# aqc-rev4.net
KiCad netlist of a schematic drawn in EAGLE
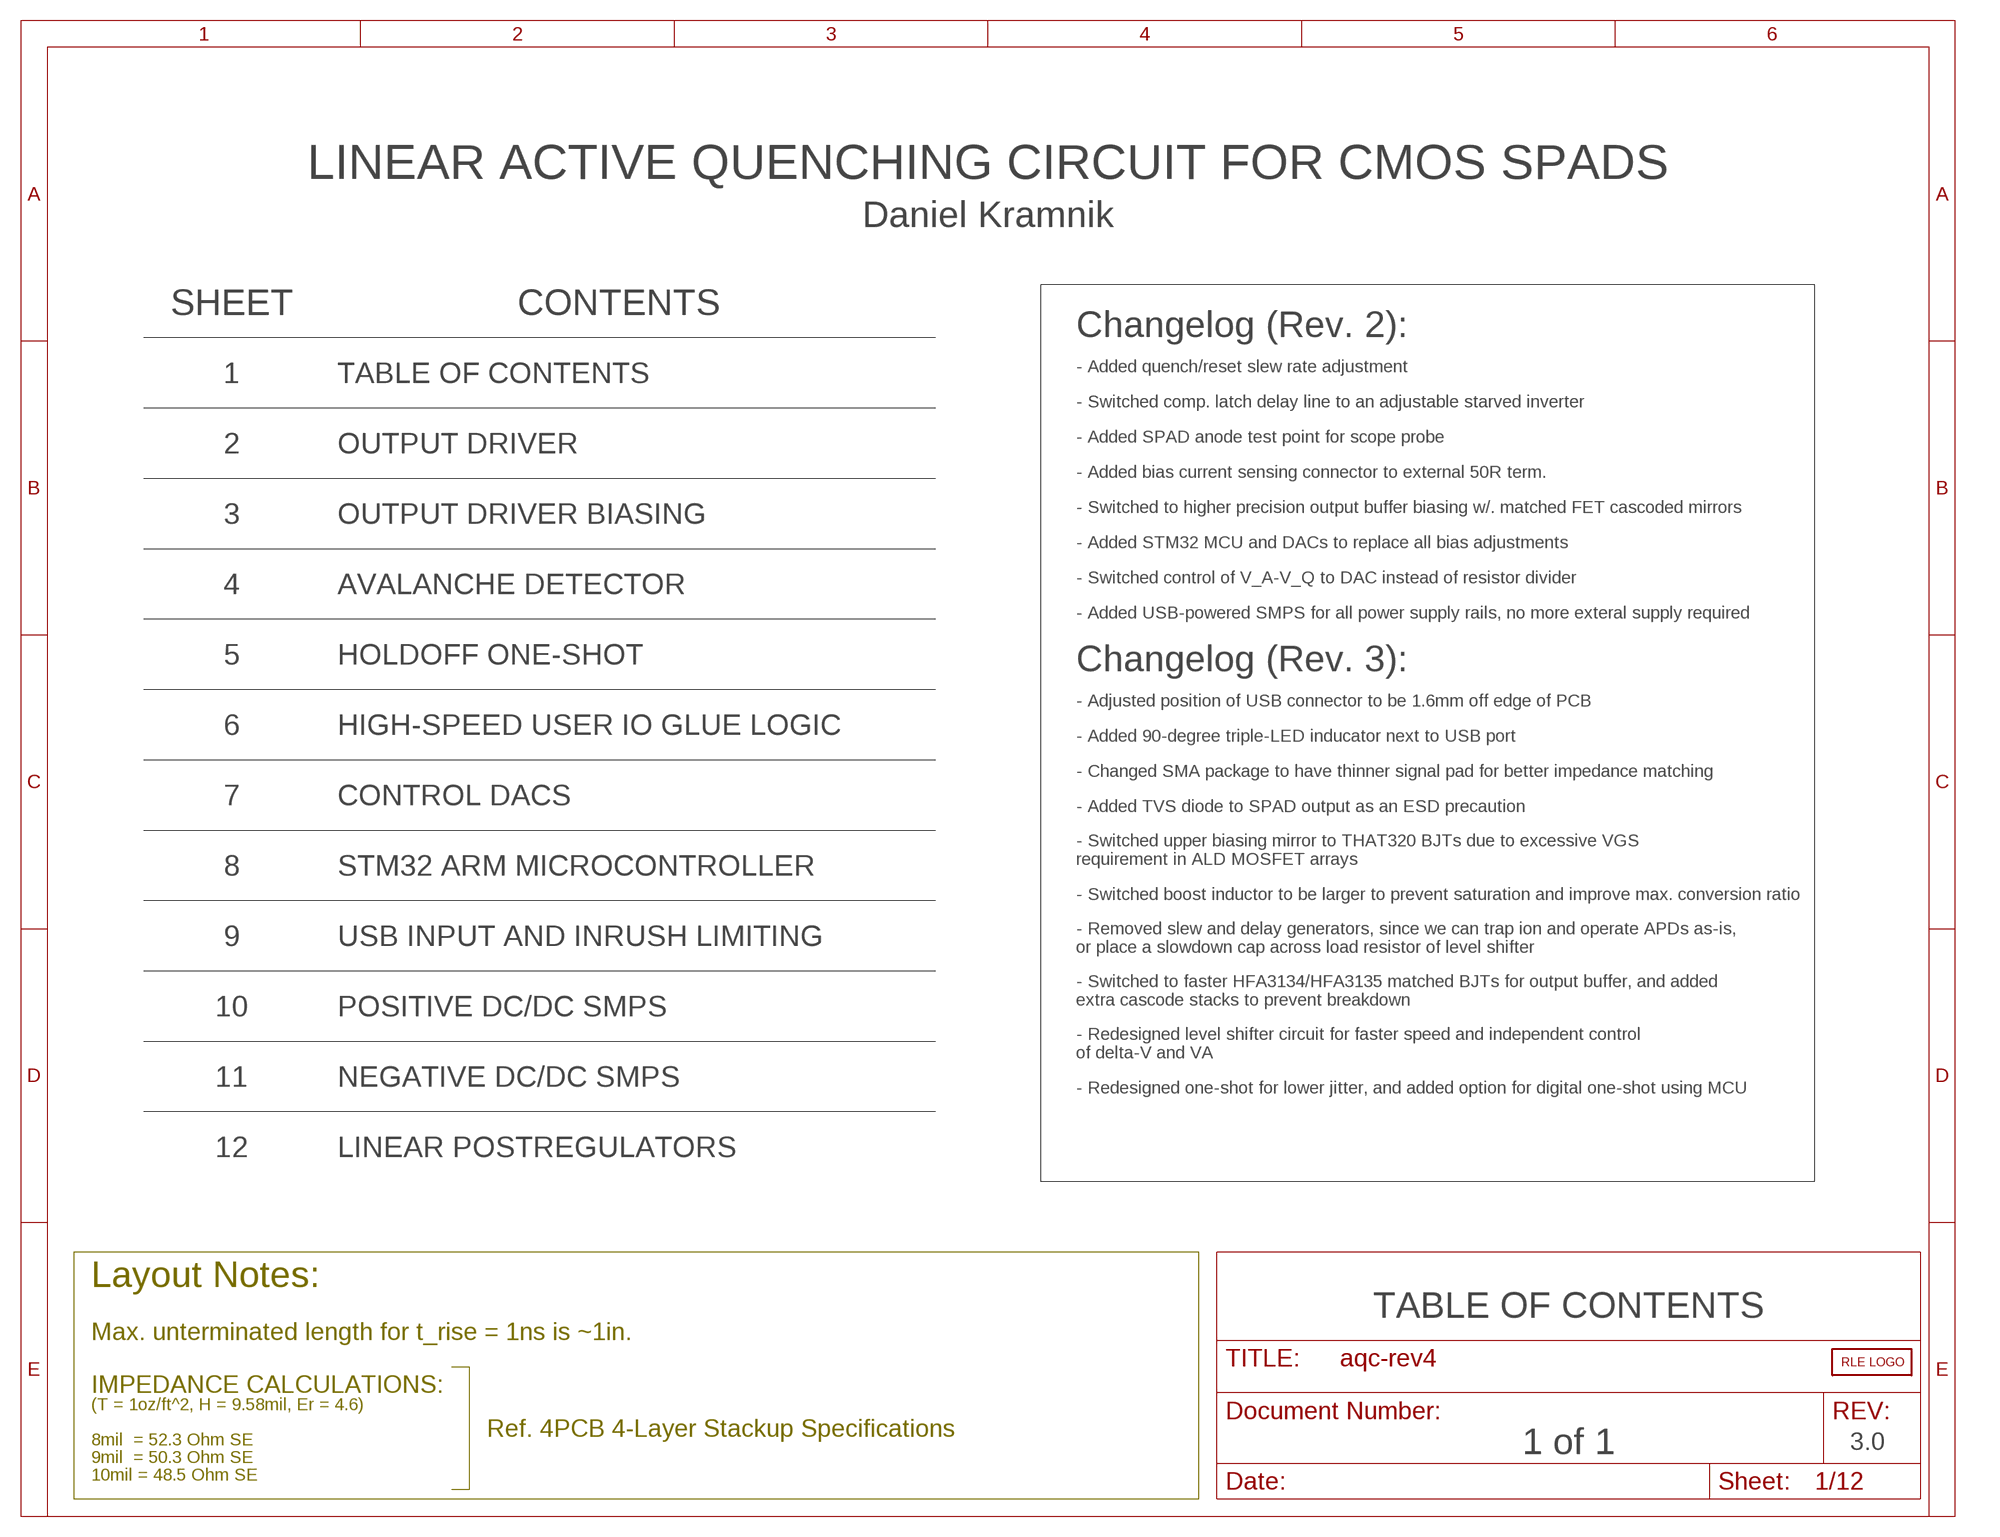
[diagram p0: schematic, sheet 1]
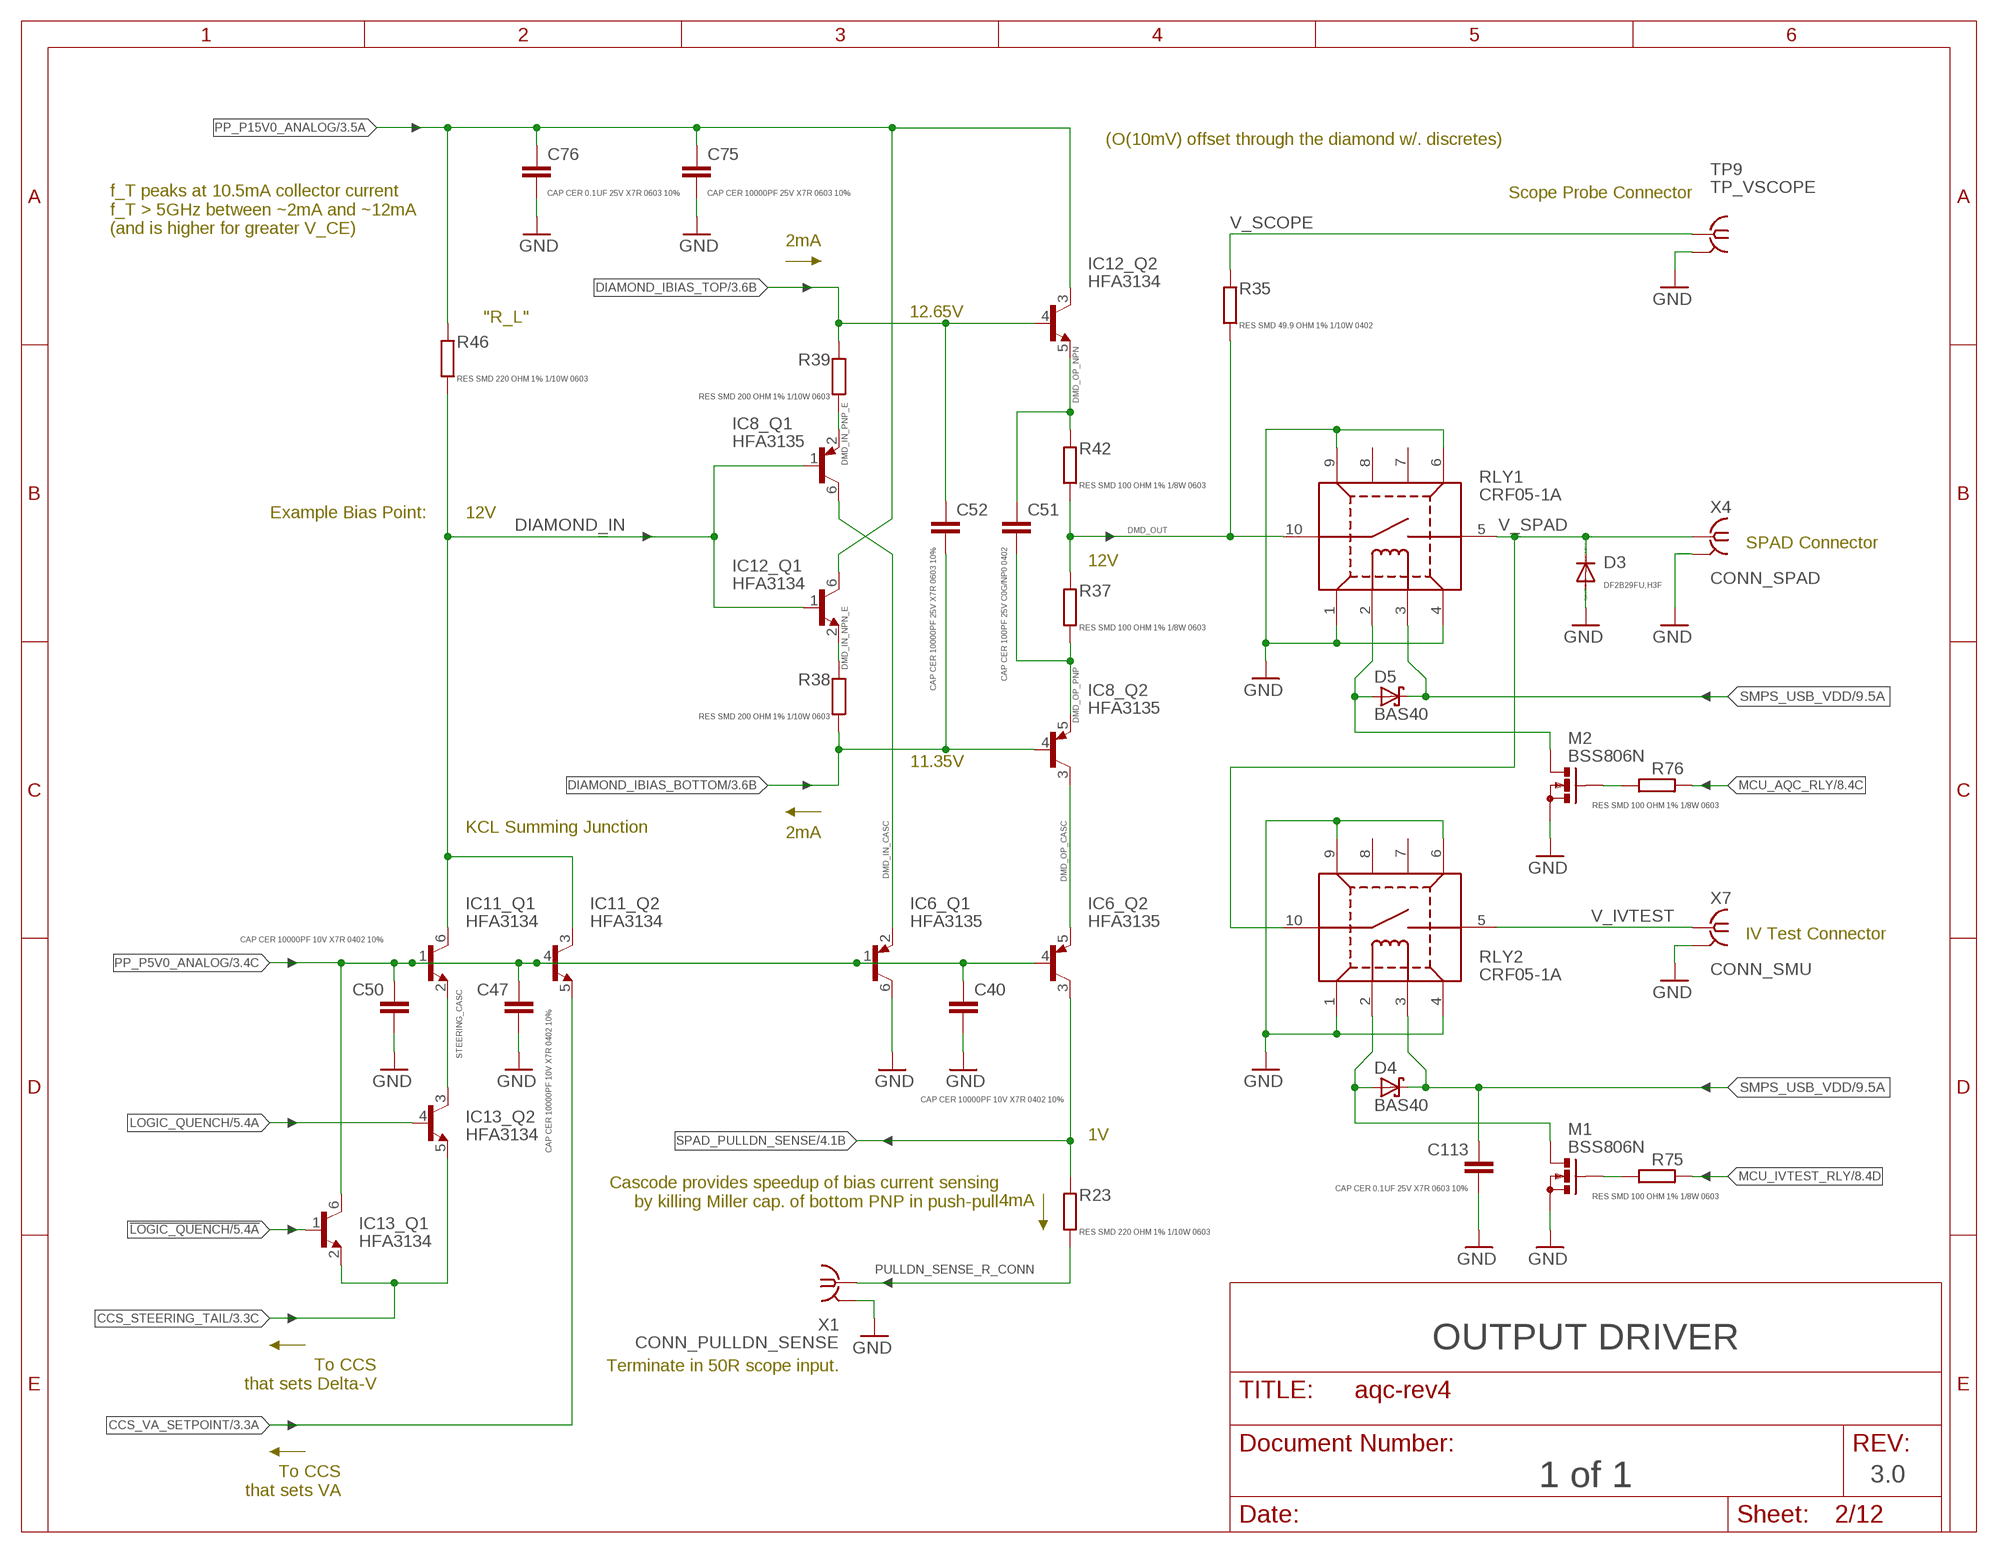
[diagram p1: schematic, sheet 2]
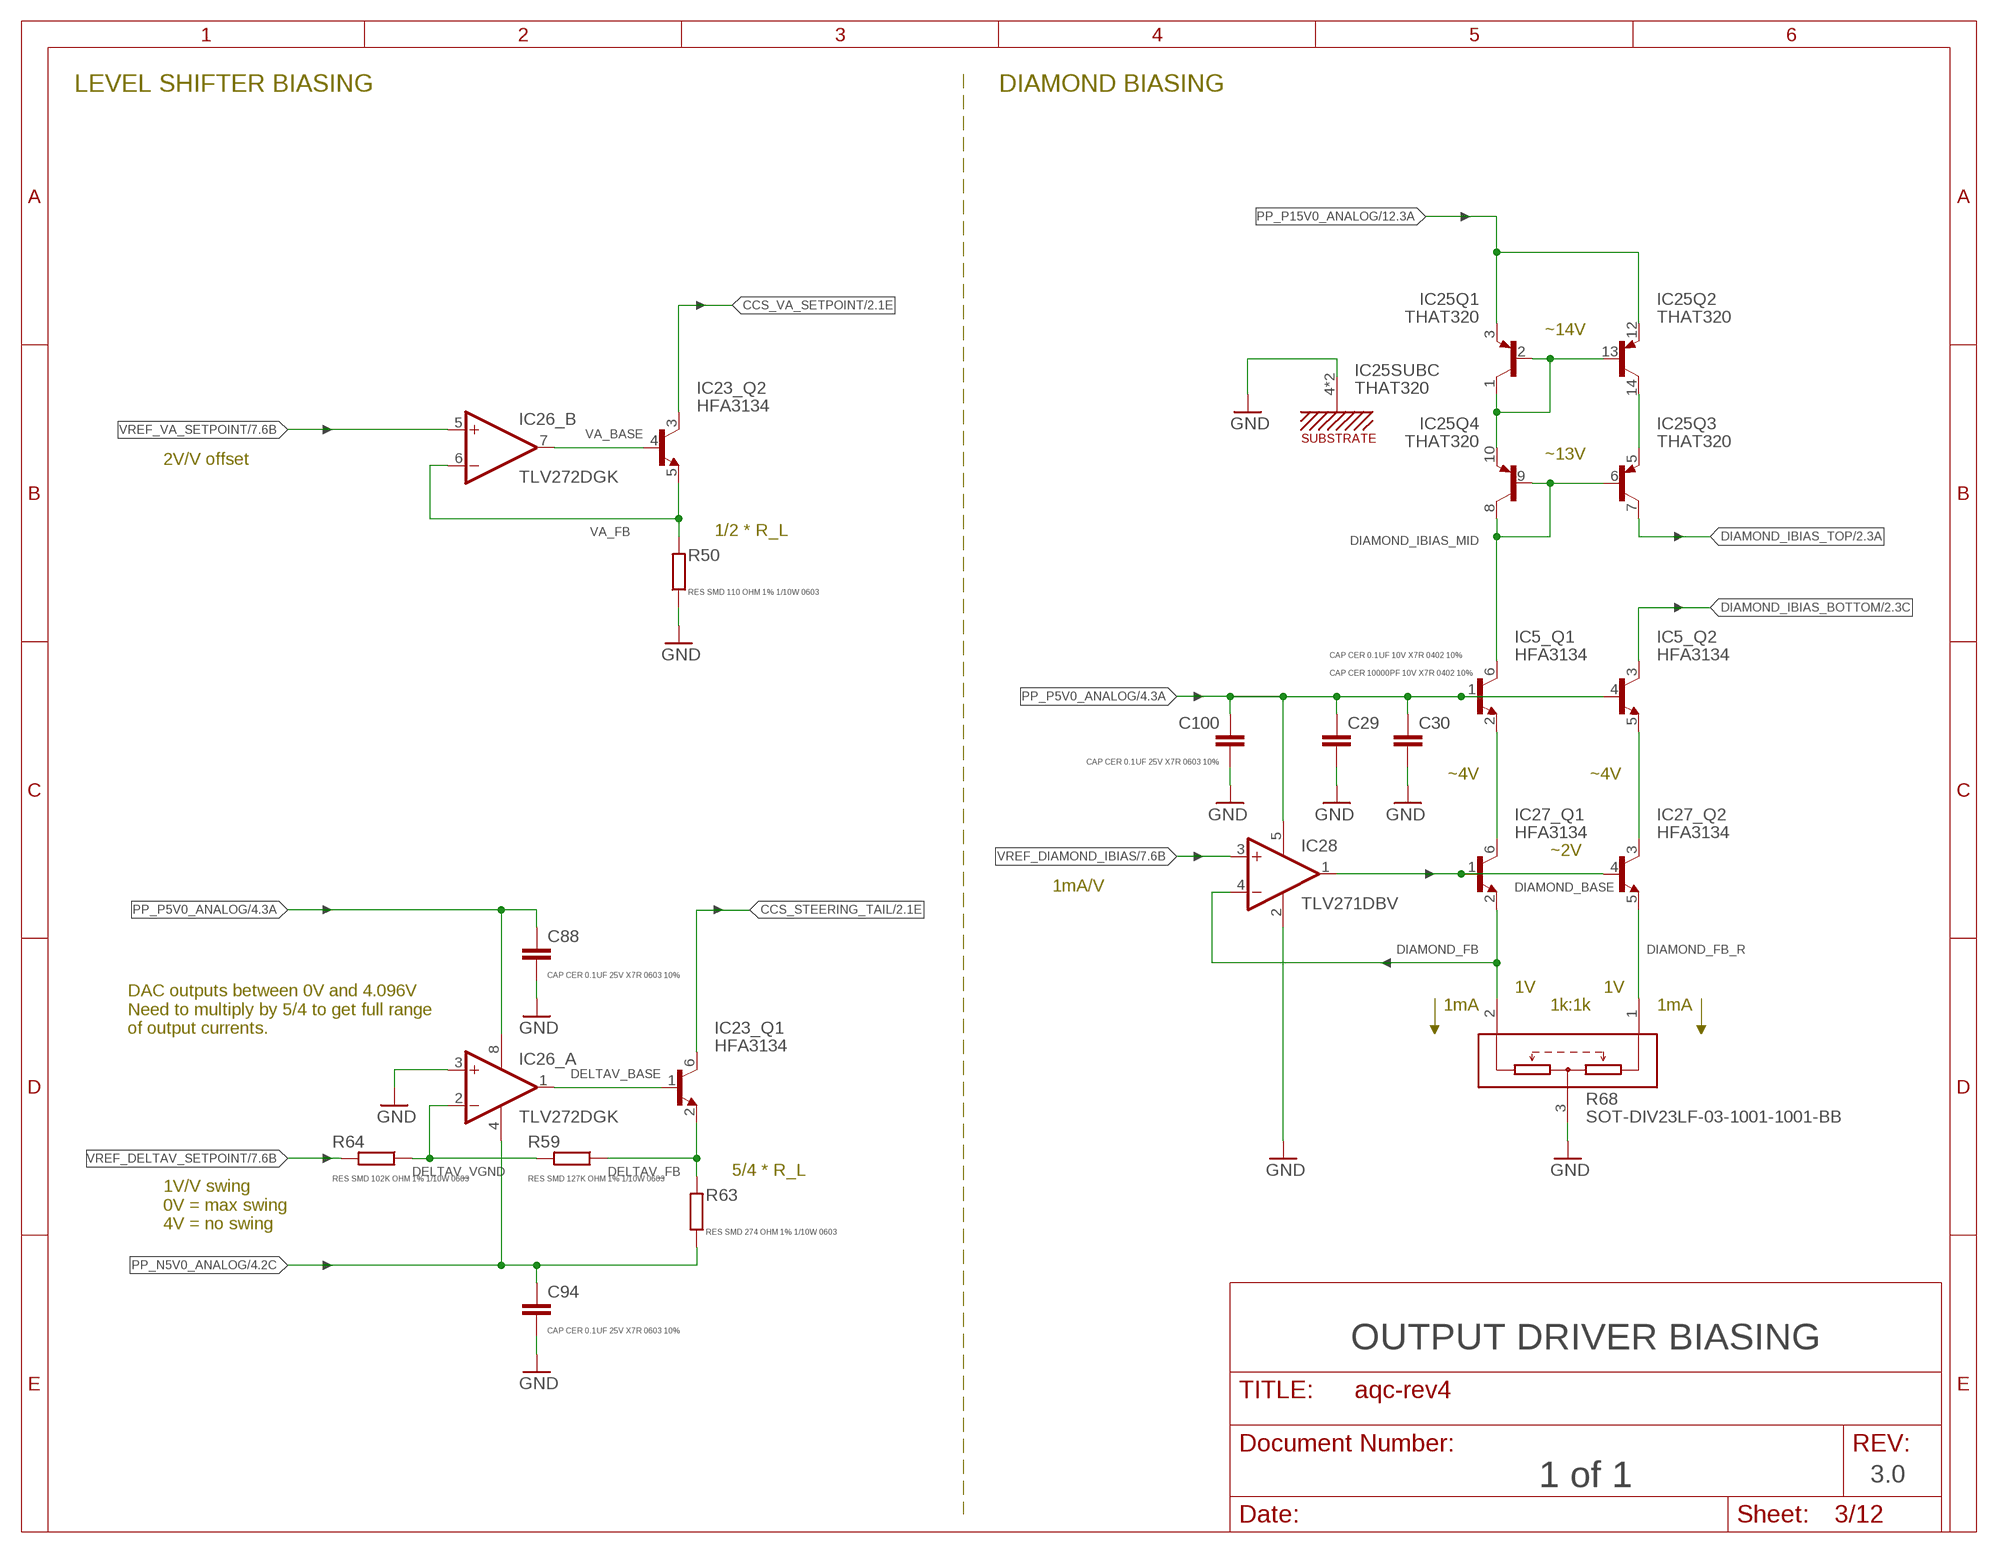
[diagram p2: schematic, sheet 3]
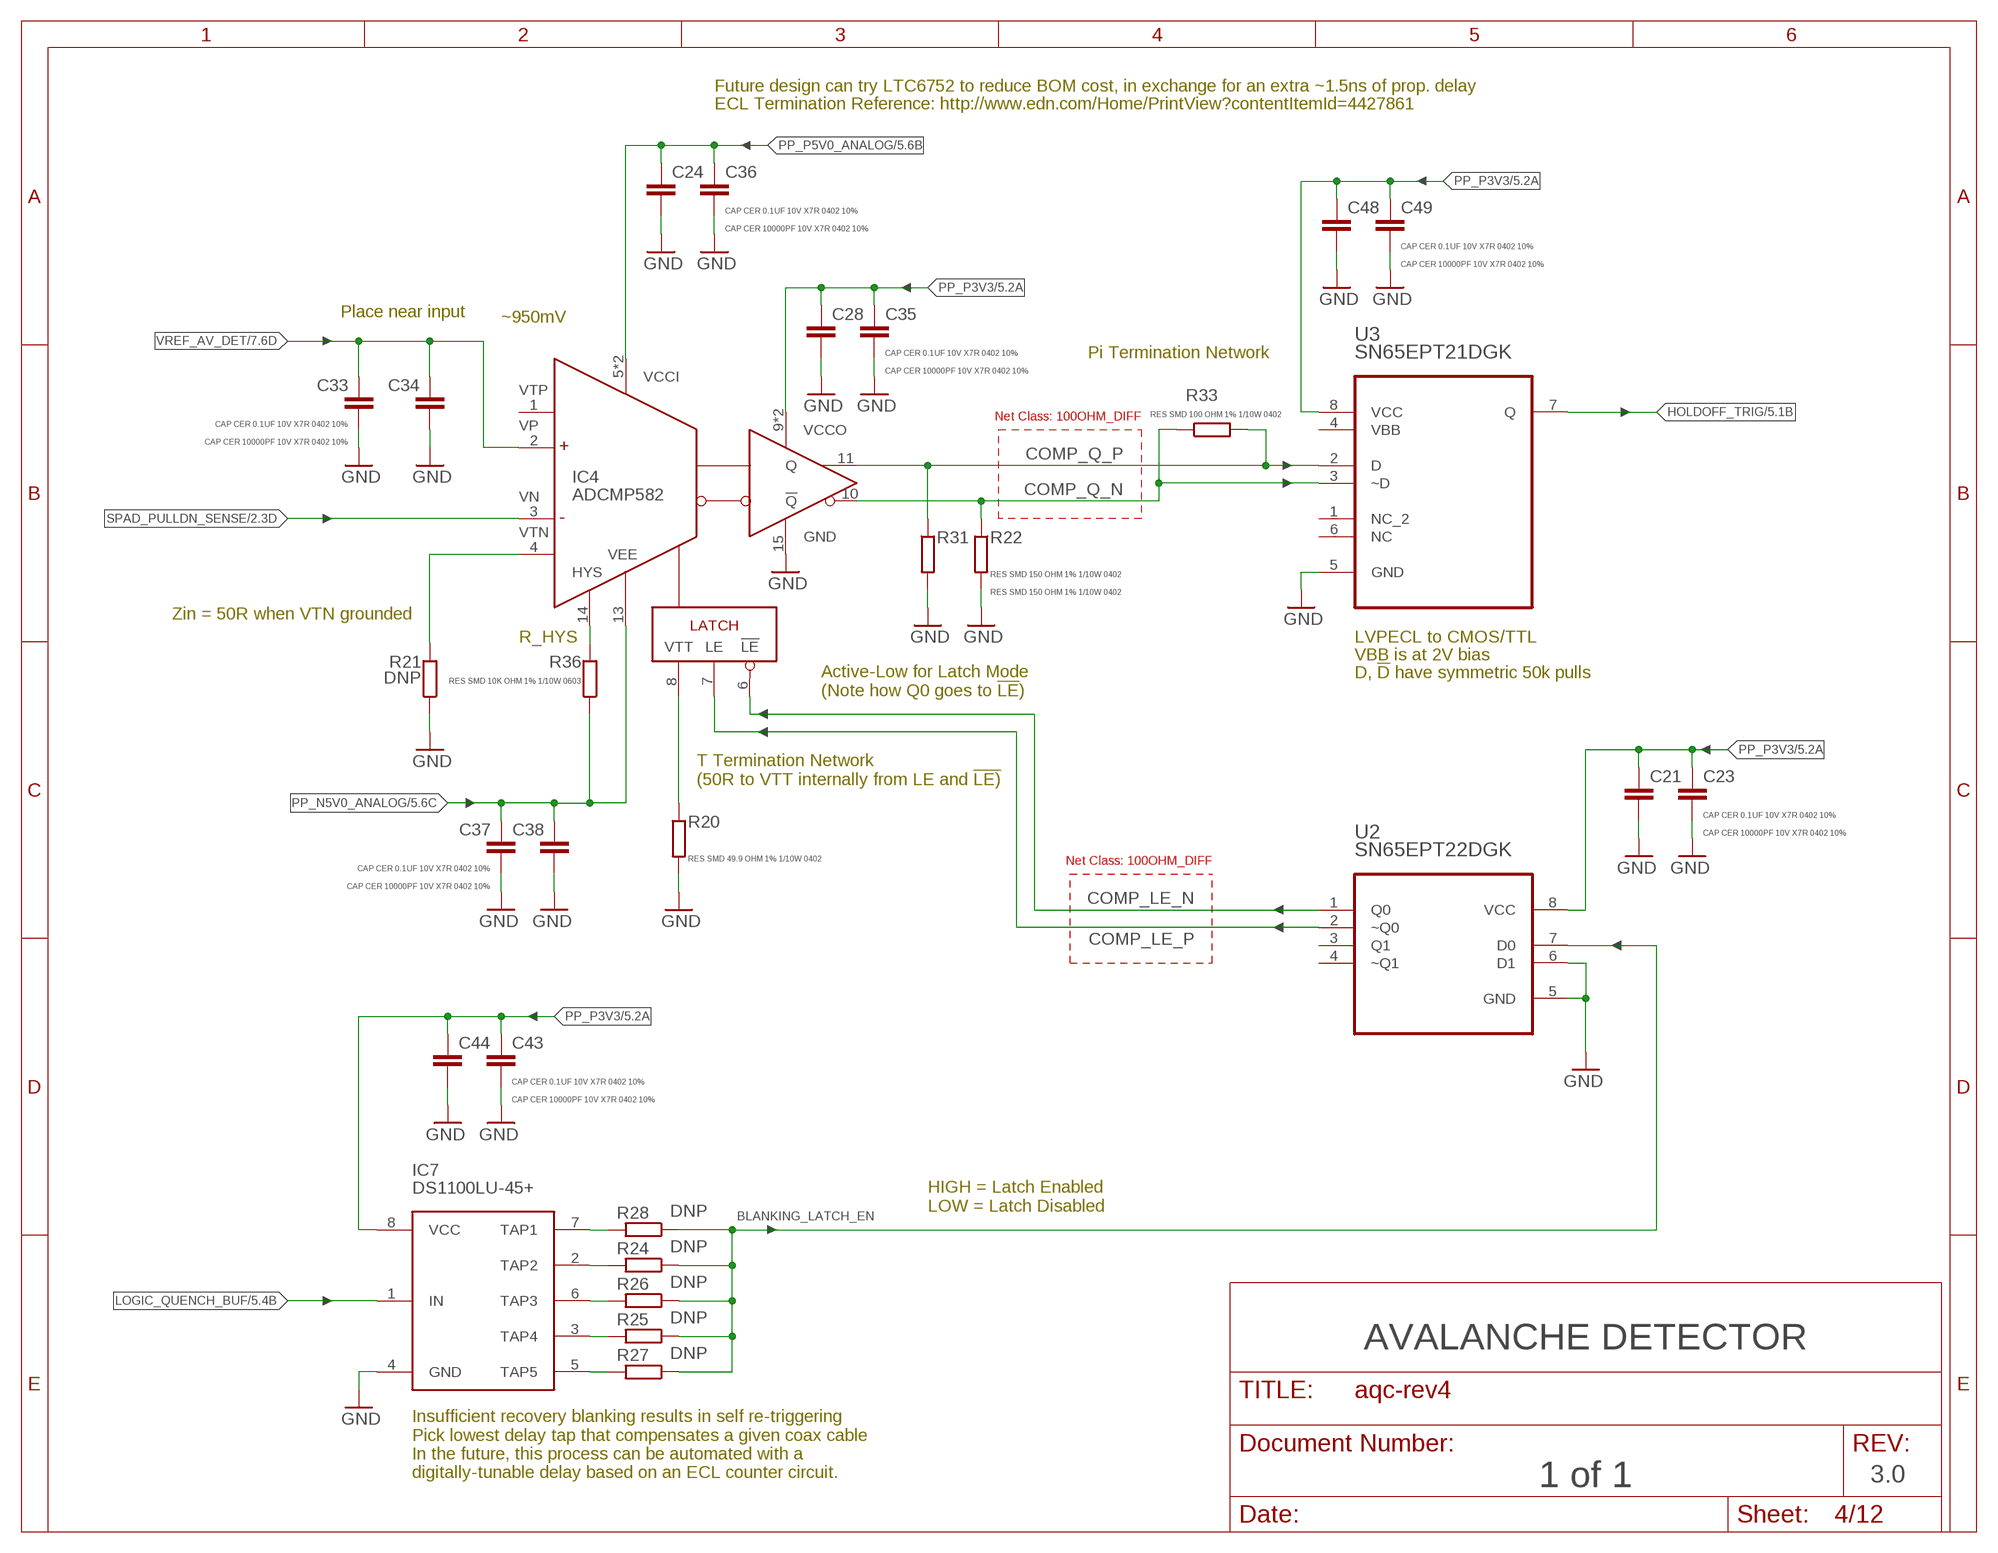
[diagram p3: schematic, sheet 4]
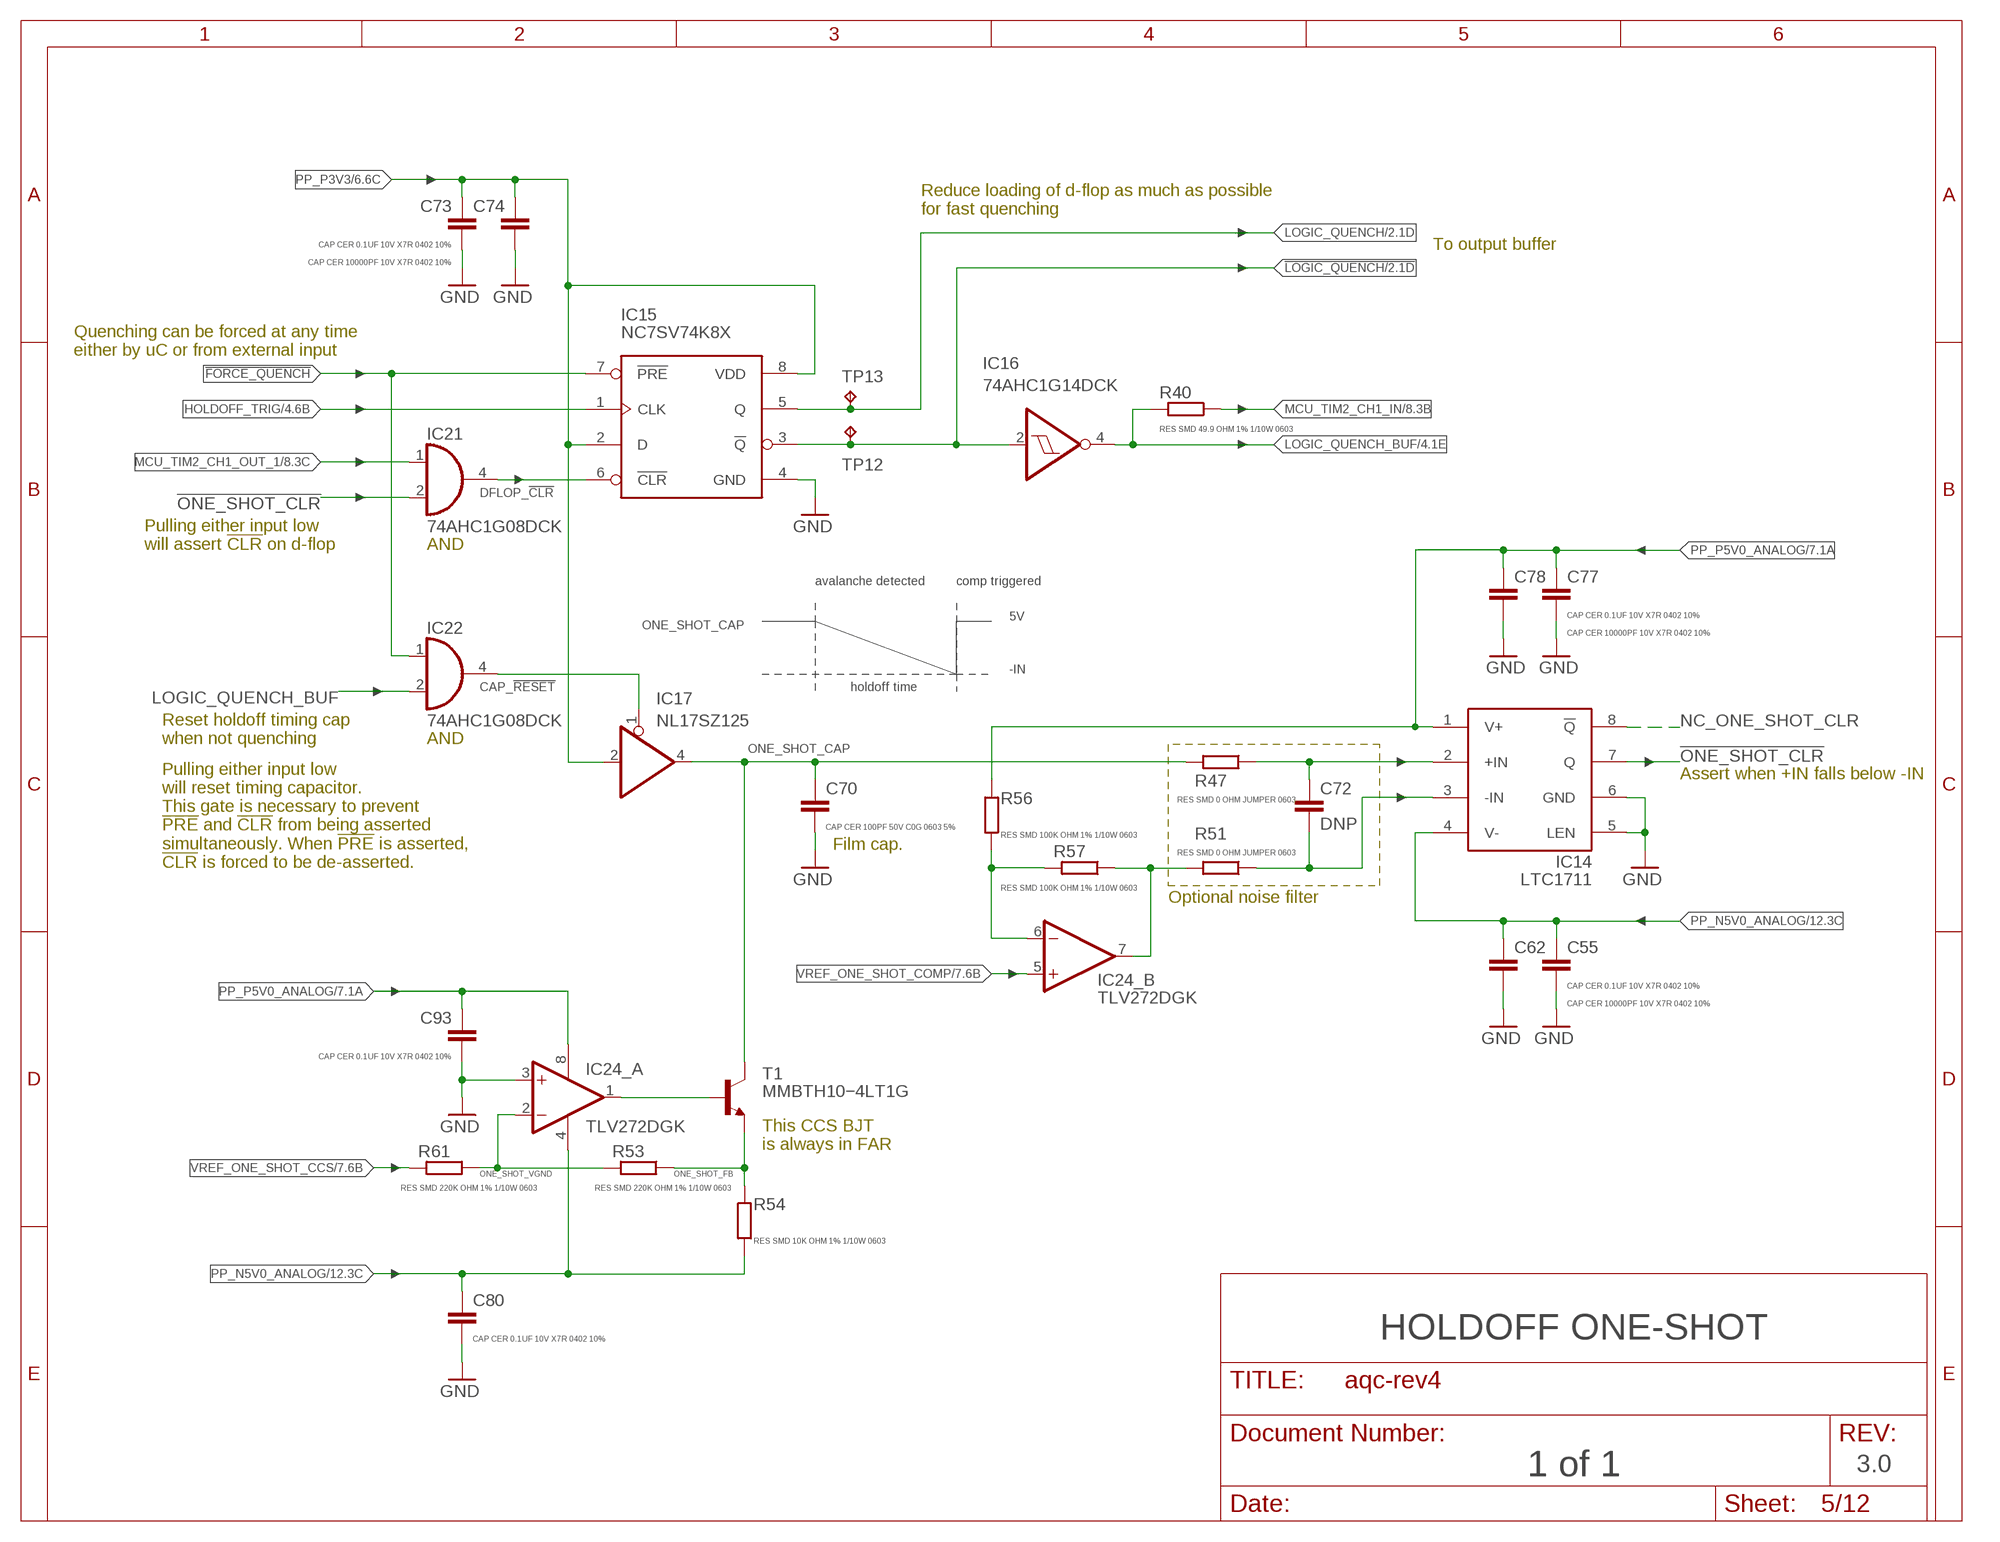
[diagram p4: schematic, sheet 5]
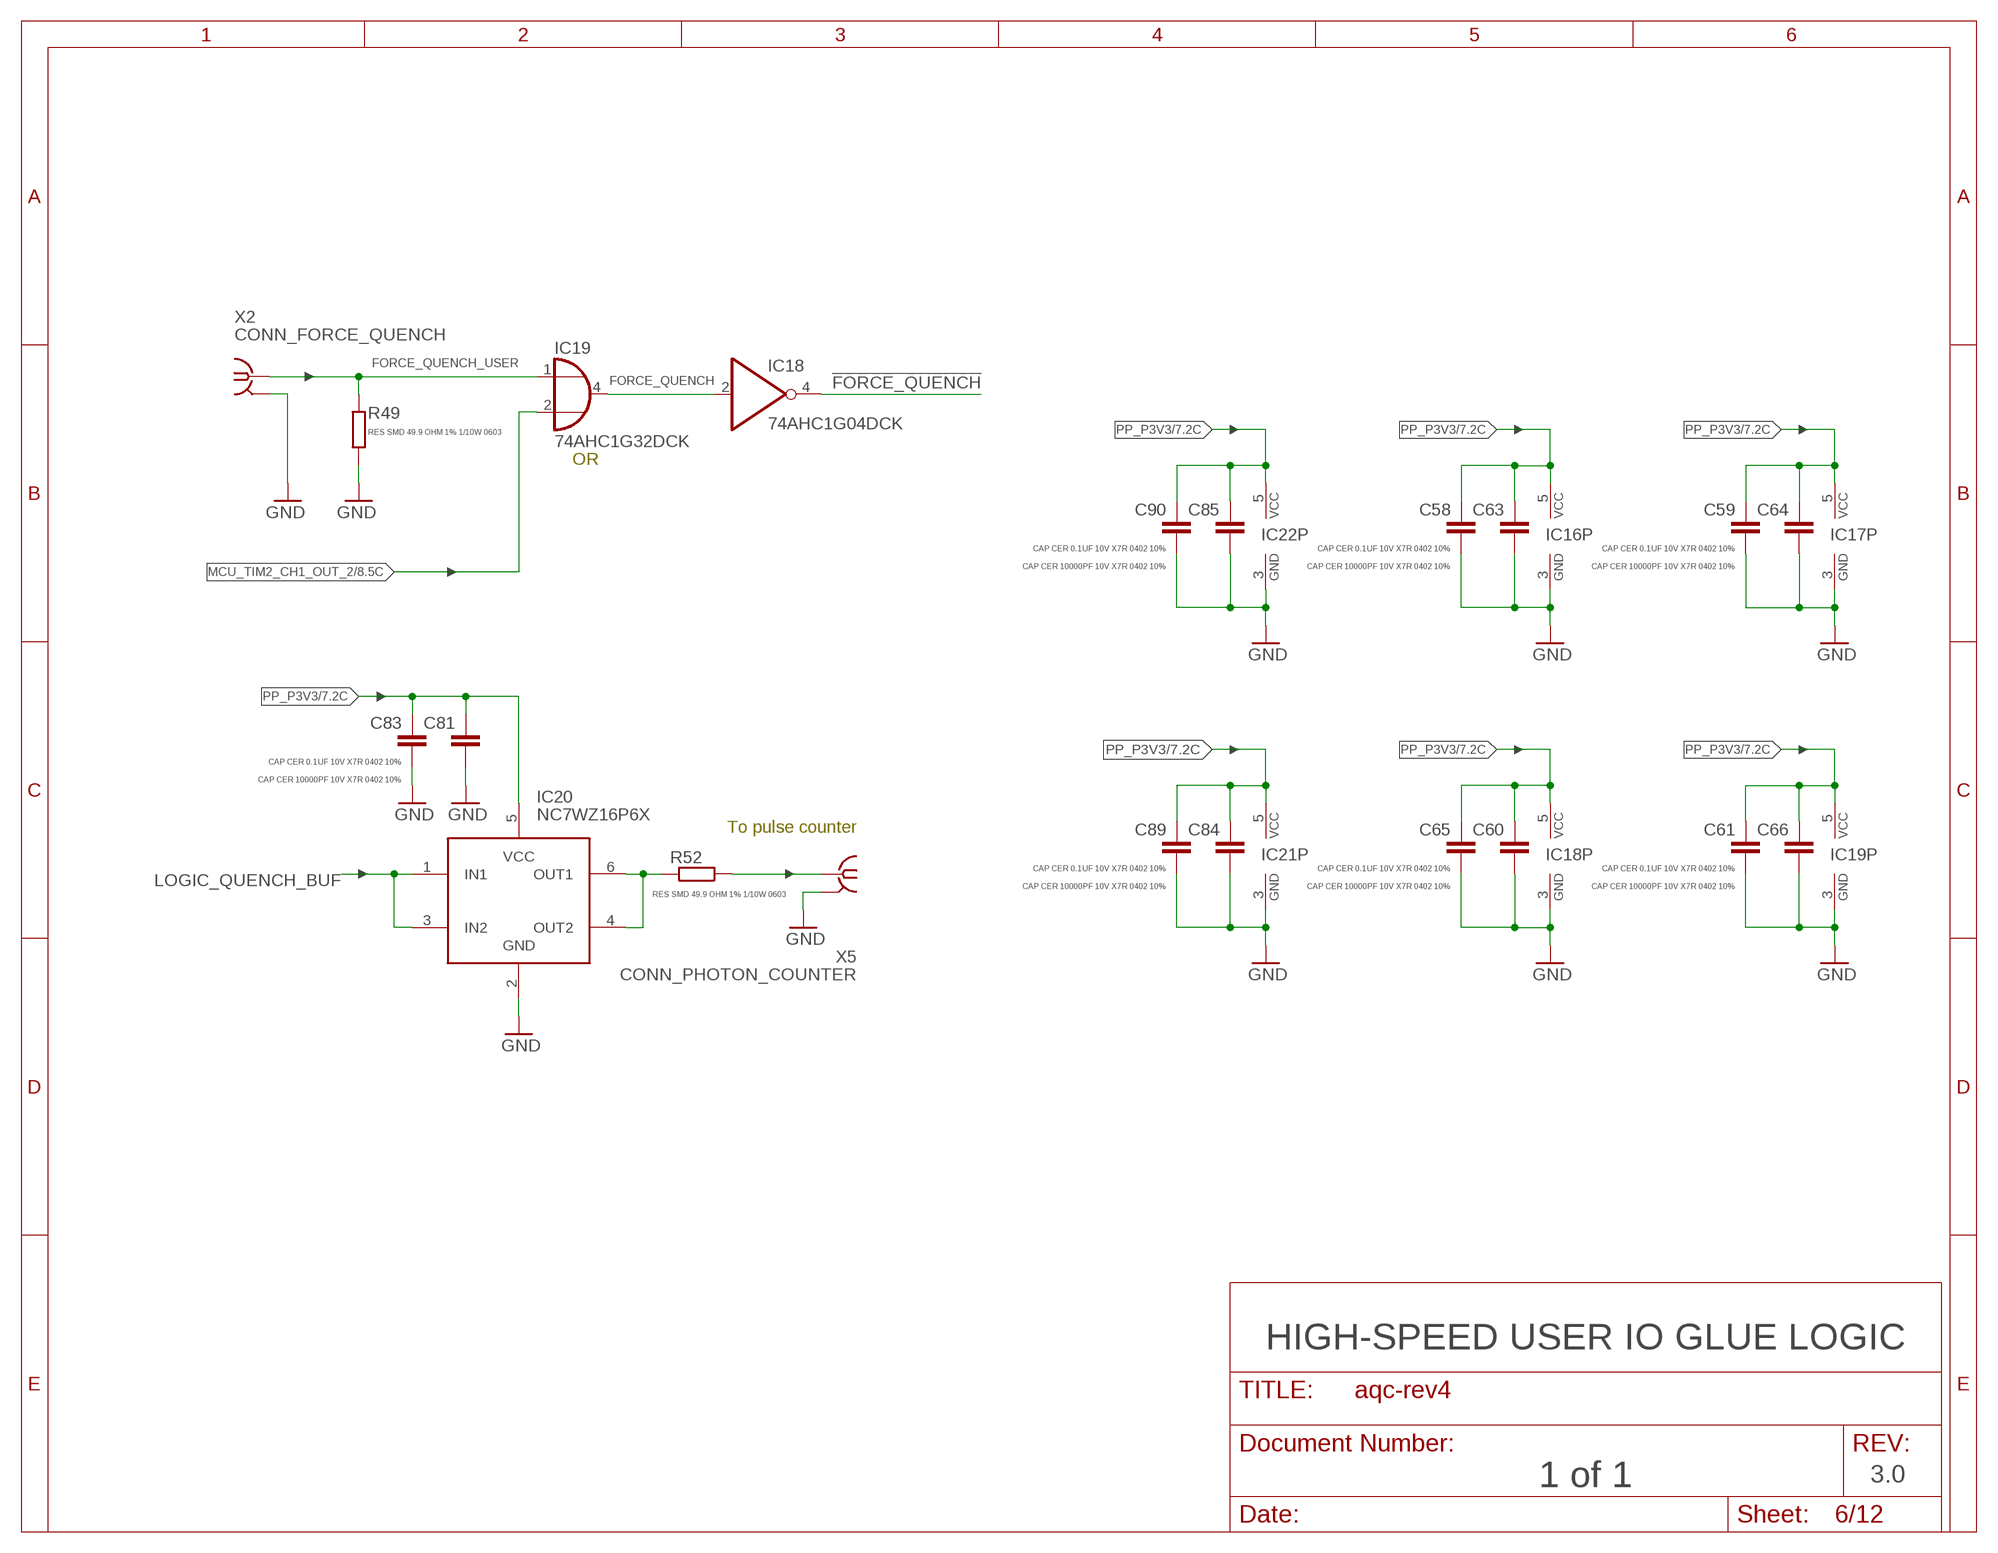
[diagram p5: schematic, sheet 6]
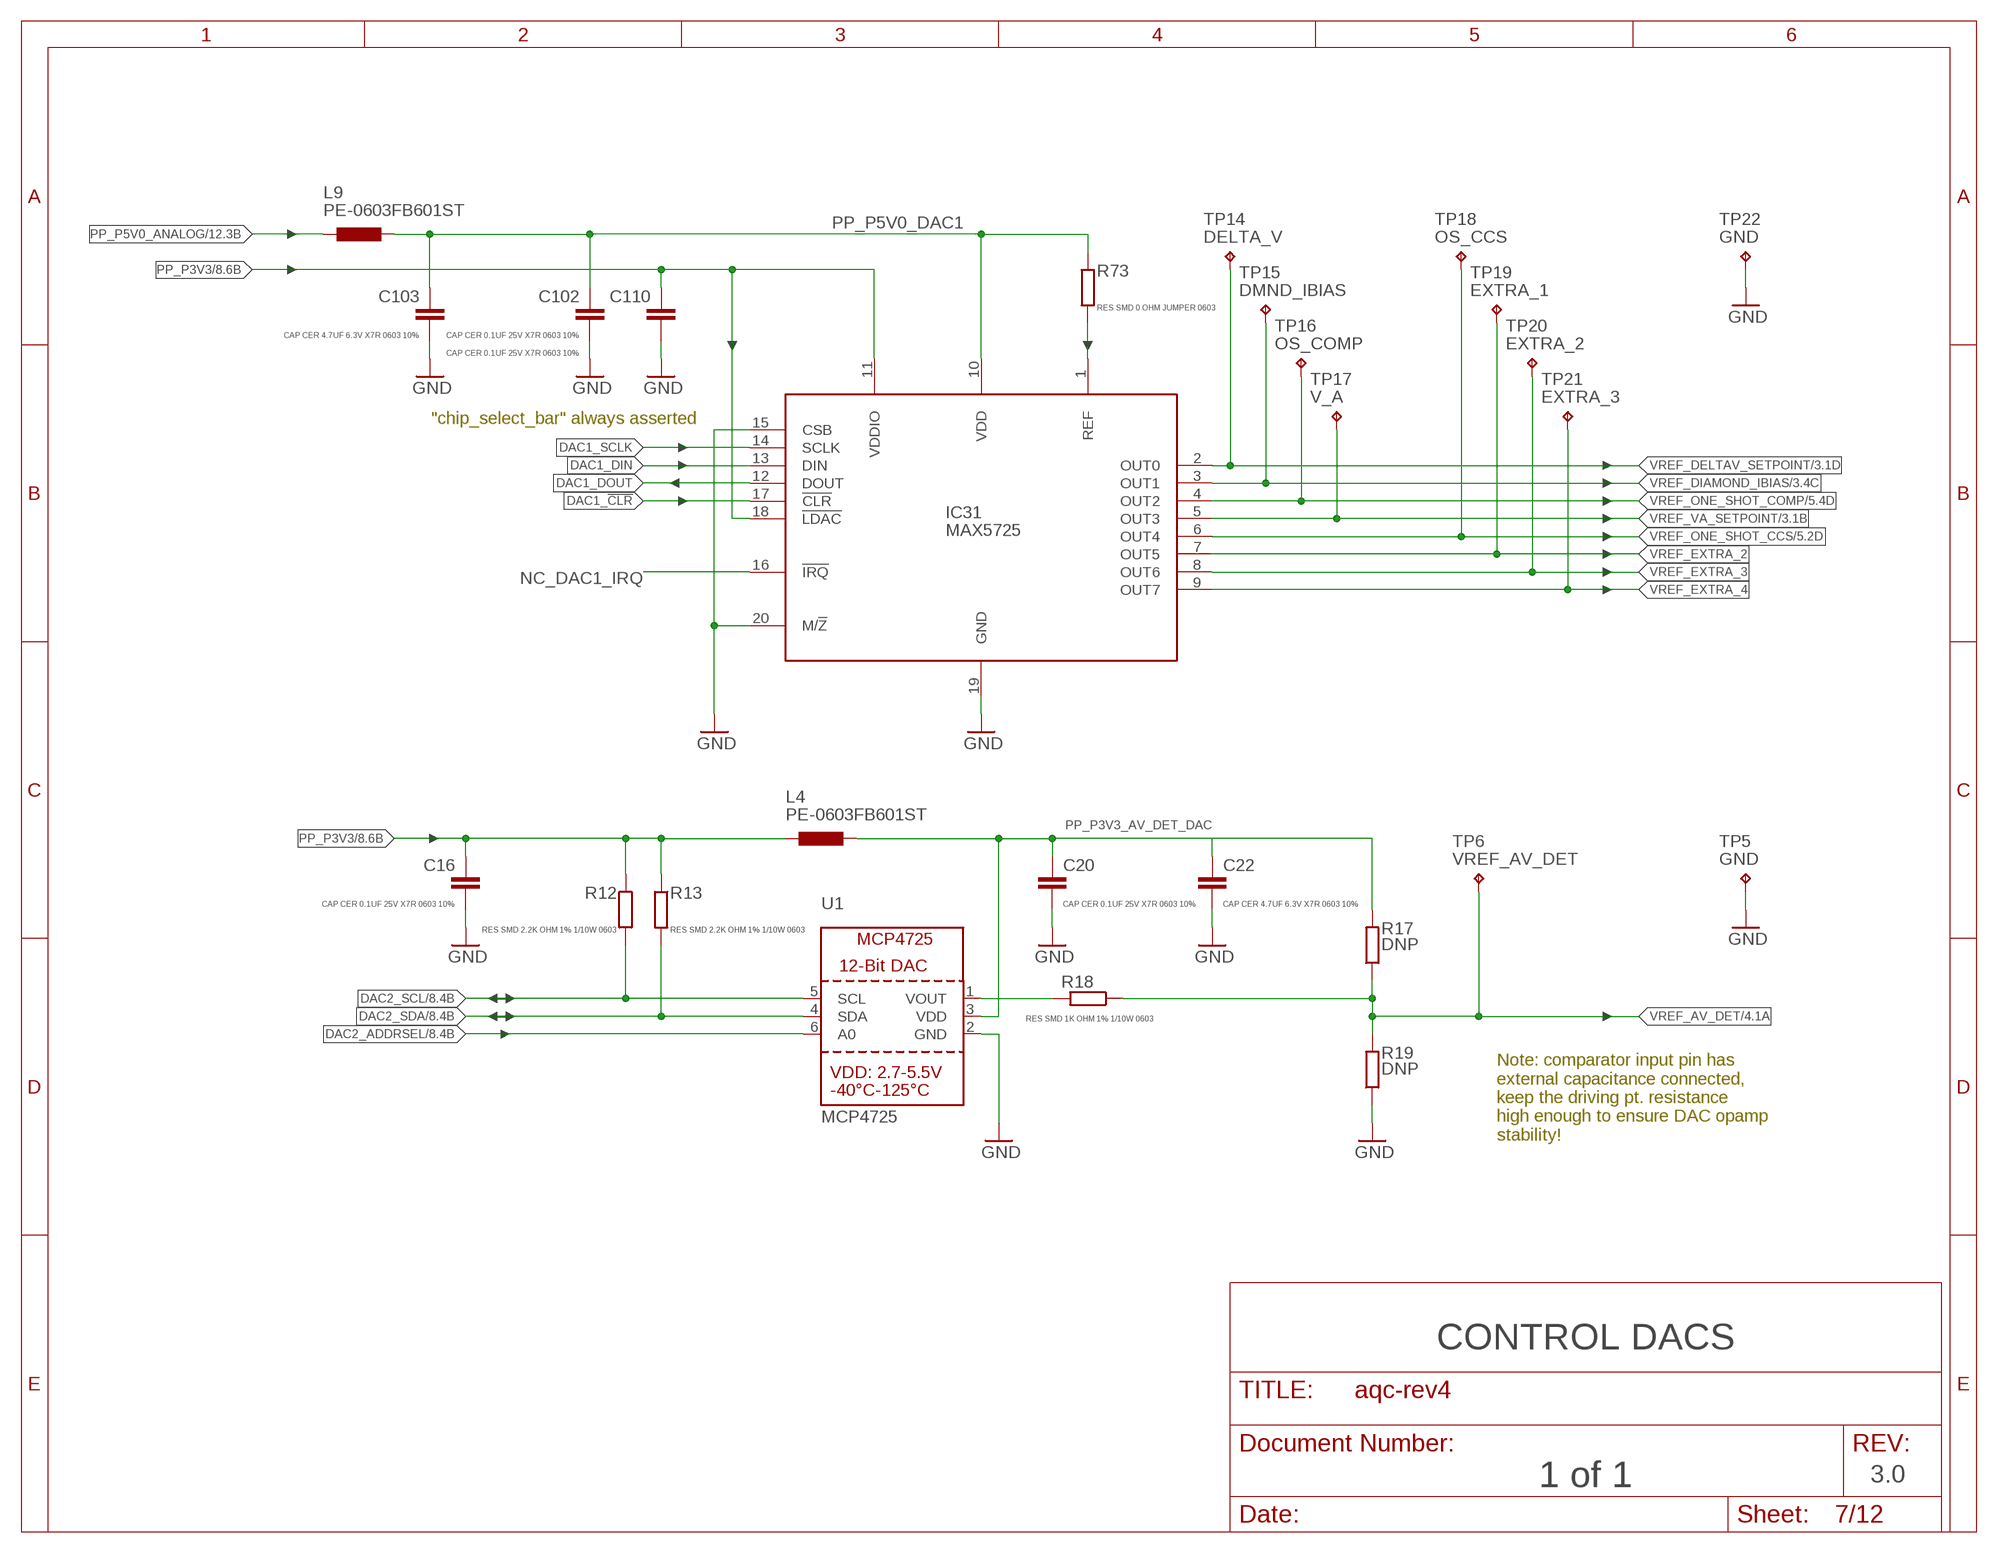
[diagram p6: schematic, sheet 7]
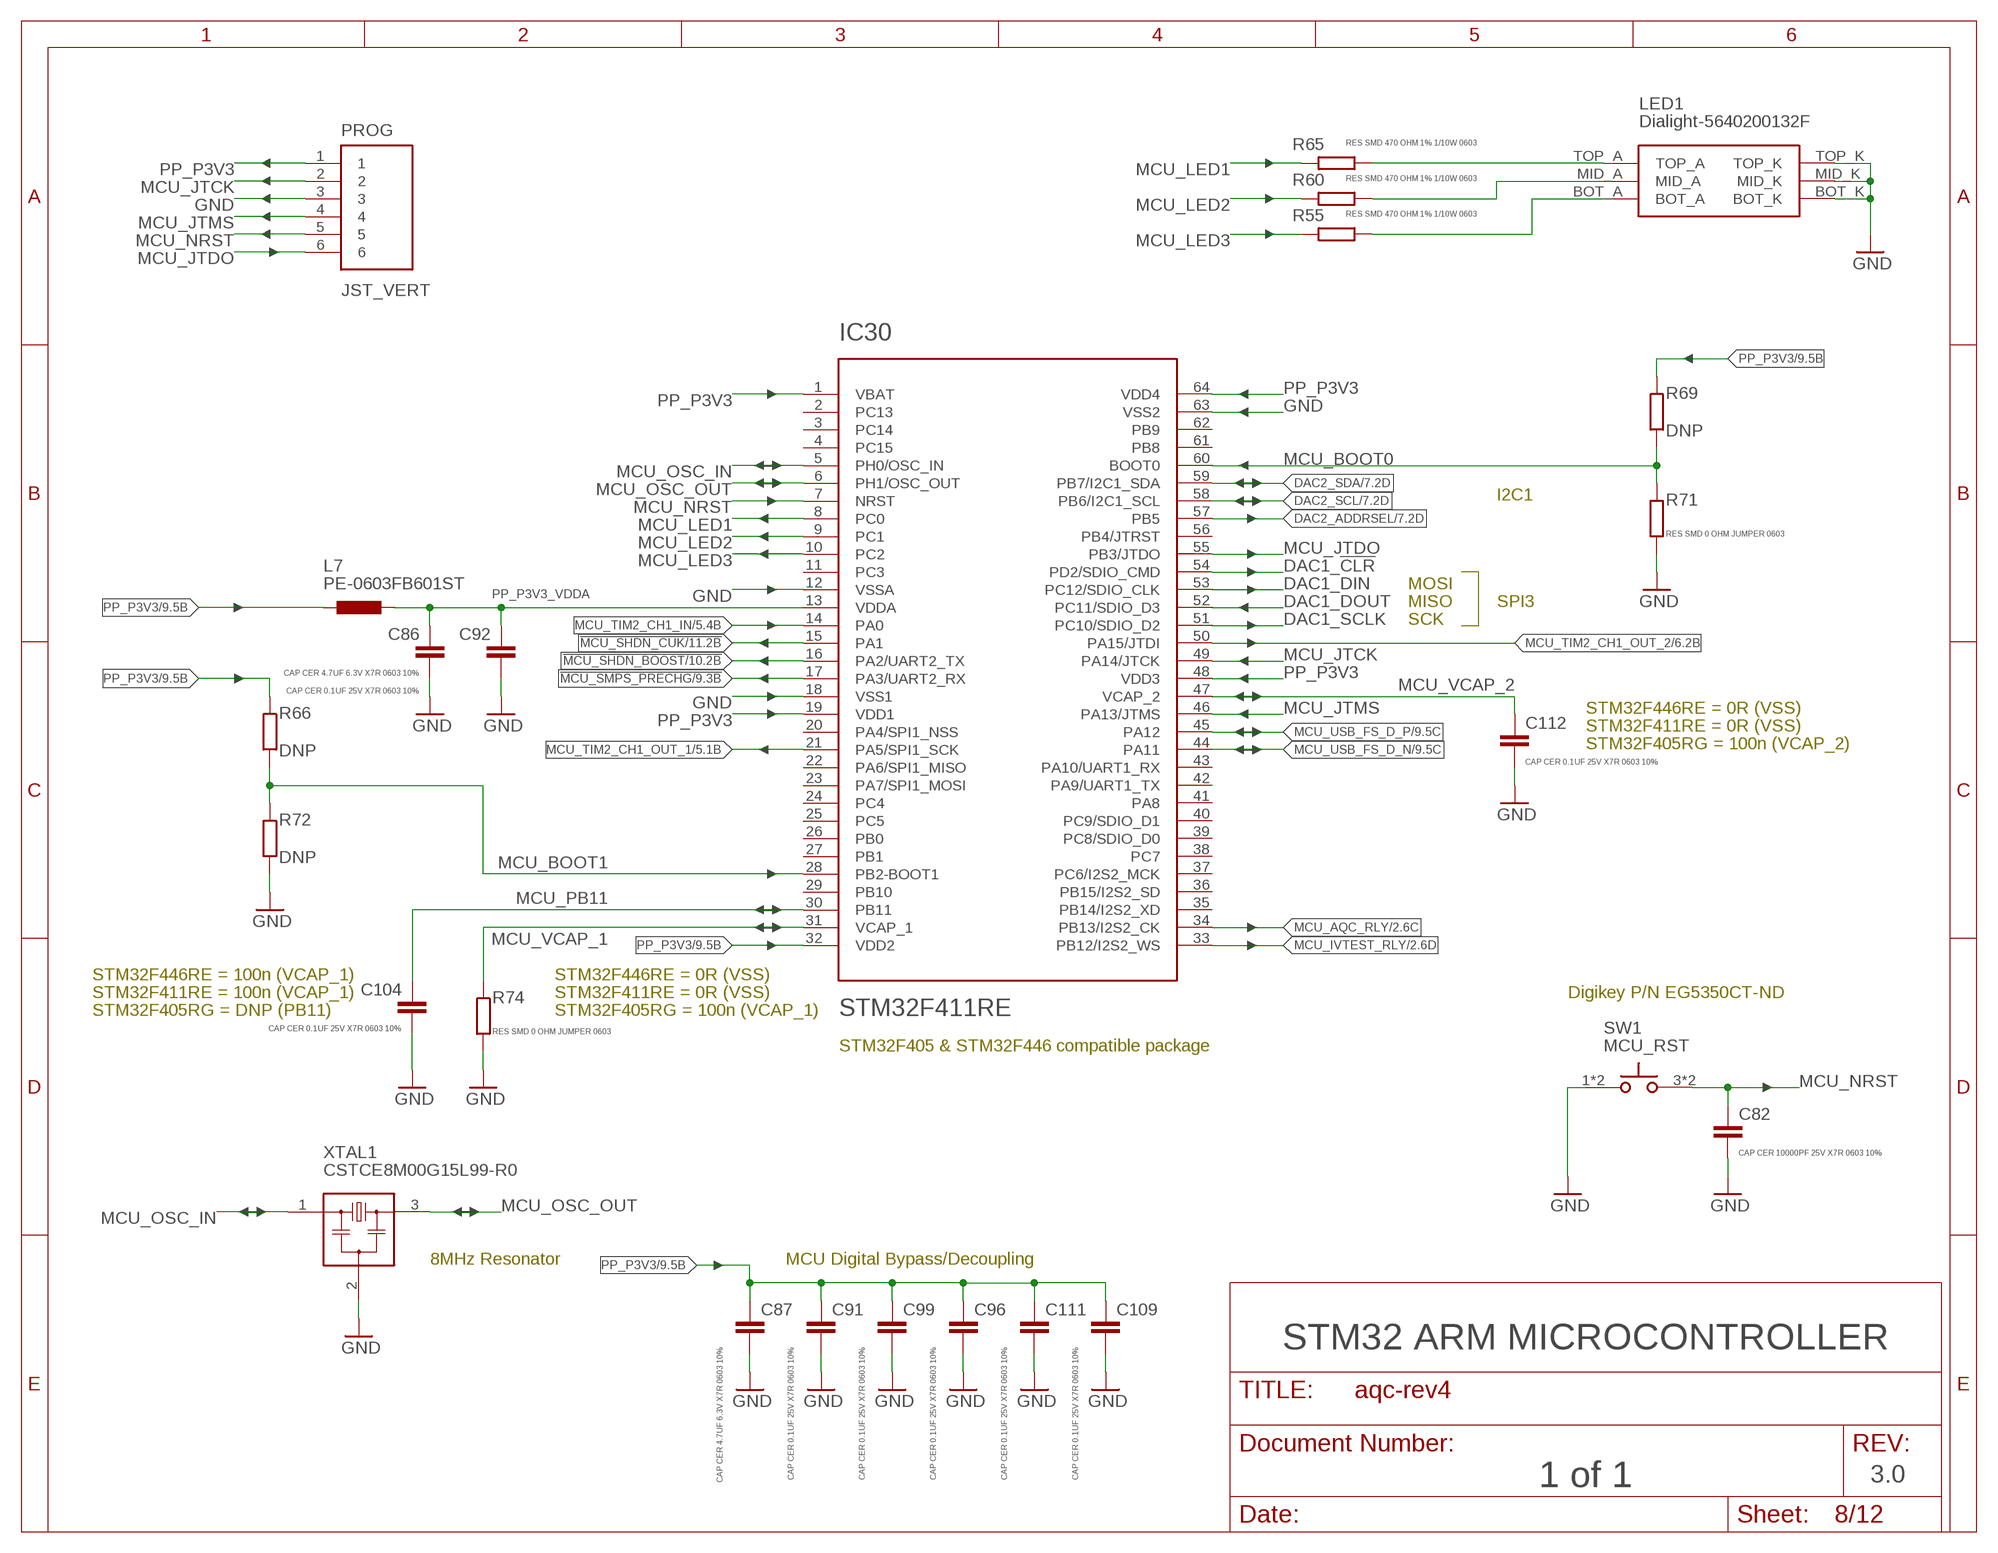
[diagram p7: schematic, sheet 8]
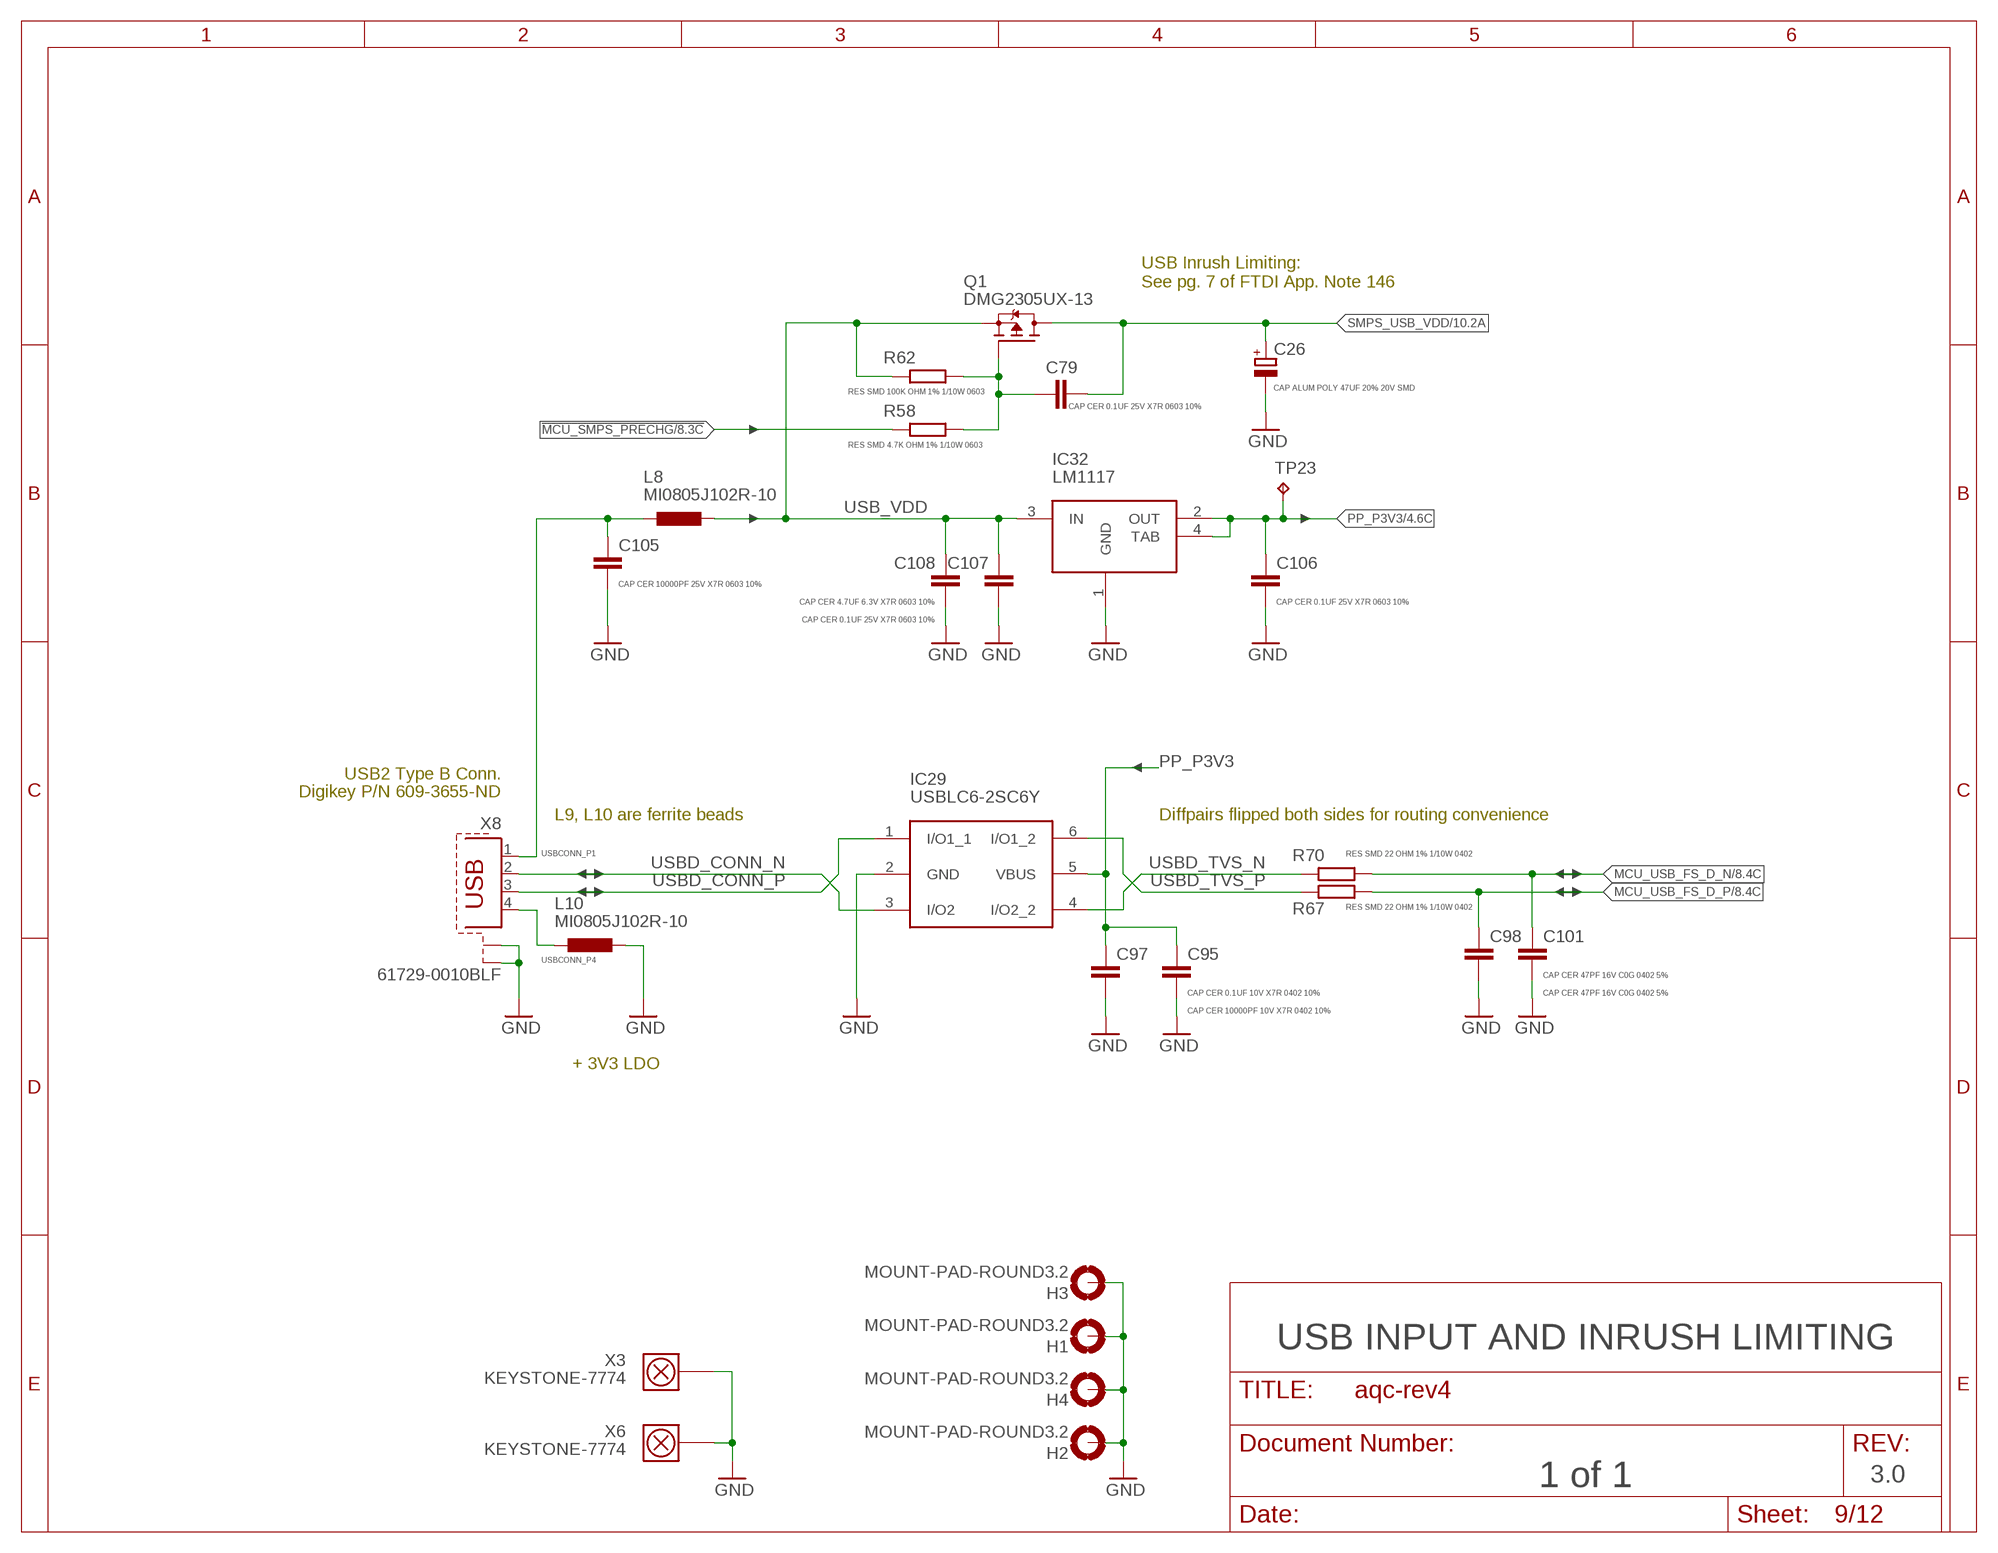
[diagram p8: schematic, sheet 9]
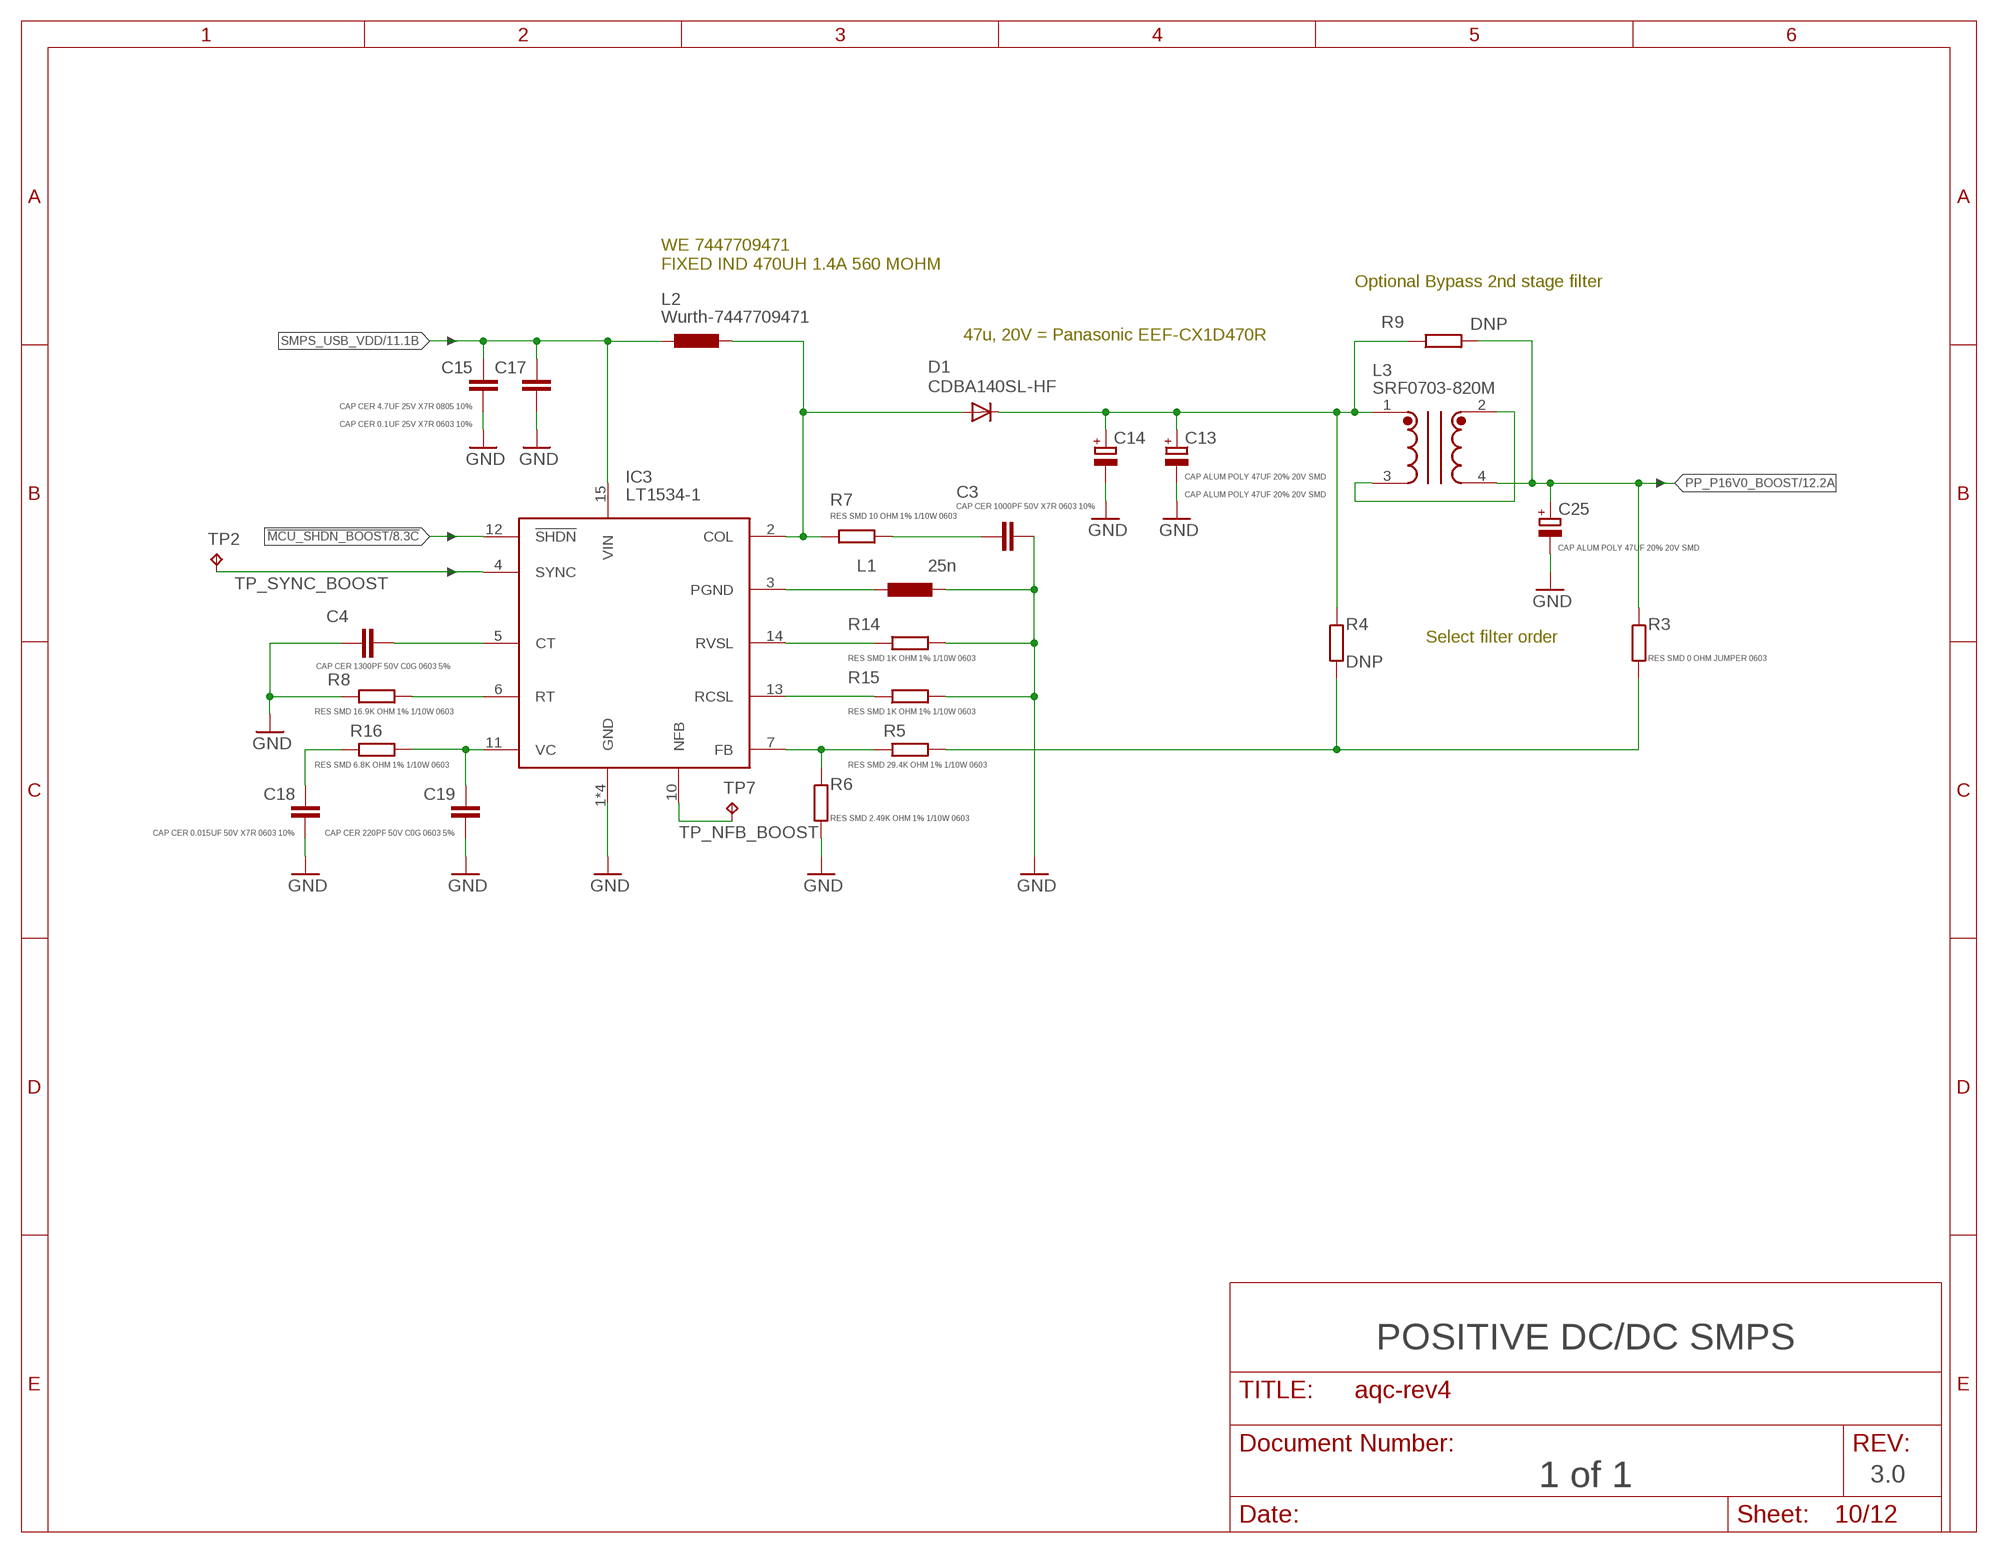
[diagram p9: schematic, sheet 10]
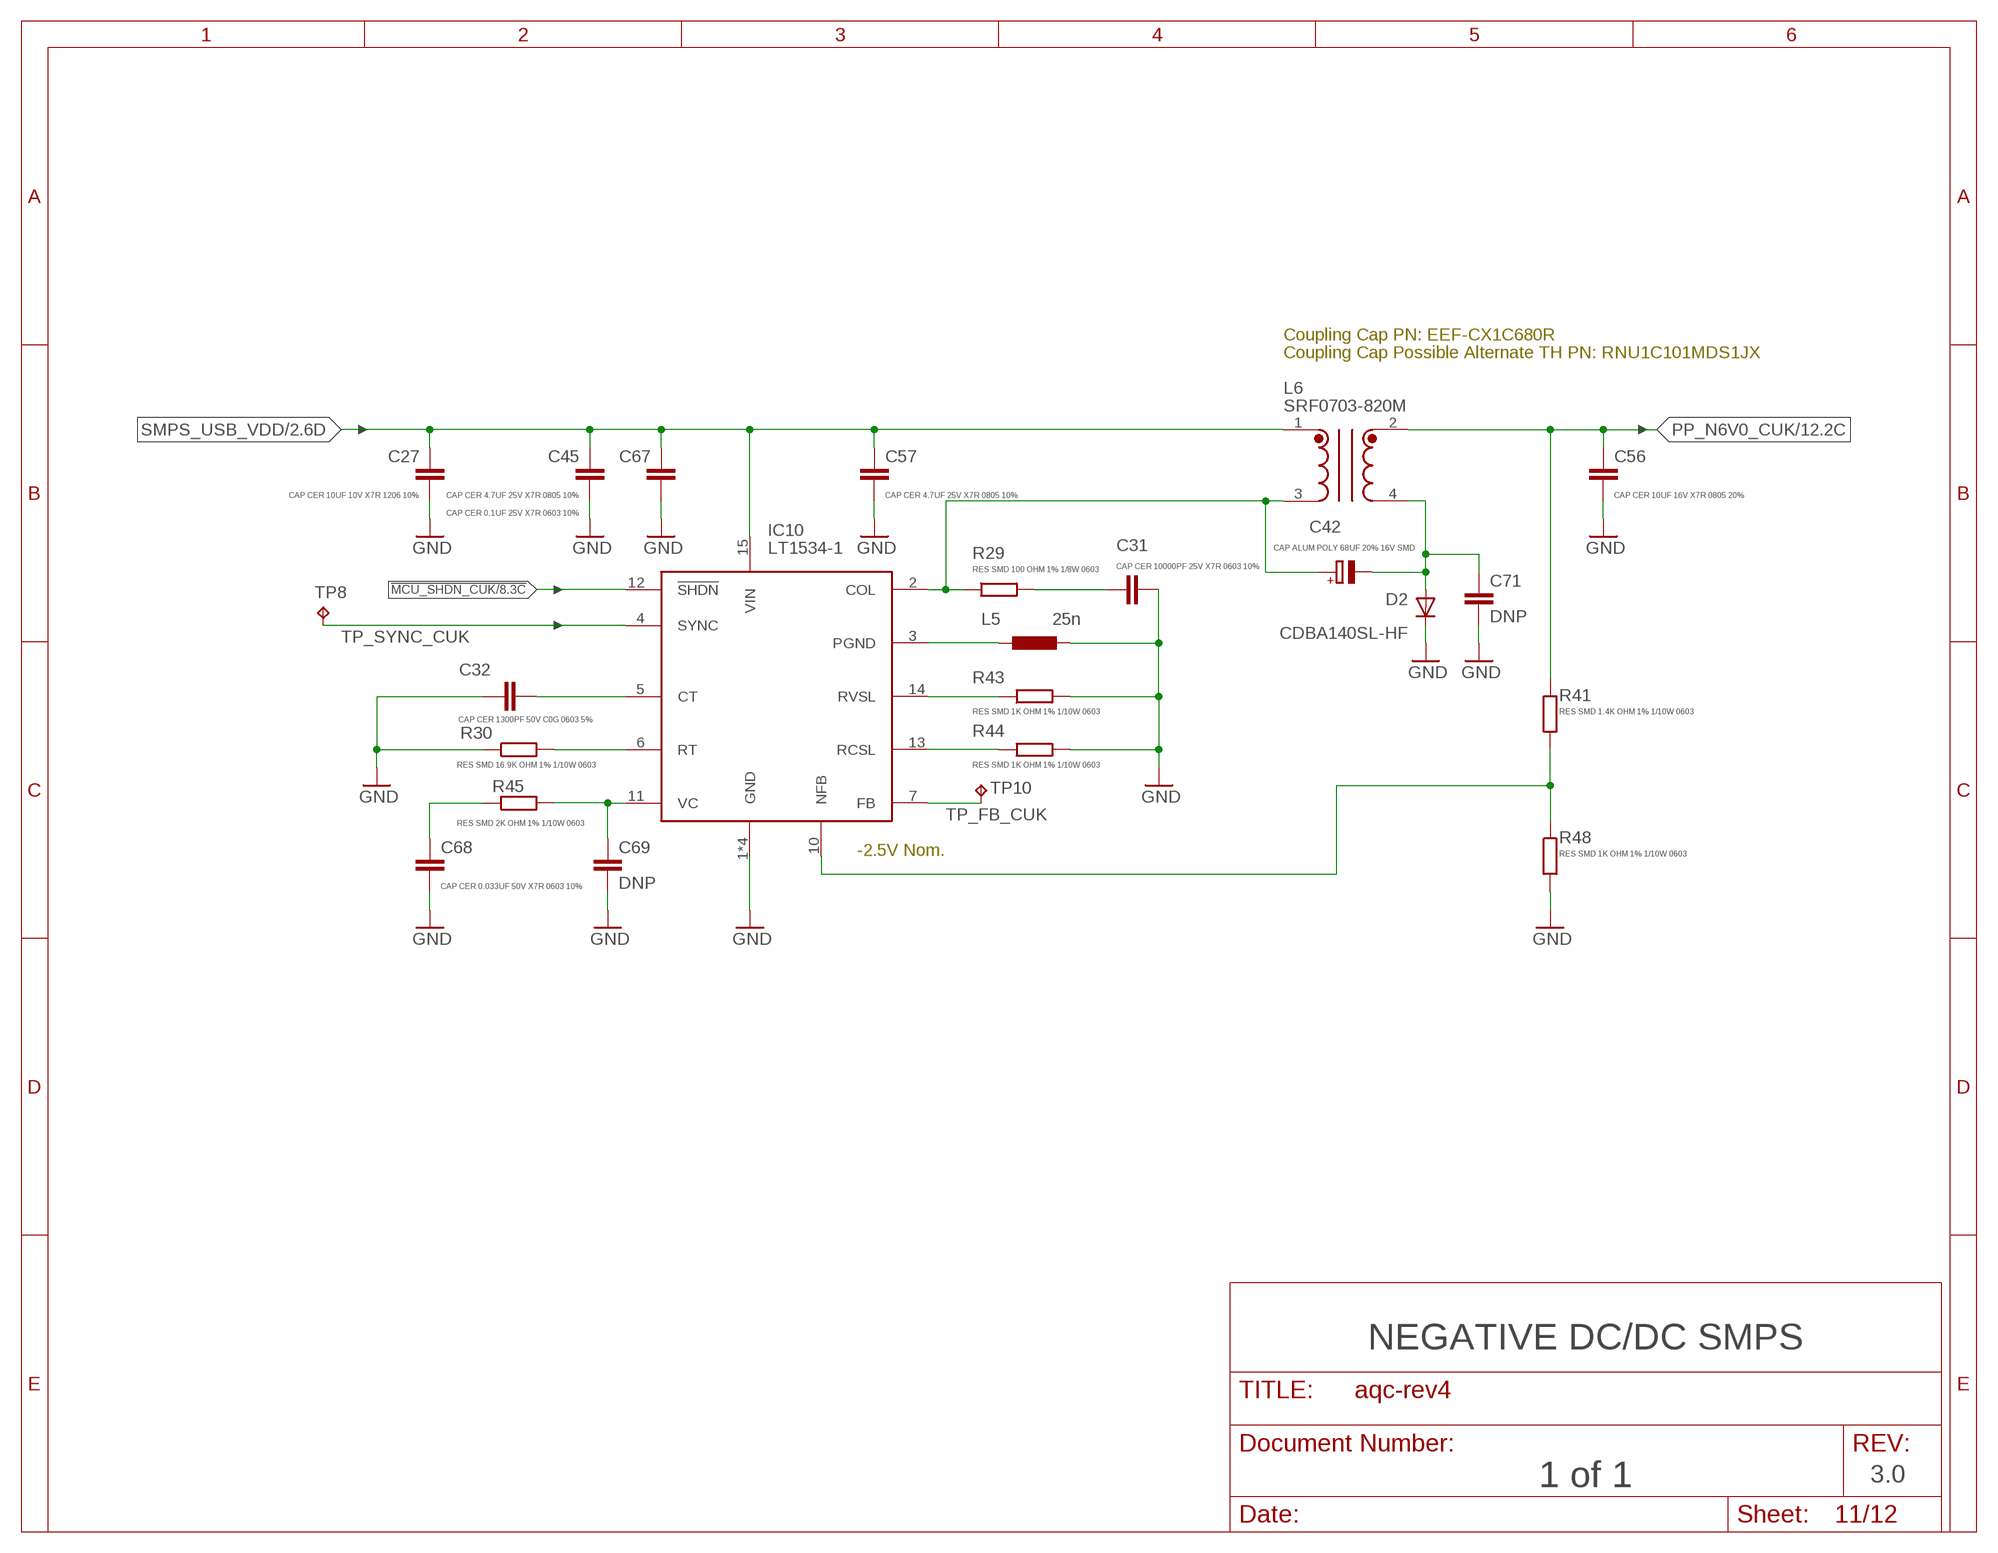
[diagram p10: schematic, sheet 11]
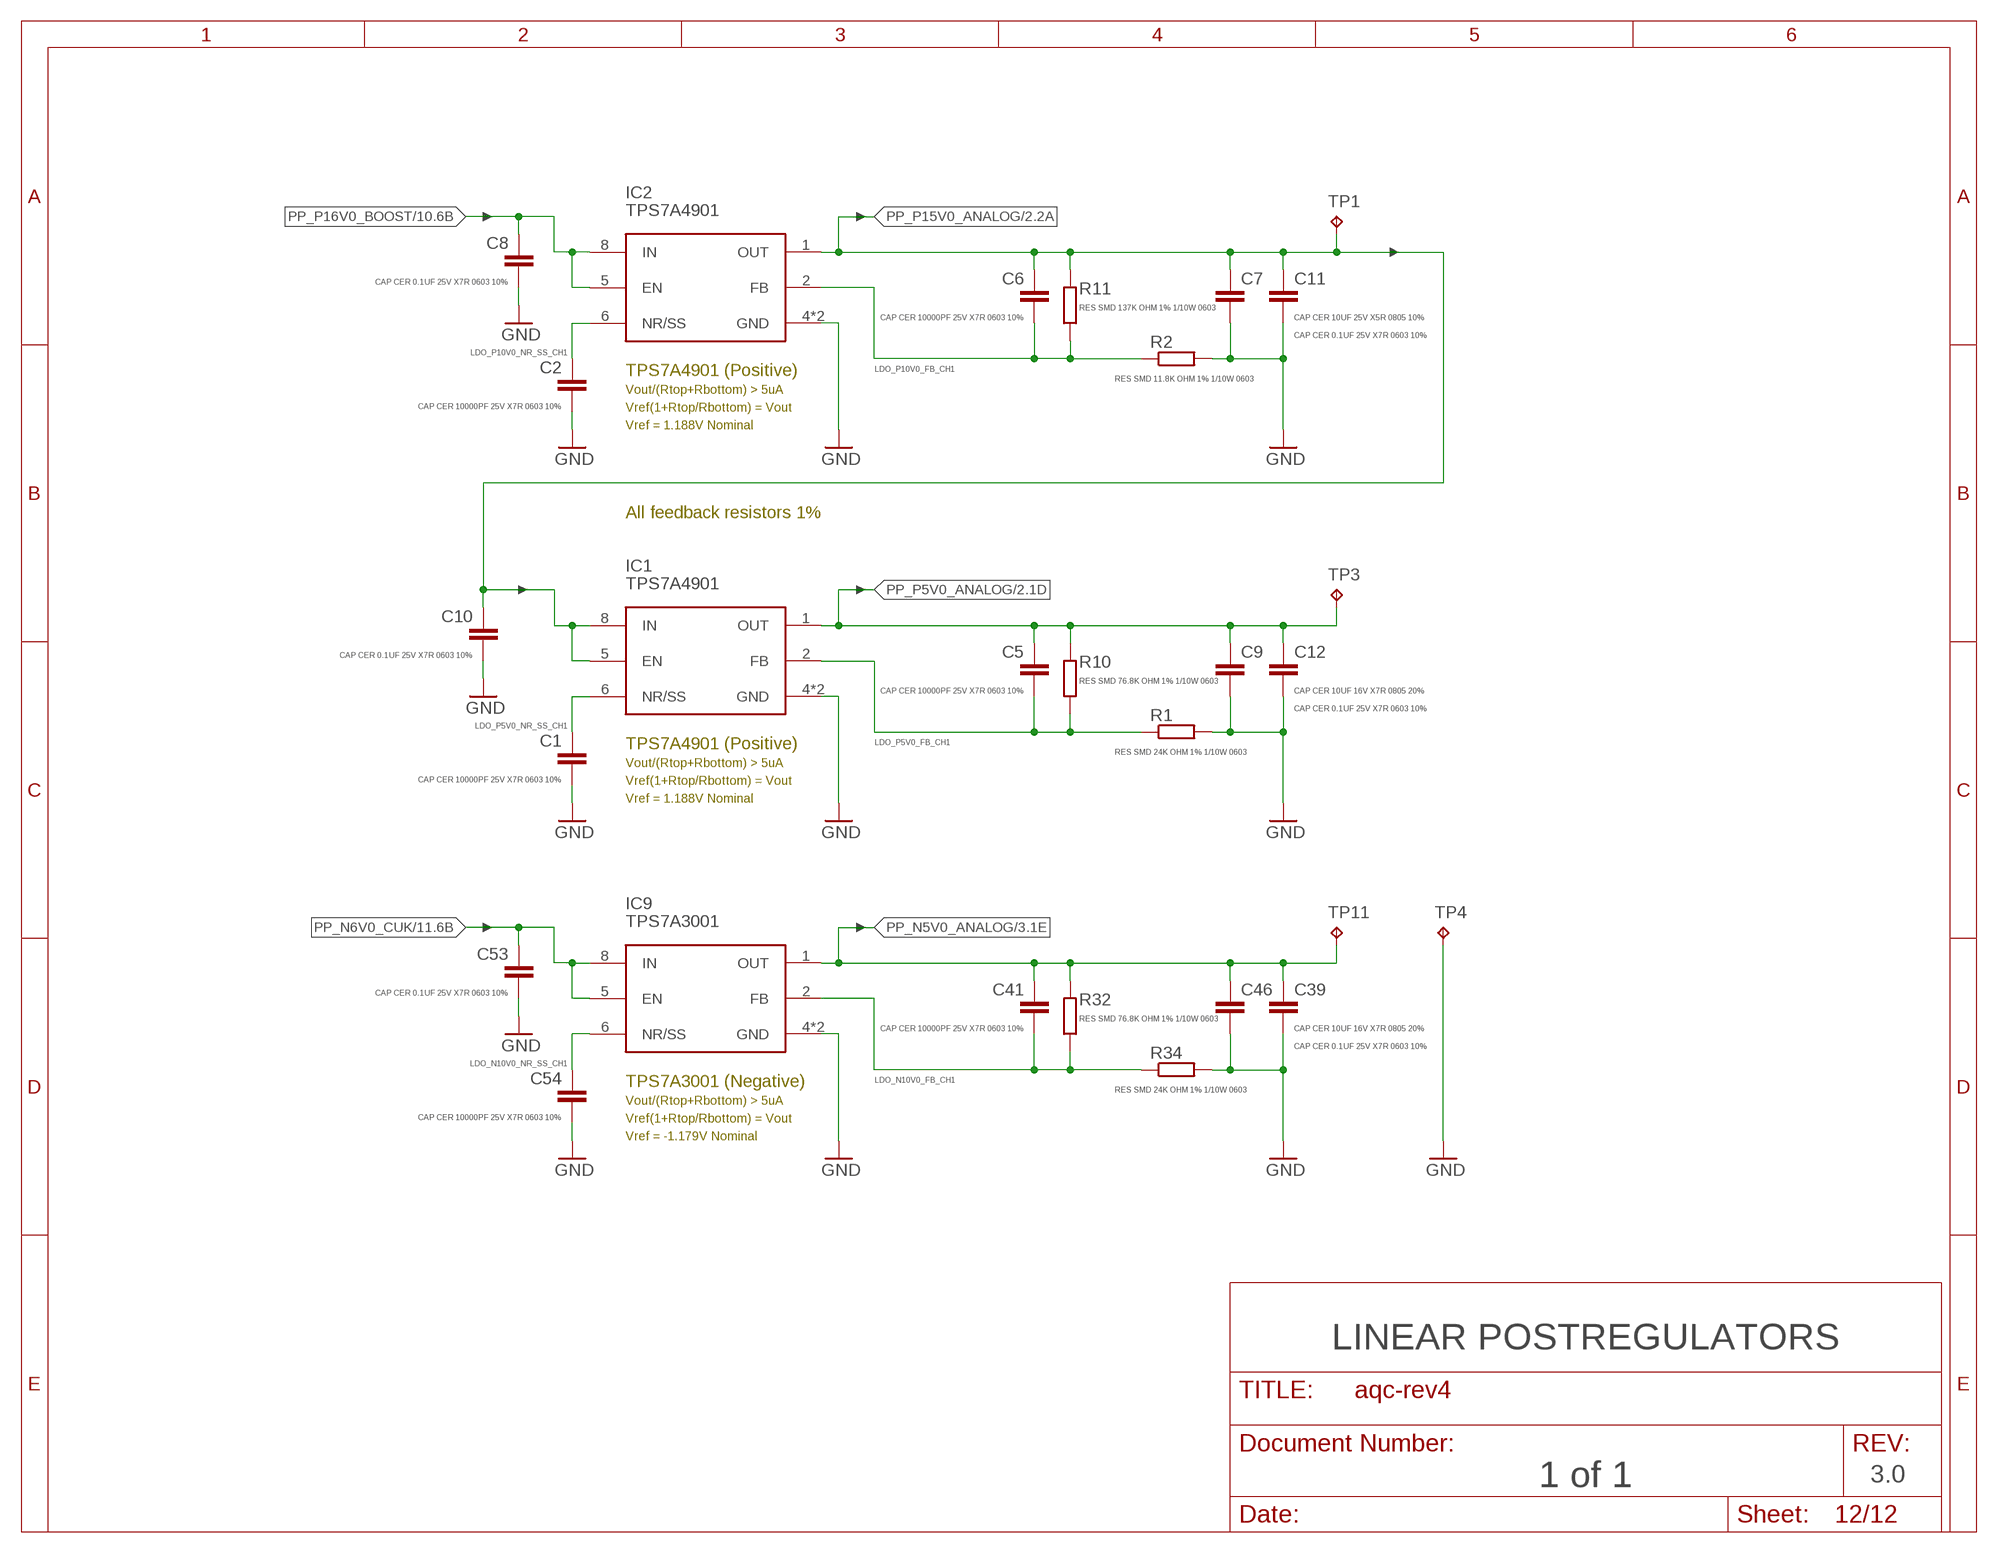
[diagram p11: schematic, sheet 12]

(export (version "E")
  (design (tool "Eeschema 10.0.6"))
  (components
    (comp (ref "C26")
      (value "CAP ALUM POLY 47UF 20% 20V SMD")
      (footprint "eagle-import:CT7343")
      (libsource (lib "eagle-import") (part "CPOL-EUCT7343"))
    )
    (comp (ref "C79")
      (value "CAP CER 0.1UF 25V X7R 0603 10%")
      (footprint "eagle-import:C0603")
      (libsource (lib "eagle-import") (part "C-EUC0603"))
    )
    (comp (ref "C95")
      (value "CAP CER 0.1UF 10V X7R 0402 10%")
      (footprint "eagle-import:C0402")
      (libsource (lib "eagle-import") (part "C-EUC0402"))
    )
    (comp (ref "C97")
      (value "CAP CER 10000PF 10V X7R 0402 10%")
      (footprint "eagle-import:C0402")
      (libsource (lib "eagle-import") (part "C-EUC0402"))
    )
    (comp (ref "C98")
      (value "CAP CER 47PF 16V C0G 0402 5%")
      (footprint "eagle-import:C0402")
      (libsource (lib "eagle-import") (part "C-EUC0402"))
    )
    (comp (ref "C101")
      (value "CAP CER 47PF 16V C0G 0402 5%")
      (footprint "eagle-import:C0402")
      (libsource (lib "eagle-import") (part "C-EUC0402"))
    )
    (comp (ref "C105")
      (value "CAP CER 10000PF 25V X7R 0603 10%")
      (footprint "eagle-import:C0603")
      (libsource (lib "eagle-import") (part "C-EUC0603"))
    )
    (comp (ref "C106")
      (value "CAP CER 0.1UF 25V X7R 0603 10%")
      (footprint "eagle-import:C0603")
      (libsource (lib "eagle-import") (part "C-EUC0603"))
    )
    (comp (ref "C107")
      (value "CAP CER 0.1UF 25V X7R 0603 10%")
      (footprint "eagle-import:C0603")
      (libsource (lib "eagle-import") (part "C-EUC0603"))
    )
    (comp (ref "C108")
      (value "CAP CER 4.7UF 6.3V X7R 0603 10%")
      (footprint "eagle-import:C0603")
      (libsource (lib "eagle-import") (part "C-EUC0603"))
    )
    (comp (ref "H1")
      (value "MOUNT-PAD-ROUND3.2")
      (footprint "eagle-import:3,2-PAD")
      (libsource (lib "eagle-import") (part "MOUNT-PAD-ROUND3.2"))
    )
    (comp (ref "H2")
      (value "MOUNT-PAD-ROUND3.2")
      (footprint "eagle-import:3,2-PAD")
      (libsource (lib "eagle-import") (part "MOUNT-PAD-ROUND3.2"))
    )
    (comp (ref "H3")
      (value "MOUNT-PAD-ROUND3.2")
      (footprint "eagle-import:3,2-PAD")
      (libsource (lib "eagle-import") (part "MOUNT-PAD-ROUND3.2"))
    )
    (comp (ref "H4")
      (value "MOUNT-PAD-ROUND3.2")
      (footprint "eagle-import:3,2-PAD")
      (libsource (lib "eagle-import") (part "MOUNT-PAD-ROUND3.2"))
    )
    (comp (ref "IC29")
      (value "USBLC6-2SC6Y")
      (footprint "eagle-import:SOT23-6L")
      (libsource (lib "eagle-import") (part "USBLC6"))
    )
    (comp (ref "IC32")
      (value "LM1117")
      (footprint "eagle-import:SOT-223")
      (libsource (lib "eagle-import") (part "LM1117"))
    )
    (comp (ref "L8")
      (value "MI0805J102R-10")
      (footprint "eagle-import:R0805")
      (libsource (lib "eagle-import") (part "INDUCTOR0805"))
    )
    (comp (ref "L10")
      (value "MI0805J102R-10")
      (footprint "eagle-import:R0805")
      (libsource (lib "eagle-import") (part "INDUCTOR0805"))
    )
    (comp (ref "Q1")
      (value "DMG2305UX-13")
      (footprint "eagle-import:SOT23-WIDE")
      (libsource (lib "eagle-import") (part "MOSFET-PWIDE"))
    )
    (comp (ref "R58")
      (value "RES SMD 4.7K OHM 1% 1/10W 0603")
      (footprint "eagle-import:R0603")
      (libsource (lib "eagle-import") (part "resistor_R-EU_R0603"))
    )
    (comp (ref "R62")
      (value "RES SMD 100K OHM 1% 1/10W 0603")
      (footprint "eagle-import:R0603")
      (libsource (lib "eagle-import") (part "resistor_R-EU_R0603"))
    )
    (comp (ref "R67")
      (value "RES SMD 22 OHM 1% 1/10W 0402")
      (footprint "eagle-import:R0402")
      (libsource (lib "eagle-import") (part "resistor_R-EU_R0402"))
    )
    (comp (ref "R70")
      (value "RES SMD 22 OHM 1% 1/10W 0402")
      (footprint "eagle-import:R0402")
      (libsource (lib "eagle-import") (part "resistor_R-EU_R0402"))
    )
    (comp (ref "TP23")
      (value "TPTP15R")
      (footprint "eagle-import:TP15R")
      (libsource (lib "eagle-import") (part "TPTP15R"))
    )
    (comp (ref "X3")
      (value "KEYSTONE-7774")
      (footprint "eagle-import:KEYSTONE-7774")
      (libsource (lib "eagle-import") (part "KEYSTONE-7774"))
    )
    (comp (ref "X6")
      (value "KEYSTONE-7774")
      (footprint "eagle-import:KEYSTONE-7774")
      (libsource (lib "eagle-import") (part "KEYSTONE-7774"))
    )
    (comp (ref "X8")
      (value "61729-0010BLF")
      (footprint "eagle-import:PN61729-S")
      (libsource (lib "eagle-import") (part "PN61729-S"))
    )
    (comp (ref "DNP1000")
      (value "RLE_LOGO")
      (footprint "eagle-import:RLE_LOGO")
      (libsource (lib "eagle-import") (part "RLE_LOGO"))
    )
    (comp (ref "C27")
      (value "CAP CER 10UF 10V X7R 1206 10%")
      (footprint "eagle-import:C1206")
      (libsource (lib "eagle-import") (part "C-EUC1206"))
    )
    (comp (ref "C31")
      (value "CAP CER 10000PF 25V X7R 0603 10%")
      (footprint "eagle-import:C0603")
      (libsource (lib "eagle-import") (part "C-EUC0603"))
    )
    (comp (ref "C32")
      (value "CAP CER 1300PF 50V C0G 0603 5%")
      (footprint "eagle-import:C0603")
      (libsource (lib "eagle-import") (part "C-EUC0603"))
    )
    (comp (ref "C42")
      (value "CAP ALUM POLY 68UF 20% 16V SMD")
      (footprint "eagle-import:CT7343")
      (libsource (lib "eagle-import") (part "CPOL-EUCT7343"))
    )
    (comp (ref "C45")
      (value "CAP CER 4.7UF 25V X7R 0805 10%")
      (footprint "eagle-import:C0805")
      (libsource (lib "eagle-import") (part "C-EUC0805"))
    )
    (comp (ref "C56")
      (value "CAP CER 10UF 16V X7R 0805 20%")
      (footprint "eagle-import:C0805")
      (libsource (lib "eagle-import") (part "C-EUC0805"))
    )
    (comp (ref "C57")
      (value "CAP CER 4.7UF 25V X7R 0805 10%")
      (footprint "eagle-import:C0805")
      (libsource (lib "eagle-import") (part "C-EUC0805"))
    )
    (comp (ref "C67")
      (value "CAP CER 0.1UF 25V X7R 0603 10%")
      (footprint "eagle-import:C0603")
      (libsource (lib "eagle-import") (part "C-EUC0603"))
    )
    (comp (ref "C68")
      (value "CAP CER 0.033UF 50V X7R 0603 10%")
      (footprint "eagle-import:C0603")
      (libsource (lib "eagle-import") (part "C-EUC0603"))
    )
    (comp (ref "C69")
      (value "DNP")
      (footprint "eagle-import:C0603")
      (libsource (lib "eagle-import") (part "C-EUC0603"))
    )
    (comp (ref "C71")
      (value "DNP")
      (footprint "eagle-import:C0603")
      (libsource (lib "eagle-import") (part "C-EUC0603"))
    )
    (comp (ref "D2")
      (value "CDBA140SL-HF")
      (footprint "eagle-import:DO214AC")
      (libsource (lib "eagle-import") (part "DIODE-DO214AC"))
    )
    (comp (ref "IC10")
      (value "LT1534-1")
      (footprint "eagle-import:SO16")
      (libsource (lib "eagle-import") (part "LT1534"))
    )
    (comp (ref "L5")
      (value "25n")
      (footprint "eagle-import:R0603")
      (libsource (lib "eagle-import") (part "INDUCTOR0603"))
    )
    (comp (ref "L6")
      (value "SRF0703-820M")
      (footprint "eagle-import:SRF0703")
      (libsource (lib "eagle-import") (part "SRF0703"))
    )
    (comp (ref "R29")
      (value "RES SMD 100 OHM 1% 1/8W 0603")
      (footprint "eagle-import:R0603")
      (libsource (lib "eagle-import") (part "resistor_R-EU_R0603"))
    )
    (comp (ref "R30")
      (value "RES SMD 16.9K OHM 1% 1/10W 0603")
      (footprint "eagle-import:R0603")
      (libsource (lib "eagle-import") (part "R-EU_R0603"))
    )
    (comp (ref "R41")
      (value "RES SMD 1.4K OHM 1% 1/10W 0603")
      (footprint "eagle-import:R0603")
      (libsource (lib "eagle-import") (part "resistor_R-EU_R0603"))
    )
    (comp (ref "R43")
      (value "RES SMD 1K OHM 1% 1/10W 0603")
      (footprint "eagle-import:R0603")
      (libsource (lib "eagle-import") (part "resistor_R-EU_R0603"))
    )
    (comp (ref "R44")
      (value "RES SMD 1K OHM 1% 1/10W 0603")
      (footprint "eagle-import:R0603")
      (libsource (lib "eagle-import") (part "resistor_R-EU_R0603"))
    )
    (comp (ref "R45")
      (value "RES SMD 2K OHM 1% 1/10W 0603")
      (footprint "eagle-import:R0603")
      (libsource (lib "eagle-import") (part "R-EU_R0603"))
    )
    (comp (ref "R48")
      (value "RES SMD 1K OHM 1% 1/10W 0603")
      (footprint "eagle-import:R0603")
      (libsource (lib "eagle-import") (part "resistor_R-EU_R0603"))
    )
    (comp (ref "TP8")
      (value "TPB1,27")
      (footprint "eagle-import:B1,27")
      (libsource (lib "eagle-import") (part "TPB1,27"))
    )
    (comp (ref "TP10")
      (value "TPB1,27")
      (footprint "eagle-import:B1,27")
      (libsource (lib "eagle-import") (part "TPB1,27"))
    )
    (comp (ref "C16")
      (value "CAP CER 0.1UF 25V X7R 0603 10%")
      (footprint "eagle-import:C0603")
      (libsource (lib "eagle-import") (part "rcl-modified-footprints_C-EUC0603"))
    )
    (comp (ref "C20")
      (value "CAP CER 0.1UF 25V X7R 0603 10%")
      (footprint "eagle-import:C0603")
      (libsource (lib "eagle-import") (part "rcl-modified-footprints_C-EUC0603"))
    )
    (comp (ref "C22")
      (value "CAP CER 4.7UF 6.3V X7R 0603 10%")
      (footprint "eagle-import:C0603")
      (libsource (lib "eagle-import") (part "rcl-modified-footprints_C-EUC0603"))
    )
    (comp (ref "C102")
      (value "CAP CER 0.1UF 25V X7R 0603 10%")
      (footprint "eagle-import:C0603")
      (libsource (lib "eagle-import") (part "C-EUC0603"))
    )
    (comp (ref "C103")
      (value "CAP CER 4.7UF 6.3V X7R 0603 10%")
      (footprint "eagle-import:C0603")
      (libsource (lib "eagle-import") (part "C-EUC0603"))
    )
    (comp (ref "C110")
      (value "CAP CER 0.1UF 25V X7R 0603 10%")
      (footprint "eagle-import:C0603")
      (libsource (lib "eagle-import") (part "C-EUC0603"))
    )
    (comp (ref "IC31")
      (value "MAX5725")
      (footprint "eagle-import:TSSOP20")
      (libsource (lib "eagle-import") (part "MAX572X"))
    )
    (comp (ref "L4")
      (value "PE-0603FB601ST")
      (footprint "eagle-import:R0603")
      (libsource (lib "eagle-import") (part "INDUCTOR0603"))
    )
    (comp (ref "L9")
      (value "PE-0603FB601ST")
      (footprint "eagle-import:R0603")
      (libsource (lib "eagle-import") (part "INDUCTOR0603"))
    )
    (comp (ref "R12")
      (value "RES SMD 2.2K OHM 1% 1/10W 0603")
      (footprint "eagle-import:R0603")
      (libsource (lib "eagle-import") (part "rcl-modified-footprints_R-EU_R0603"))
    )
    (comp (ref "R13")
      (value "RES SMD 2.2K OHM 1% 1/10W 0603")
      (footprint "eagle-import:R0603")
      (libsource (lib "eagle-import") (part "rcl-modified-footprints_R-EU_R0603"))
    )
    (comp (ref "R17")
      (value "DNP")
      (footprint "eagle-import:R0603")
      (libsource (lib "eagle-import") (part "rcl-modified-footprints_R-EU_R0603"))
    )
    (comp (ref "R18")
      (value "RES SMD 1K OHM 1% 1/10W 0603")
      (footprint "eagle-import:R0603")
      (libsource (lib "eagle-import") (part "rcl-modified-footprints_R-EU_R0603"))
    )
    (comp (ref "R19")
      (value "DNP")
      (footprint "eagle-import:R0603")
      (libsource (lib "eagle-import") (part "rcl-modified-footprints_R-EU_R0603"))
    )
    (comp (ref "R73")
      (value "RES SMD 0 OHM JUMPER 0603")
      (footprint "eagle-import:R0603")
      (libsource (lib "eagle-import") (part "R-EU_R0603"))
    )
    (comp (ref "TP5")
      (value "GND")
      (footprint "eagle-import:KEYSTONE_5000_MINIATURE")
      (libsource (lib "eagle-import") (part "KEYSTONE_5000"))
    )
    (comp (ref "TP6")
      (value "VREF_AV_DET")
      (footprint "eagle-import:KEYSTONE_5000_MINIATURE")
      (libsource (lib "eagle-import") (part "KEYSTONE_5000"))
    )
    (comp (ref "TP14")
      (value "DELTA_V")
      (footprint "eagle-import:KEYSTONE_5000_MINIATURE")
      (libsource (lib "eagle-import") (part "KEYSTONE_5000"))
    )
    (comp (ref "TP15")
      (value "DMND_IBIAS")
      (footprint "eagle-import:KEYSTONE_5000_MINIATURE")
      (libsource (lib "eagle-import") (part "KEYSTONE_5000"))
    )
    (comp (ref "TP16")
      (value "OS_COMP")
      (footprint "eagle-import:KEYSTONE_5000_MINIATURE")
      (libsource (lib "eagle-import") (part "KEYSTONE_5000"))
    )
    (comp (ref "TP17")
      (value "V_A")
      (footprint "eagle-import:KEYSTONE_5000_MINIATURE")
      (libsource (lib "eagle-import") (part "KEYSTONE_5000"))
    )
    (comp (ref "TP18")
      (value "OS_CCS")
      (footprint "eagle-import:KEYSTONE_5000_MINIATURE")
      (libsource (lib "eagle-import") (part "KEYSTONE_5000"))
    )
    (comp (ref "TP19")
      (value "EXTRA_1")
      (footprint "eagle-import:KEYSTONE_5000_MINIATURE")
      (libsource (lib "eagle-import") (part "KEYSTONE_5000"))
    )
    (comp (ref "TP20")
      (value "EXTRA_2")
      (footprint "eagle-import:KEYSTONE_5000_MINIATURE")
      (libsource (lib "eagle-import") (part "KEYSTONE_5000"))
    )
    (comp (ref "TP21")
      (value "EXTRA_3")
      (footprint "eagle-import:KEYSTONE_5000_MINIATURE")
      (libsource (lib "eagle-import") (part "KEYSTONE_5000"))
    )
    (comp (ref "TP22")
      (value "GND")
      (footprint "eagle-import:KEYSTONE_5000_MINIATURE")
      (libsource (lib "eagle-import") (part "KEYSTONE_5000"))
    )
    (comp (ref "U1")
      (value "MCP4725")
      (footprint "eagle-import:SOT23-6")
      (libsource (lib "eagle-import") (part "DAC_MCP4725"))
    )
    (comp (ref "C1")
      (value "CAP CER 10000PF 25V X7R 0603 10%")
      (footprint "eagle-import:C0603")
      (libsource (lib "eagle-import") (part "rcl-modified-footprints_C-EUC0603"))
    )
    (comp (ref "C2")
      (value "CAP CER 10000PF 25V X7R 0603 10%")
      (footprint "eagle-import:C0603")
      (libsource (lib "eagle-import") (part "rcl-modified-footprints_C-EUC0603"))
    )
    (comp (ref "C5")
      (value "CAP CER 10000PF 25V X7R 0603 10%")
      (footprint "eagle-import:C0603")
      (libsource (lib "eagle-import") (part "rcl-modified-footprints_C-EUC0603"))
    )
    (comp (ref "C6")
      (value "CAP CER 10000PF 25V X7R 0603 10%")
      (footprint "eagle-import:C0603")
      (libsource (lib "eagle-import") (part "rcl-modified-footprints_C-EUC0603"))
    )
    (comp (ref "C7")
      (value "CAP CER 0.1UF 25V X7R 0603 10%")
      (footprint "eagle-import:C0603")
      (libsource (lib "eagle-import") (part "rcl-modified-footprints_C-EUC0603"))
    )
    (comp (ref "C8")
      (value "CAP CER 0.1UF 25V X7R 0603 10%")
      (footprint "eagle-import:C0603")
      (libsource (lib "eagle-import") (part "rcl-modified-footprints_C-EUC0603"))
    )
    (comp (ref "C9")
      (value "CAP CER 0.1UF 25V X7R 0603 10%")
      (footprint "eagle-import:C0603")
      (libsource (lib "eagle-import") (part "rcl-modified-footprints_C-EUC0603"))
    )
    (comp (ref "C10")
      (value "CAP CER 0.1UF 25V X7R 0603 10%")
      (footprint "eagle-import:C0603")
      (libsource (lib "eagle-import") (part "rcl-modified-footprints_C-EUC0603"))
    )
    (comp (ref "C11")
      (value "CAP CER 10UF 25V X5R 0805 10%")
      (footprint "eagle-import:C0805")
      (libsource (lib "eagle-import") (part "C-EUC0805"))
    )
    (comp (ref "C12")
      (value "CAP CER 10UF 16V X7R 0805 20%")
      (footprint "eagle-import:C0805")
      (libsource (lib "eagle-import") (part "C-EUC0805"))
    )
    (comp (ref "C39")
      (value "CAP CER 10UF 16V X7R 0805 20%")
      (footprint "eagle-import:C0805")
      (libsource (lib "eagle-import") (part "C-EUC0805"))
    )
    (comp (ref "C41")
      (value "CAP CER 10000PF 25V X7R 0603 10%")
      (footprint "eagle-import:C0603")
      (libsource (lib "eagle-import") (part "rcl-modified-footprints_C-EUC0603"))
    )
    (comp (ref "C46")
      (value "CAP CER 0.1UF 25V X7R 0603 10%")
      (footprint "eagle-import:C0603")
      (libsource (lib "eagle-import") (part "rcl-modified-footprints_C-EUC0603"))
    )
    (comp (ref "C53")
      (value "CAP CER 0.1UF 25V X7R 0603 10%")
      (footprint "eagle-import:C0603")
      (libsource (lib "eagle-import") (part "rcl-modified-footprints_C-EUC0603"))
    )
    (comp (ref "C54")
      (value "CAP CER 10000PF 25V X7R 0603 10%")
      (footprint "eagle-import:C0603")
      (libsource (lib "eagle-import") (part "rcl-modified-footprints_C-EUC0603"))
    )
    (comp (ref "IC1")
      (value "TPS7A4901")
      (footprint "eagle-import:MSOP-8_POWER_PAD")
      (libsource (lib "eagle-import") (part "TPS7A"))
    )
    (comp (ref "IC2")
      (value "TPS7A4901")
      (footprint "eagle-import:MSOP-8_POWER_PAD")
      (libsource (lib "eagle-import") (part "TPS7A"))
    )
    (comp (ref "IC9")
      (value "TPS7A3001")
      (footprint "eagle-import:MSOP-8_POWER_PAD")
      (libsource (lib "eagle-import") (part "TPS7A"))
    )
    (comp (ref "R1")
      (value "RES SMD 24K OHM 1% 1/10W 0603")
      (footprint "eagle-import:R0603")
      (libsource (lib "eagle-import") (part "rcl-modified-footprints_R-EU_R0603"))
    )
    (comp (ref "R2")
      (value "RES SMD 11.8K OHM 1% 1/10W 0603")
      (footprint "eagle-import:R0603")
      (libsource (lib "eagle-import") (part "rcl-modified-footprints_R-EU_R0603"))
    )
    (comp (ref "R10")
      (value "RES SMD 76.8K OHM 1% 1/10W 0603")
      (footprint "eagle-import:R0603")
      (libsource (lib "eagle-import") (part "rcl-modified-footprints_R-EU_R0603"))
    )
    (comp (ref "R11")
      (value "RES SMD 137K OHM 1% 1/10W 0603")
      (footprint "eagle-import:R0603")
      (libsource (lib "eagle-import") (part "rcl-modified-footprints_R-EU_R0603"))
    )
    (comp (ref "R32")
      (value "RES SMD 76.8K OHM 1% 1/10W 0603")
      (footprint "eagle-import:R0603")
      (libsource (lib "eagle-import") (part "rcl-modified-footprints_R-EU_R0603"))
    )
    (comp (ref "R34")
      (value "RES SMD 24K OHM 1% 1/10W 0603")
      (footprint "eagle-import:R0603")
      (libsource (lib "eagle-import") (part "rcl-modified-footprints_R-EU_R0603"))
    )
    (comp (ref "TP1")
      (value "TPTP15R")
      (footprint "eagle-import:TP15R")
      (libsource (lib "eagle-import") (part "TPTP15R"))
    )
    (comp (ref "TP3")
      (value "TPTP15R")
      (footprint "eagle-import:TP15R")
      (libsource (lib "eagle-import") (part "TPTP15R"))
    )
    (comp (ref "TP4")
      (value "TPTP15R")
      (footprint "eagle-import:TP15R")
      (libsource (lib "eagle-import") (part "TPTP15R"))
    )
    (comp (ref "TP11")
      (value "TPTP15R")
      (footprint "eagle-import:TP15R")
      (libsource (lib "eagle-import") (part "TPTP15R"))
    )
    (comp (ref "C3")
      (value "CAP CER 1000PF 50V X7R 0603 10%")
      (footprint "eagle-import:C0603")
      (libsource (lib "eagle-import") (part "C-EUC0603"))
    )
    (comp (ref "C4")
      (value "CAP CER 1300PF 50V C0G 0603 5%")
      (footprint "eagle-import:C0603")
      (libsource (lib "eagle-import") (part "C-EUC0603"))
    )
    (comp (ref "C13")
      (value "CAP ALUM POLY 47UF 20% 20V SMD")
      (footprint "eagle-import:CT7343")
      (libsource (lib "eagle-import") (part "CPOL-EUCT7343"))
    )
    (comp (ref "C14")
      (value "CAP ALUM POLY 47UF 20% 20V SMD")
      (footprint "eagle-import:CT7343")
      (libsource (lib "eagle-import") (part "CPOL-EUCT7343"))
    )
    (comp (ref "C15")
      (value "CAP CER 4.7UF 25V X7R 0805 10%")
      (footprint "eagle-import:C0805")
      (libsource (lib "eagle-import") (part "C-EUC0805"))
    )
    (comp (ref "C17")
      (value "CAP CER 0.1UF 25V X7R 0603 10%")
      (footprint "eagle-import:C0603")
      (libsource (lib "eagle-import") (part "C-EUC0603"))
    )
    (comp (ref "C18")
      (value "CAP CER 0.015UF 50V X7R 0603 10%")
      (footprint "eagle-import:C0603")
      (libsource (lib "eagle-import") (part "C-EUC0603"))
    )
    (comp (ref "C19")
      (value "CAP CER 220PF 50V C0G 0603 5%")
      (footprint "eagle-import:C0603")
      (libsource (lib "eagle-import") (part "C-EUC0603"))
    )
    (comp (ref "C25")
      (value "CAP ALUM POLY 47UF 20% 20V SMD")
      (footprint "eagle-import:CT7343")
      (libsource (lib "eagle-import") (part "CPOL-EUCT7343"))
    )
    (comp (ref "D1")
      (value "CDBA140SL-HF")
      (footprint "eagle-import:DO214AC")
      (libsource (lib "eagle-import") (part "DIODE-DO214AC"))
    )
    (comp (ref "IC3")
      (value "LT1534-1")
      (footprint "eagle-import:SO16")
      (libsource (lib "eagle-import") (part "LT1534"))
    )
    (comp (ref "L1")
      (value "25n")
      (footprint "eagle-import:R0603")
      (libsource (lib "eagle-import") (part "INDUCTOR0603"))
    )
    (comp (ref "L2")
      (value "Wurth-7447709471")
      (footprint "eagle-import:WE_INDUCTOR_SIZE_CODE_1210")
      (libsource (lib "eagle-import") (part "WE_INDUCTOR"))
    )
    (comp (ref "L3")
      (value "SRF0703-820M")
      (footprint "eagle-import:SRF0703")
      (libsource (lib "eagle-import") (part "SRF0703"))
    )
    (comp (ref "R3")
      (value "RES SMD 0 OHM JUMPER 0603")
      (footprint "eagle-import:R0603")
      (libsource (lib "eagle-import") (part "rcl-modified-footprints_R-EU_R0603"))
    )
    (comp (ref "R4")
      (value "DNP")
      (footprint "eagle-import:R0603")
      (libsource (lib "eagle-import") (part "rcl-modified-footprints_R-EU_R0603"))
    )
    (comp (ref "R5")
      (value "RES SMD 29.4K OHM 1% 1/10W 0603")
      (footprint "eagle-import:R0603")
      (libsource (lib "eagle-import") (part "rcl-modified-footprints_R-EU_R0603"))
    )
    (comp (ref "R6")
      (value "RES SMD 2.49K OHM 1% 1/10W 0603")
      (footprint "eagle-import:R0603")
      (libsource (lib "eagle-import") (part "rcl-modified-footprints_R-EU_R0603"))
    )
    (comp (ref "R7")
      (value "RES SMD 10 OHM 1% 1/10W 0603")
      (footprint "eagle-import:R0603")
      (libsource (lib "eagle-import") (part "resistor_R-EU_R0603"))
    )
    (comp (ref "R8")
      (value "RES SMD 16.9K OHM 1% 1/10W 0603")
      (footprint "eagle-import:R0603")
      (libsource (lib "eagle-import") (part "resistor_R-EU_R0603"))
    )
    (comp (ref "R9")
      (value "DNP")
      (footprint "eagle-import:R0603")
      (libsource (lib "eagle-import") (part "rcl-modified-footprints_R-EU_R0603"))
    )
    (comp (ref "R14")
      (value "RES SMD 1K OHM 1% 1/10W 0603")
      (footprint "eagle-import:R0603")
      (libsource (lib "eagle-import") (part "resistor_R-EU_R0603"))
    )
    (comp (ref "R15")
      (value "RES SMD 1K OHM 1% 1/10W 0603")
      (footprint "eagle-import:R0603")
      (libsource (lib "eagle-import") (part "resistor_R-EU_R0603"))
    )
    (comp (ref "R16")
      (value "RES SMD 6.8K OHM 1% 1/10W 0603")
      (footprint "eagle-import:R0603")
      (libsource (lib "eagle-import") (part "resistor_R-EU_R0603"))
    )
    (comp (ref "TP2")
      (value "TPB1,27")
      (footprint "eagle-import:B1,27")
      (libsource (lib "eagle-import") (part "TPB1,27"))
    )
    (comp (ref "TP7")
      (value "TPB1,27")
      (footprint "eagle-import:B1,27")
      (libsource (lib "eagle-import") (part "TPB1,27"))
    )
    (comp (ref "C58")
      (value "CAP CER 0.1UF 10V X7R 0402 10%")
      (footprint "eagle-import:C0402")
      (libsource (lib "eagle-import") (part "rcl-modified-footprints_C-EUC0402"))
    )
    (comp (ref "C59")
      (value "CAP CER 0.1UF 10V X7R 0402 10%")
      (footprint "eagle-import:C0402")
      (libsource (lib "eagle-import") (part "rcl-modified-footprints_C-EUC0402"))
    )
    (comp (ref "C60")
      (value "CAP CER 10000PF 10V X7R 0402 10%")
      (footprint "eagle-import:C0402")
      (libsource (lib "eagle-import") (part "C-EUC0402"))
    )
    (comp (ref "C61")
      (value "CAP CER 0.1UF 10V X7R 0402 10%")
      (footprint "eagle-import:C0402")
      (libsource (lib "eagle-import") (part "C-EUC0402"))
    )
    (comp (ref "C63")
      (value "CAP CER 10000PF 10V X7R 0402 10%")
      (footprint "eagle-import:C0402")
      (libsource (lib "eagle-import") (part "rcl-modified-footprints_C-EUC0402"))
    )
    (comp (ref "C64")
      (value "CAP CER 10000PF 10V X7R 0402 10%")
      (footprint "eagle-import:C0402")
      (libsource (lib "eagle-import") (part "rcl-modified-footprints_C-EUC0402"))
    )
    (comp (ref "C65")
      (value "CAP CER 0.1UF 10V X7R 0402 10%")
      (footprint "eagle-import:C0402")
      (libsource (lib "eagle-import") (part "C-EUC0402"))
    )
    (comp (ref "C66")
      (value "CAP CER 10000PF 10V X7R 0402 10%")
      (footprint "eagle-import:C0402")
      (libsource (lib "eagle-import") (part "C-EUC0402"))
    )
    (comp (ref "C81")
      (value "CAP CER 10000PF 10V X7R 0402 10%")
      (footprint "eagle-import:C0402")
      (libsource (lib "eagle-import") (part "C-EUC0402"))
    )
    (comp (ref "C83")
      (value "CAP CER 0.1UF 10V X7R 0402 10%")
      (footprint "eagle-import:C0402")
      (libsource (lib "eagle-import") (part "C-EUC0402"))
    )
    (comp (ref "C84")
      (value "CAP CER 10000PF 10V X7R 0402 10%")
      (footprint "eagle-import:C0402")
      (libsource (lib "eagle-import") (part "rcl-modified-footprints_C-EUC0402"))
    )
    (comp (ref "C85")
      (value "CAP CER 10000PF 10V X7R 0402 10%")
      (footprint "eagle-import:C0402")
      (libsource (lib "eagle-import") (part "rcl-modified-footprints_C-EUC0402"))
    )
    (comp (ref "C89")
      (value "CAP CER 0.1UF 10V X7R 0402 10%")
      (footprint "eagle-import:C0402")
      (libsource (lib "eagle-import") (part "rcl-modified-footprints_C-EUC0402"))
    )
    (comp (ref "C90")
      (value "CAP CER 0.1UF 10V X7R 0402 10%")
      (footprint "eagle-import:C0402")
      (libsource (lib "eagle-import") (part "rcl-modified-footprints_C-EUC0402"))
    )
    (comp (ref "IC16")
      (value "74AHC1G14DCK")
      (footprint "eagle-import:SC70-5")
      (libsource (lib "eagle-import") (part "741G14DCKAHC"))
    )
    (comp (ref "IC17")
      (value "NL17SZ125")
      (footprint "eagle-import:SC70-5")
      (libsource (lib "eagle-import") (part "741G125DCKAHC"))
    )
    (comp (ref "IC18")
      (value "74AHC1G04DCK")
      (footprint "eagle-import:SC70-5")
      (libsource (lib "eagle-import") (part "741G04DCKAHC"))
    )
    (comp (ref "IC19")
      (value "74AHC1G32DCK")
      (footprint "eagle-import:SC70-5")
      (libsource (lib "eagle-import") (part "741G32DCKAHC"))
    )
    (comp (ref "IC20")
      (value "NC7WZ16P6X")
      (footprint "eagle-import:SC70-6L")
      (libsource (lib "eagle-import") (part "NC7WZ16P6X"))
    )
    (comp (ref "IC21")
      (value "74AHC1G08DCK")
      (footprint "eagle-import:SC70-5")
      (libsource (lib "eagle-import") (part "741G08DCKAHC"))
    )
    (comp (ref "IC22")
      (value "74AHC1G08DCK")
      (footprint "eagle-import:SC70-5")
      (libsource (lib "eagle-import") (part "741G08DCKAHC"))
    )
    (comp (ref "R49")
      (value "RES SMD 49.9 OHM 1% 1/10W 0603")
      (footprint "eagle-import:R0603")
      (libsource (lib "eagle-import") (part "R-EU_R0603"))
    )
    (comp (ref "R52")
      (value "RES SMD 49.9 OHM 1% 1/10W 0603")
      (footprint "eagle-import:R0603")
      (libsource (lib "eagle-import") (part "R-EU_R0603"))
    )
    (comp (ref "X2")
      (value "CONN_FORCE_QUENCH")
      (footprint "eagle-import:J502-ND-142-0701-881_886")
      (fields
        (field (name "MF") "JOHNSON COMPONENTS")
        (field (name "MPN") "142-0701-881")
        (field (name "MF_1") "JOHNSON COMPONENTS")
        (field (name "MPN_1") "142-0711-871")
        (field (name "OC_FARNELL") "unknown")
        (field (name "OC_NEWARK") "01C1639")
      )
      (libsource (lib "eagle-import") (part "SMA-142-0701-881/886"))
    )
    (comp (ref "X5")
      (value "CONN_PHOTON_COUNTER")
      (footprint "eagle-import:J502-ND-142-0701-881_886")
      (fields (field (name "MF") "JOHNSON COMPONENTS") (field (name "MPN") "142-0701-881"))
      (libsource (lib "eagle-import") (part "SMA-142-0701-881/886"))
    )
    (comp (ref "C82")
      (value "CAP CER 10000PF 25V X7R 0603 10%")
      (footprint "eagle-import:C0603")
      (libsource (lib "eagle-import") (part "C-EUC0603"))
    )
    (comp (ref "C86")
      (value "CAP CER 4.7UF 6.3V X7R 0603 10%")
      (footprint "eagle-import:C0603")
      (libsource (lib "eagle-import") (part "C-EUC0603"))
    )
    (comp (ref "C87")
      (value "CAP CER 4.7UF 6.3V X7R 0603 10%")
      (footprint "eagle-import:C0603")
      (libsource (lib "eagle-import") (part "C-EUC0603"))
    )
    (comp (ref "C91")
      (value "CAP CER 0.1UF 25V X7R 0603 10%")
      (footprint "eagle-import:C0603")
      (libsource (lib "eagle-import") (part "C-EUC0603"))
    )
    (comp (ref "C92")
      (value "CAP CER 0.1UF 25V X7R 0603 10%")
      (footprint "eagle-import:C0603")
      (libsource (lib "eagle-import") (part "C-EUC0603"))
    )
    (comp (ref "C96")
      (value "CAP CER 0.1UF 25V X7R 0603 10%")
      (footprint "eagle-import:C0603")
      (libsource (lib "eagle-import") (part "rcl-modified-footprints_C-EUC0603"))
    )
    (comp (ref "C99")
      (value "CAP CER 0.1UF 25V X7R 0603 10%")
      (footprint "eagle-import:C0603")
      (libsource (lib "eagle-import") (part "rcl-modified-footprints_C-EUC0603"))
    )
    (comp (ref "C104")
      (value "CAP CER 0.1UF 25V X7R 0603 10%")
      (footprint "eagle-import:C0603")
      (libsource (lib "eagle-import") (part "rcl-modified-footprints_C-EUC0603"))
    )
    (comp (ref "C109")
      (value "CAP CER 0.1UF 25V X7R 0603 10%")
      (footprint "eagle-import:C0603")
      (libsource (lib "eagle-import") (part "rcl-modified-footprints_C-EUC0603"))
    )
    (comp (ref "C111")
      (value "CAP CER 0.1UF 25V X7R 0603 10%")
      (footprint "eagle-import:C0603")
      (libsource (lib "eagle-import") (part "C-EUC0603"))
    )
    (comp (ref "C112")
      (value "CAP CER 0.1UF 25V X7R 0603 10%")
      (footprint "eagle-import:C0603")
      (libsource (lib "eagle-import") (part "C-EUC0603"))
    )
    (comp (ref "IC30")
      (value "STM32F411RE")
      (footprint "eagle-import:TQFP64_STM32")
      (libsource (lib "eagle-import") (part "STM32F405RG"))
    )
    (comp (ref "L7")
      (value "PE-0603FB601ST")
      (footprint "eagle-import:R0603")
      (libsource (lib "eagle-import") (part "INDUCTOR0603"))
    )
    (comp (ref "LED1")
      (value "Dialight-5640200132F")
      (footprint "eagle-import:CBI-564-0X00-XXX")
      (libsource (lib "eagle-import") (part "CBI-564-0X00-XXX-3LED"))
    )
    (comp (ref "PROG")
      (value "JST_VERT")
      (footprint "eagle-import:JST-6-SMD-VERT-1.0MM")
      (libsource (lib "eagle-import") (part "JST_VERTICAL"))
    )
    (comp (ref "R55")
      (value "RES SMD 470 OHM 1% 1/10W 0603")
      (footprint "eagle-import:R0603")
      (libsource (lib "eagle-import") (part "resistor_R-EU_R0603"))
    )
    (comp (ref "R60")
      (value "RES SMD 470 OHM 1% 1/10W 0603")
      (footprint "eagle-import:R0603")
      (libsource (lib "eagle-import") (part "resistor_R-EU_R0603"))
    )
    (comp (ref "R65")
      (value "RES SMD 470 OHM 1% 1/10W 0603")
      (footprint "eagle-import:R0603")
      (libsource (lib "eagle-import") (part "resistor_R-EU_R0603"))
    )
    (comp (ref "R66")
      (value "DNP")
      (footprint "eagle-import:R0603")
      (libsource (lib "eagle-import") (part "rcl-modified-footprints_R-EU_R0603"))
    )
    (comp (ref "R69")
      (value "DNP")
      (footprint "eagle-import:R0603")
      (libsource (lib "eagle-import") (part "rcl-modified-footprints_R-EU_R0603"))
    )
    (comp (ref "R71")
      (value "RES SMD 0 OHM JUMPER 0603")
      (footprint "eagle-import:R0603")
      (libsource (lib "eagle-import") (part "rcl-modified-footprints_R-EU_R0603"))
    )
    (comp (ref "R72")
      (value "DNP")
      (footprint "eagle-import:R0603")
      (libsource (lib "eagle-import") (part "rcl-modified-footprints_R-EU_R0603"))
    )
    (comp (ref "R74")
      (value "RES SMD 0 OHM JUMPER 0603")
      (footprint "eagle-import:R0603")
      (libsource (lib "eagle-import") (part "rcl-modified-footprints_R-EU_R0603"))
    )
    (comp (ref "SW1")
      (value "MCU_RST")
      (footprint "eagle-import:E-SWITCH-TL3305AF160QG")
      (libsource (lib "eagle-import") (part "E-SWITCH-TL3305AF160QG"))
    )
    (comp (ref "XTAL1")
      (value "CSTCE8M00G15L99-R0")
      (footprint "eagle-import:CSTCE_G15L_CSTCE_GH5L")
      (libsource (lib "eagle-import") (part "MURATA_CSTCE_G15L/CSTCE_GH5L"))
    )
    (comp (ref "C55")
      (value "CAP CER 0.1UF 10V X7R 0402 10%")
      (footprint "eagle-import:C0402")
      (libsource (lib "eagle-import") (part "rcl-modified-footprints_C-EUC0402"))
    )
    (comp (ref "C62")
      (value "CAP CER 10000PF 10V X7R 0402 10%")
      (footprint "eagle-import:C0402")
      (libsource (lib "eagle-import") (part "rcl-modified-footprints_C-EUC0402"))
    )
    (comp (ref "C70")
      (value "CAP CER 100PF 50V C0G 0603 5%")
      (footprint "eagle-import:C0603")
      (libsource (lib "eagle-import") (part "rcl-modified-footprints_C-EUC0603"))
    )
    (comp (ref "C72")
      (value "DNP")
      (footprint "eagle-import:C0402")
      (libsource (lib "eagle-import") (part "rcl-modified-footprints_C-EUC0402"))
    )
    (comp (ref "C73")
      (value "CAP CER 0.1UF 10V X7R 0402 10%")
      (footprint "eagle-import:C0402")
      (libsource (lib "eagle-import") (part "C-EUC0402"))
    )
    (comp (ref "C74")
      (value "CAP CER 10000PF 10V X7R 0402 10%")
      (footprint "eagle-import:C0402")
      (libsource (lib "eagle-import") (part "C-EUC0402"))
    )
    (comp (ref "C77")
      (value "CAP CER 0.1UF 10V X7R 0402 10%")
      (footprint "eagle-import:C0402")
      (libsource (lib "eagle-import") (part "rcl-modified-footprints_C-EUC0402"))
    )
    (comp (ref "C78")
      (value "CAP CER 10000PF 10V X7R 0402 10%")
      (footprint "eagle-import:C0402")
      (libsource (lib "eagle-import") (part "rcl-modified-footprints_C-EUC0402"))
    )
    (comp (ref "C80")
      (value "CAP CER 0.1UF 10V X7R 0402 10%")
      (footprint "eagle-import:C0402")
      (libsource (lib "eagle-import") (part "rcl-modified-footprints_C-EUC0402"))
    )
    (comp (ref "C93")
      (value "CAP CER 0.1UF 10V X7R 0402 10%")
      (footprint "eagle-import:C0402")
      (libsource (lib "eagle-import") (part "rcl-modified-footprints_C-EUC0402"))
    )
    (comp (ref "IC14")
      (value "LTC1711")
      (footprint "eagle-import:MSOP8")
      (libsource (lib "eagle-import") (part "LTC1711"))
    )
    (comp (ref "IC15")
      (value "NC7SV74K8X")
      (footprint "eagle-import:US8_3.1MM_JDEC_MO-187")
      (libsource (lib "eagle-import") (part "NC7SV74K8X"))
    )
    (comp (ref "IC24")
      (value "TLV272DGK")
      (footprint "eagle-import:MSOP8")
      (libsource (lib "eagle-import") (part "TLV272DGK"))
    )
    (comp (ref "R40")
      (value "RES SMD 49.9 OHM 1% 1/10W 0603")
      (footprint "eagle-import:R0603")
      (libsource (lib "eagle-import") (part "rcl-modified-footprints_R-EU_R0603"))
    )
    (comp (ref "R47")
      (value "RES SMD 0 OHM JUMPER 0603")
      (footprint "eagle-import:R0603")
      (libsource (lib "eagle-import") (part "rcl-modified-footprints_R-EU_R0603"))
    )
    (comp (ref "R51")
      (value "RES SMD 0 OHM JUMPER 0603")
      (footprint "eagle-import:R0603")
      (libsource (lib "eagle-import") (part "rcl-modified-footprints_R-EU_R0603"))
    )
    (comp (ref "R53")
      (value "RES SMD 220K OHM 1% 1/10W 0603")
      (footprint "eagle-import:R0603")
      (libsource (lib "eagle-import") (part "rcl-modified-footprints_R-EU_R0603"))
    )
    (comp (ref "R54")
      (value "RES SMD 10K OHM 1% 1/10W 0603")
      (footprint "eagle-import:R0603")
      (libsource (lib "eagle-import") (part "rcl-modified-footprints_R-EU_R0603"))
    )
    (comp (ref "R56")
      (value "RES SMD 100K OHM 1% 1/10W 0603")
      (footprint "eagle-import:R0603")
      (libsource (lib "eagle-import") (part "rcl-modified-footprints_R-EU_R0603"))
    )
    (comp (ref "R57")
      (value "RES SMD 100K OHM 1% 1/10W 0603")
      (footprint "eagle-import:R0603")
      (libsource (lib "eagle-import") (part "rcl-modified-footprints_R-EU_R0603"))
    )
    (comp (ref "R61")
      (value "RES SMD 220K OHM 1% 1/10W 0603")
      (footprint "eagle-import:R0603")
      (libsource (lib "eagle-import") (part "rcl-modified-footprints_R-EU_R0603"))
    )
    (comp (ref "T1")
      (value "MMBTH10−4LT1G")
      (footprint "eagle-import:SOT23-BEC")
      (libsource (lib "eagle-import") (part "-NPN-SOT23-BECMMBTH10LT1"))
    )
    (comp (ref "TP12")
      (value "TPTP06R")
      (footprint "eagle-import:TP06R")
      (libsource (lib "eagle-import") (part "TPTP06R"))
    )
    (comp (ref "TP13")
      (value "TPTP06R")
      (footprint "eagle-import:TP06R")
      (libsource (lib "eagle-import") (part "TPTP06R"))
    )
    (comp (ref "C40")
      (value "CAP CER 10000PF 10V X7R 0402 10%")
      (footprint "eagle-import:C0402")
      (libsource (lib "eagle-import") (part "rcl-modified-footprints_C-EUC0402"))
    )
    (comp (ref "C47")
      (value "CAP CER 10000PF 10V X7R 0402 10%")
      (footprint "eagle-import:C0402")
      (libsource (lib "eagle-import") (part "rcl-modified-footprints_C-EUC0402"))
    )
    (comp (ref "C50")
      (value "CAP CER 10000PF 10V X7R 0402 10%")
      (footprint "eagle-import:C0402")
      (libsource (lib "eagle-import") (part "rcl-modified-footprints_C-EUC0402"))
    )
    (comp (ref "C51")
      (value "CAP CER 100PF 25V C0G/NP0 0402")
      (footprint "eagle-import:C0402")
      (libsource (lib "eagle-import") (part "rcl-modified-footprints_C-EUC0402"))
    )
    (comp (ref "C52")
      (value "CAP CER 10000PF 25V X7R 0603 10%")
      (footprint "eagle-import:C0603")
      (libsource (lib "eagle-import") (part "rcl-modified-footprints_C-EUC0603"))
    )
    (comp (ref "C75")
      (value "CAP CER 10000PF 25V X7R 0603 10%")
      (footprint "eagle-import:C0603")
      (libsource (lib "eagle-import") (part "rcl-modified-footprints_C-EUC0603"))
    )
    (comp (ref "C76")
      (value "CAP CER 0.1UF 25V X7R 0603 10%")
      (footprint "eagle-import:C0603")
      (libsource (lib "eagle-import") (part "rcl-modified-footprints_C-EUC0603"))
    )
    (comp (ref "C113")
      (value "CAP CER 0.1UF 25V X7R 0603 10%")
      (footprint "eagle-import:C0603")
      (libsource (lib "eagle-import") (part "C-EUC0603"))
    )
    (comp (ref "D3")
      (value "DF2B29FU,H3F")
      (footprint "eagle-import:SOD523")
      (libsource (lib "eagle-import") (part "diode_210_DIODE-SOD523"))
    )
    (comp (ref "D4")
      (value "BAS40")
      (footprint "eagle-import:SOT23")
      (libsource (lib "eagle-import") (part "BAS40"))
    )
    (comp (ref "D5")
      (value "BAS40")
      (footprint "eagle-import:SOT23")
      (libsource (lib "eagle-import") (part "BAS40"))
    )
    (comp (ref "IC6")
      (value "HFA3135")
      (footprint "eagle-import:SOT23-6L")
      (libsource (lib "eagle-import") (part "HFA3135"))
    )
    (comp (ref "IC8")
      (value "HFA3135")
      (footprint "eagle-import:SOT23-6L")
      (libsource (lib "eagle-import") (part "HFA3135"))
    )
    (comp (ref "IC11")
      (value "HFA3134")
      (footprint "eagle-import:SOT23-6L")
      (libsource (lib "eagle-import") (part "HFA3134"))
    )
    (comp (ref "IC12")
      (value "HFA3134")
      (footprint "eagle-import:SOT23-6L")
      (libsource (lib "eagle-import") (part "HFA3134"))
    )
    (comp (ref "IC13")
      (value "HFA3134")
      (footprint "eagle-import:SOT23-6L")
      (libsource (lib "eagle-import") (part "HFA3134"))
    )
    (comp (ref "M1")
      (value "BSS806N")
      (footprint "eagle-import:SOT23R_INFINEON")
      (libsource (lib "eagle-import") (part "BSS806N"))
    )
    (comp (ref "M2")
      (value "BSS806N")
      (footprint "eagle-import:SOT23R_INFINEON")
      (libsource (lib "eagle-import") (part "BSS806N"))
    )
    (comp (ref "R23")
      (value "RES SMD 220 OHM 1% 1/10W 0603")
      (footprint "eagle-import:R0603")
      (libsource (lib "eagle-import") (part "rcl-modified-footprints_R-EU_R0603"))
    )
    (comp (ref "R35")
      (value "RES SMD 49.9 OHM 1% 1/10W 0402")
      (footprint "eagle-import:R0402")
      (libsource (lib "eagle-import") (part "rcl-modified-footprints_R-EU_R0402"))
    )
    (comp (ref "R37")
      (value "RES SMD 100 OHM 1% 1/8W 0603")
      (footprint "eagle-import:R0603")
      (libsource (lib "eagle-import") (part "rcl-modified-footprints_R-EU_R0603"))
    )
    (comp (ref "R38")
      (value "RES SMD 200 OHM 1% 1/10W 0603")
      (footprint "eagle-import:R0603")
      (libsource (lib "eagle-import") (part "rcl-modified-footprints_R-EU_R0603"))
    )
    (comp (ref "R39")
      (value "RES SMD 200 OHM 1% 1/10W 0603")
      (footprint "eagle-import:R0603")
      (libsource (lib "eagle-import") (part "rcl-modified-footprints_R-EU_R0603"))
    )
    (comp (ref "R42")
      (value "RES SMD 100 OHM 1% 1/8W 0603")
      (footprint "eagle-import:R0603")
      (libsource (lib "eagle-import") (part "rcl-modified-footprints_R-EU_R0603"))
    )
    (comp (ref "R46")
      (value "RES SMD 220 OHM 1% 1/10W 0603")
      (footprint "eagle-import:R0603")
      (libsource (lib "eagle-import") (part "rcl-modified-footprints_R-EU_R0603"))
    )
    (comp (ref "R75")
      (value "RES SMD 100 OHM 1% 1/8W 0603")
      (footprint "eagle-import:R0603")
      (libsource (lib "eagle-import") (part "R-EU_R0603"))
    )
    (comp (ref "R76")
      (value "RES SMD 100 OHM 1% 1/8W 0603")
      (footprint "eagle-import:R0603")
      (libsource (lib "eagle-import") (part "R-EU_R0603"))
    )
    (comp (ref "RLY1")
      (value "CRF05-1A")
      (footprint "eagle-import:MEDER_RELAY_CRF")
      (libsource (lib "eagle-import") (part "MEDER_CRF05-1A"))
    )
    (comp (ref "RLY2")
      (value "CRF05-1A")
      (footprint "eagle-import:MEDER_RELAY_CRF")
      (libsource (lib "eagle-import") (part "MEDER_CRF05-1A"))
    )
    (comp (ref "TP9")
      (value "TP_VSCOPE")
      (footprint "eagle-import:JOHNSON-129-0701-30X")
      (libsource (lib "eagle-import") (part "TP-SCOPE_H"))
    )
    (comp (ref "X1")
      (value "CONN_PULLDN_SENSE")
      (footprint "eagle-import:J502-ND-142-0701-881_886")
      (fields
        (field (name "MF") "JOHNSON COMPONENTS")
        (field (name "MPN") "142-0701-881")
        (field (name "MF_1") "JOHNSON COMPONENTS")
        (field (name "MPN_1") "142-0711-871")
        (field (name "OC_FARNELL") "unknown")
        (field (name "OC_NEWARK") "01C1639")
      )
      (libsource (lib "eagle-import") (part "SMA-142-0701-881/886"))
    )
    (comp (ref "X4")
      (value "CONN_SPAD")
      (footprint "eagle-import:J502-ND-142-0701-881_886")
      (fields (field (name "MF") "JOHNSON COMPONENTS") (field (name "MPN") "142-0701-881"))
      (libsource (lib "eagle-import") (part "SMA-142-0701-881/886"))
    )
    (comp (ref "X7")
      (value "CONN_SMU")
      (footprint "eagle-import:J502-ND-142-0701-881_886")
      (fields (field (name "MF") "JOHNSON COMPONENTS") (field (name "MPN") "142-0701-881"))
      (libsource (lib "eagle-import") (part "SMA-142-0701-881/886"))
    )
    (comp (ref "C21")
      (value "CAP CER 10000PF 10V X7R 0402 10%")
      (footprint "eagle-import:C0402")
      (libsource (lib "eagle-import") (part "rcl-modified-footprints_C-EUC0402"))
    )
    (comp (ref "C23")
      (value "CAP CER 0.1UF 10V X7R 0402 10%")
      (footprint "eagle-import:C0402")
      (libsource (lib "eagle-import") (part "rcl-modified-footprints_C-EUC0402"))
    )
    (comp (ref "C24")
      (value "CAP CER 10000PF 10V X7R 0402 10%")
      (footprint "eagle-import:C0402")
      (libsource (lib "eagle-import") (part "rcl-modified-footprints_C-EUC0402"))
    )
    (comp (ref "C28")
      (value "CAP CER 10000PF 10V X7R 0402 10%")
      (footprint "eagle-import:C0402")
      (libsource (lib "eagle-import") (part "rcl-modified-footprints_C-EUC0402"))
    )
    (comp (ref "C33")
      (value "CAP CER 0.1UF 10V X7R 0402 10%")
      (footprint "eagle-import:C0402")
      (libsource (lib "eagle-import") (part "rcl-modified-footprints_C-EUC0402"))
    )
    (comp (ref "C34")
      (value "CAP CER 10000PF 10V X7R 0402 10%")
      (footprint "eagle-import:C0402")
      (libsource (lib "eagle-import") (part "rcl-modified-footprints_C-EUC0402"))
    )
    (comp (ref "C35")
      (value "CAP CER 0.1UF 10V X7R 0402 10%")
      (footprint "eagle-import:C0402")
      (libsource (lib "eagle-import") (part "rcl-modified-footprints_C-EUC0402"))
    )
    (comp (ref "C36")
      (value "CAP CER 0.1UF 10V X7R 0402 10%")
      (footprint "eagle-import:C0402")
      (libsource (lib "eagle-import") (part "rcl-modified-footprints_C-EUC0402"))
    )
    (comp (ref "C37")
      (value "CAP CER 0.1UF 10V X7R 0402 10%")
      (footprint "eagle-import:C0402")
      (libsource (lib "eagle-import") (part "rcl-modified-footprints_C-EUC0402"))
    )
    (comp (ref "C38")
      (value "CAP CER 10000PF 10V X7R 0402 10%")
      (footprint "eagle-import:C0402")
      (libsource (lib "eagle-import") (part "rcl-modified-footprints_C-EUC0402"))
    )
    (comp (ref "C43")
      (value "CAP CER 0.1UF 10V X7R 0402 10%")
      (footprint "eagle-import:C0402")
      (libsource (lib "eagle-import") (part "rcl-modified-footprints_C-EUC0402"))
    )
    (comp (ref "C44")
      (value "CAP CER 10000PF 10V X7R 0402 10%")
      (footprint "eagle-import:C0402")
      (libsource (lib "eagle-import") (part "rcl-modified-footprints_C-EUC0402"))
    )
    (comp (ref "C48")
      (value "CAP CER 10000PF 10V X7R 0402 10%")
      (footprint "eagle-import:C0402")
      (libsource (lib "eagle-import") (part "rcl-modified-footprints_C-EUC0402"))
    )
    (comp (ref "C49")
      (value "CAP CER 0.1UF 10V X7R 0402 10%")
      (footprint "eagle-import:C0402")
      (libsource (lib "eagle-import") (part "rcl-modified-footprints_C-EUC0402"))
    )
    (comp (ref "IC4")
      (value "ADCMP582")
      (footprint "eagle-import:QFN50P300X300X80-16N")
      (libsource (lib "eagle-import") (part "ADCMP582"))
    )
    (comp (ref "IC7")
      (value "DS1100LU-45+")
      (footprint "eagle-import:MSOP8")
      (libsource (lib "eagle-import") (part "DS1100L"))
    )
    (comp (ref "R20")
      (value "RES SMD 49.9 OHM 1% 1/10W 0402")
      (footprint "eagle-import:R0402")
      (libsource (lib "eagle-import") (part "rcl-modified-footprints_R-EU_R0402"))
    )
    (comp (ref "R21")
      (value "DNP")
      (footprint "eagle-import:R0603")
      (libsource (lib "eagle-import") (part "rcl-modified-footprints_R-EU_R0603"))
    )
    (comp (ref "R22")
      (value "RES SMD 150 OHM 1% 1/10W 0402")
      (footprint "eagle-import:R0402")
      (libsource (lib "eagle-import") (part "rcl-modified-footprints_R-EU_R0402"))
    )
    (comp (ref "R24")
      (value "DNP")
      (footprint "eagle-import:R0603")
      (libsource (lib "eagle-import") (part "rcl-modified-footprints_R-EU_R0603"))
    )
    (comp (ref "R25")
      (value "DNP")
      (footprint "eagle-import:R0603")
      (libsource (lib "eagle-import") (part "rcl-modified-footprints_R-EU_R0603"))
    )
    (comp (ref "R26")
      (value "DNP")
      (footprint "eagle-import:R0603")
      (libsource (lib "eagle-import") (part "rcl-modified-footprints_R-EU_R0603"))
    )
    (comp (ref "R27")
      (value "DNP")
      (footprint "eagle-import:R0603")
      (libsource (lib "eagle-import") (part "rcl-modified-footprints_R-EU_R0603"))
    )
    (comp (ref "R28")
      (value "DNP")
      (footprint "eagle-import:R0603")
      (libsource (lib "eagle-import") (part "rcl-modified-footprints_R-EU_R0603"))
    )
    (comp (ref "R31")
      (value "RES SMD 150 OHM 1% 1/10W 0402")
      (footprint "eagle-import:R0402")
      (libsource (lib "eagle-import") (part "rcl-modified-footprints_R-EU_R0402"))
    )
    (comp (ref "R33")
      (value "RES SMD 100 OHM 1% 1/10W 0402")
      (footprint "eagle-import:R0402")
      (libsource (lib "eagle-import") (part "rcl-modified-footprints_R-EU_R0402"))
    )
    (comp (ref "R36")
      (value "RES SMD 10K OHM 1% 1/10W 0603")
      (footprint "eagle-import:R0603")
      (libsource (lib "eagle-import") (part "rcl-modified-footprints_R-EU_R0603"))
    )
    (comp (ref "U2")
      (value "SN65EPT22DGK")
      (footprint "eagle-import:SOP65P490X110-8N")
      (libsource (lib "eagle-import") (part "SN65EPT22DGK"))
    )
    (comp (ref "U3")
      (value "SN65EPT21DGK")
      (footprint "eagle-import:SOP65P490X110-8N")
      (libsource (lib "eagle-import") (part "SN65EPT21DGK"))
    )
    (comp (ref "C29")
      (value "CAP CER 0.1UF 10V X7R 0402 10%")
      (footprint "eagle-import:C0402")
      (libsource (lib "eagle-import") (part "rcl-modified-footprints_C-EUC0402"))
    )
    (comp (ref "C30")
      (value "CAP CER 10000PF 10V X7R 0402 10%")
      (footprint "eagle-import:C0402")
      (libsource (lib "eagle-import") (part "rcl-modified-footprints_C-EUC0402"))
    )
    (comp (ref "C88")
      (value "CAP CER 0.1UF 25V X7R 0603 10%")
      (footprint "eagle-import:C0603")
      (libsource (lib "eagle-import") (part "rcl-modified-footprints_C-EUC0603"))
    )
    (comp (ref "C94")
      (value "CAP CER 0.1UF 25V X7R 0603 10%")
      (footprint "eagle-import:C0603")
      (libsource (lib "eagle-import") (part "rcl-modified-footprints_C-EUC0603"))
    )
    (comp (ref "C100")
      (value "CAP CER 0.1UF 25V X7R 0603 10%")
      (footprint "eagle-import:C0603")
      (libsource (lib "eagle-import") (part "C-EUC0603"))
    )
    (comp (ref "IC5")
      (value "HFA3134")
      (footprint "eagle-import:SOT23-6L")
      (libsource (lib "eagle-import") (part "HFA3134"))
    )
    (comp (ref "IC23")
      (value "HFA3134")
      (footprint "eagle-import:SOT23-6L")
      (libsource (lib "eagle-import") (part "HFA3134"))
    )
    (comp (ref "IC25")
      (value "THAT320")
      (footprint "eagle-import:SO14")
      (libsource (lib "eagle-import") (part "THAT320"))
    )
    (comp (ref "IC26")
      (value "TLV272DGK")
      (footprint "eagle-import:MSOP8")
      (libsource (lib "eagle-import") (part "TLV272DGK"))
    )
    (comp (ref "IC27")
      (value "HFA3134")
      (footprint "eagle-import:SOT23-6L")
      (libsource (lib "eagle-import") (part "HFA3134"))
    )
    (comp (ref "IC28")
      (value "TLV271DBV")
      (footprint "eagle-import:SOT23-5")
      (libsource (lib "eagle-import") (part "TLV271DBV"))
    )
    (comp (ref "R50")
      (value "RES SMD 110 OHM 1% 1/10W 0603")
      (footprint "eagle-import:R0603")
      (libsource (lib "eagle-import") (part "rcl-modified-footprints_R-EU_R0603"))
    )
    (comp (ref "R59")
      (value "RES SMD 127K OHM 1% 1/10W 0603")
      (footprint "eagle-import:R0603")
      (libsource (lib "eagle-import") (part "rcl-modified-footprints_R-EU_R0603"))
    )
    (comp (ref "R63")
      (value "RES SMD 274 OHM 1% 1/10W 0603")
      (footprint "eagle-import:R0603")
      (libsource (lib "eagle-import") (part "rcl-modified-footprints_R-EU_R0603"))
    )
    (comp (ref "R64")
      (value "RES SMD 102K OHM 1% 1/10W 0603")
      (footprint "eagle-import:R0603")
      (libsource (lib "eagle-import") (part "rcl-modified-footprints_R-EU_R0603"))
    )
    (comp (ref "R68")
      (value "SOT-DIV23LF-03-1001-1001-BB")
      (footprint "eagle-import:SOT23C")
      (libsource (lib "eagle-import") (part "DIVIDER_SOT23-5"))
    )
  )
  (nets
    (net (code "1") (name "BLANKING_LATCH_EN") (class "Default")
      (node (ref "R24") (pin "1") (pinfunction "1_1") (pintype "passive"))
      (node (ref "R25") (pin "1") (pinfunction "1_1") (pintype "passive"))
      (node (ref "R26") (pin "1") (pinfunction "1_1") (pintype "passive"))
      (node (ref "R27") (pin "1") (pinfunction "1_1") (pintype "passive"))
      (node (ref "R28") (pin "1") (pinfunction "1_1") (pintype "passive"))
      (node (ref "U2") (pin "7") (pinfunction "D0_7") (pintype "input"))
    )
    (net (code "2") (name "CAP_~{RESET}") (class "Default")
      (node (ref "IC17") (pin "1") (pinfunction "OE_1") (pintype "input"))
      (node (ref "IC22") (pin "4") (pinfunction "O_4") (pintype "output"))
    )
    (net (code "3") (name "CCS_STEERING_TAIL") (class "Default")
      (node (ref "IC13") (pin "2") (pinfunction "E_2") (pintype "passive"))
      (node (ref "IC13") (pin "5") (pinfunction "E_5") (pintype "passive"))
      (node (ref "IC23") (pin "6") (pinfunction "C_6") (pintype "passive"))
    )
    (net (code "4") (name "CCS_VA_SETPOINT") (class "Default")
      (node (ref "IC11") (pin "5") (pinfunction "E_5") (pintype "passive"))
      (node (ref "IC23") (pin "3") (pinfunction "C_3") (pintype "passive"))
    )
    (net (code "5") (name "COMP_LE_N") (class "Default")
      (node (ref "IC4") (pin "6") (pinfunction "~{LE}_6") (pintype "bidirectional"))
      (node (ref "U2") (pin "1") (pinfunction "Q0_1") (pintype "output"))
    )
    (net (code "6") (name "COMP_LE_P") (class "Default")
      (node (ref "IC4") (pin "7") (pinfunction "LE_7") (pintype "bidirectional"))
      (node (ref "U2") (pin "2") (pinfunction "~{Q0}_2") (pintype "output"))
    )
    (net (code "7") (name "COMP_Q_N") (class "Default")
      (node (ref "IC4") (pin "10") (pinfunction "~{Q}_10") (pintype "bidirectional"))
      (node (ref "R22") (pin "1") (pinfunction "1_1") (pintype "passive"))
      (node (ref "R33") (pin "1") (pinfunction "1_1") (pintype "passive"))
      (node (ref "U3") (pin "3") (pinfunction "~{D}_3") (pintype "input"))
    )
    (net (code "8") (name "COMP_Q_P") (class "Default")
      (node (ref "IC4") (pin "11") (pinfunction "Q_11") (pintype "bidirectional"))
      (node (ref "R31") (pin "1") (pinfunction "1_1") (pintype "passive"))
      (node (ref "R33") (pin "2") (pinfunction "2_2") (pintype "passive"))
      (node (ref "U3") (pin "2") (pinfunction "D_2") (pintype "input"))
    )
    (net (code "9") (name "DAC1_DIN") (class "Default")
      (node (ref "IC30") (pin "53") (pinfunction "PC12/SDIO_CLK_53") (pintype "bidirectional"))
      (node (ref "IC31") (pin "13") (pinfunction "DIN_13") (pintype "bidirectional"))
    )
    (net (code "10") (name "DAC1_DOUT") (class "Default")
      (node (ref "IC30") (pin "52") (pinfunction "PC11/SDIO_D3_52") (pintype "bidirectional"))
      (node (ref "IC31") (pin "12") (pinfunction "DOUT_12") (pintype "bidirectional"))
    )
    (net (code "11") (name "DAC1_SCLK") (class "Default")
      (node (ref "IC30") (pin "51") (pinfunction "PC10/SDIO_D2_51") (pintype "bidirectional"))
      (node (ref "IC31") (pin "14") (pinfunction "SCLK_14") (pintype "bidirectional"))
    )
    (net (code "12") (name "DAC1_~{CLR}") (class "Default")
      (node (ref "IC30") (pin "54") (pinfunction "PD2/SDIO_CMD_54") (pintype "bidirectional"))
      (node (ref "IC31") (pin "17") (pinfunction "~{CLR}_17") (pintype "bidirectional"))
    )
    (net (code "13") (name "DAC2_ADDRSEL") (class "Default")
      (node (ref "IC30") (pin "57") (pinfunction "PB5_57") (pintype "bidirectional"))
      (node (ref "U1") (pin "6") (pinfunction "A0_6") (pintype "input"))
    )
    (net (code "14") (name "DAC2_SCL") (class "Default")
      (node (ref "IC30") (pin "58") (pinfunction "PB6/I2C1_SCL_58") (pintype "bidirectional"))
      (node (ref "R12") (pin "2") (pinfunction "2_2") (pintype "passive"))
      (node (ref "U1") (pin "5") (pinfunction "SCL_5") (pintype "bidirectional"))
    )
    (net (code "15") (name "DAC2_SDA") (class "Default")
      (node (ref "IC30") (pin "59") (pinfunction "PB7/I2C1_SDA_59") (pintype "bidirectional"))
      (node (ref "R13") (pin "2") (pinfunction "2_2") (pintype "passive"))
      (node (ref "U1") (pin "4") (pinfunction "SDA_4") (pintype "bidirectional"))
    )
    (net (code "16") (name "DELTAV_BASE") (class "Default")
      (node (ref "IC23") (pin "1") (pinfunction "B_1") (pintype "passive"))
      (node (ref "IC26") (pin "1") (pinfunction "OUT_1") (pintype "output"))
    )
    (net (code "17") (name "DELTAV_FB") (class "Default")
      (node (ref "IC23") (pin "2") (pinfunction "E_2") (pintype "passive"))
      (node (ref "R59") (pin "1") (pinfunction "1_1") (pintype "passive"))
      (node (ref "R63") (pin "2") (pinfunction "2_2") (pintype "passive"))
    )
    (net (code "18") (name "DELTAV_VGND") (class "Default")
      (node (ref "IC26") (pin "2") (pinfunction "-IN_2") (pintype "input"))
      (node (ref "R59") (pin "2") (pinfunction "2_2") (pintype "passive"))
      (node (ref "R64") (pin "1") (pinfunction "1_1") (pintype "passive"))
    )
    (net (code "19") (name "DFLOP_~{CLR}") (class "Default")
      (node (ref "IC15") (pin "6") (pinfunction "~{CLR}_6") (pintype "bidirectional"))
      (node (ref "IC21") (pin "4") (pinfunction "O_4") (pintype "output"))
    )
    (net (code "20") (name "DIAMOND_BASE") (class "Default")
      (node (ref "IC27") (pin "1") (pinfunction "B_1") (pintype "passive"))
      (node (ref "IC27") (pin "4") (pinfunction "B_4") (pintype "passive"))
      (node (ref "IC28") (pin "1") (pinfunction "OUT_1") (pintype "output"))
    )
    (net (code "21") (name "DIAMOND_FB") (class "Default")
      (node (ref "IC27") (pin "2") (pinfunction "E_2") (pintype "passive"))
      (node (ref "IC28") (pin "4") (pinfunction "-IN_4") (pintype "input"))
      (node (ref "R68") (pin "2") (pinfunction "TOP_2") (pintype "bidirectional"))
    )
    (net (code "22") (name "DIAMOND_FB_R") (class "Default")
      (node (ref "IC27") (pin "5") (pinfunction "E_5") (pintype "passive"))
      (node (ref "R68") (pin "1") (pinfunction "BOTTOM_1") (pintype "bidirectional"))
    )
    (net (code "23") (name "DIAMOND_IBIAS_BOTTOM") (class "Default")
      (node (ref "C52") (pin "2") (pinfunction "2_2") (pintype "passive"))
      (node (ref "IC5") (pin "3") (pinfunction "C_3") (pintype "passive"))
      (node (ref "IC8") (pin "4") (pinfunction "B_4") (pintype "passive"))
      (node (ref "R38") (pin "1") (pinfunction "1_1") (pintype "passive"))
    )
    (net (code "24") (name "DIAMOND_IBIAS_MID") (class "Default")
      (node (ref "IC25") (pin "6") (pinfunction "B_6") (pintype "passive"))
      (node (ref "IC25") (pin "8") (pinfunction "C_8") (pintype "passive"))
      (node (ref "IC25") (pin "9") (pinfunction "B_9") (pintype "passive"))
      (node (ref "IC5") (pin "6") (pinfunction "C_6") (pintype "passive"))
    )
    (net (code "25") (name "DIAMOND_IBIAS_TOP") (class "Default")
      (node (ref "C52") (pin "1") (pinfunction "1_1") (pintype "passive"))
      (node (ref "IC12") (pin "4") (pinfunction "B_4") (pintype "passive"))
      (node (ref "IC25") (pin "7") (pinfunction "C_7") (pintype "passive"))
      (node (ref "R39") (pin "2") (pinfunction "2_2") (pintype "passive"))
    )
    (net (code "26") (name "DIAMOND_IN") (class "Default")
      (node (ref "IC11") (pin "3") (pinfunction "C_3") (pintype "passive"))
      (node (ref "IC11") (pin "6") (pinfunction "C_6") (pintype "passive"))
      (node (ref "IC12") (pin "1") (pinfunction "B_1") (pintype "passive"))
      (node (ref "IC8") (pin "1") (pinfunction "B_1") (pintype "passive"))
      (node (ref "R46") (pin "1") (pinfunction "1_1") (pintype "passive"))
    )
    (net (code "27") (name "DMD_IN_CASC") (class "Default")
      (node (ref "IC6") (pin "2") (pinfunction "E_2") (pintype "passive"))
      (node (ref "IC8") (pin "6") (pinfunction "C_6") (pintype "passive"))
    )
    (net (code "28") (name "DMD_IN_NPN_E") (class "Default")
      (node (ref "IC12") (pin "2") (pinfunction "E_2") (pintype "passive"))
      (node (ref "R38") (pin "2") (pinfunction "2_2") (pintype "passive"))
    )
    (net (code "29") (name "DMD_IN_PNP_E") (class "Default")
      (node (ref "IC8") (pin "2") (pinfunction "E_2") (pintype "passive"))
      (node (ref "R39") (pin "1") (pinfunction "1_1") (pintype "passive"))
    )
    (net (code "30") (name "DMD_OP_CASC") (class "Default")
      (node (ref "IC6") (pin "5") (pinfunction "E_5") (pintype "passive"))
      (node (ref "IC8") (pin "3") (pinfunction "C_3") (pintype "passive"))
    )
    (net (code "31") (name "DMD_OP_NPN") (class "Default")
      (node (ref "C51") (pin "1") (pinfunction "1_1") (pintype "passive"))
      (node (ref "IC12") (pin "5") (pinfunction "E_5") (pintype "passive"))
      (node (ref "R42") (pin "2") (pinfunction "2_2") (pintype "passive"))
    )
    (net (code "32") (name "DMD_OP_PNP") (class "Default")
      (node (ref "C51") (pin "2") (pinfunction "2_2") (pintype "passive"))
      (node (ref "IC8") (pin "5") (pinfunction "E_5") (pintype "passive"))
      (node (ref "R37") (pin "1") (pinfunction "1_1") (pintype "passive"))
    )
    (net (code "33") (name "DMD_OUT") (class "Default")
      (node (ref "R35") (pin "1") (pinfunction "1_1") (pintype "passive"))
      (node (ref "R37") (pin "2") (pinfunction "2_2") (pintype "passive"))
      (node (ref "R42") (pin "1") (pinfunction "1_1") (pintype "passive"))
      (node (ref "RLY1") (pin "10") (pinfunction "PIN10_10") (pintype "bidirectional"))
    )
    (net (code "34") (name "FORCE_QUENCH") (class "Default")
      (node (ref "IC18") (pin "2") (pinfunction "I_2") (pintype "input"))
      (node (ref "IC19") (pin "4") (pinfunction "O_4") (pintype "output"))
    )
    (net (code "35") (name "FORCE_QUENCH_USER") (class "Default")
      (node (ref "IC19") (pin "1") (pinfunction "I0_1") (pintype "input"))
      (node (ref "R49") (pin "2") (pinfunction "2_2") (pintype "passive"))
      (node (ref "X2") (pin "1") (pinfunction "1_1") (pintype "passive"))
    )
    (net (code "36") (name "GND") (class "Default")
      (node (ref "C1") (pin "2") (pinfunction "2_2") (pintype "passive"))
      (node (ref "C10") (pin "2") (pinfunction "2_2") (pintype "passive"))
      (node (ref "C100") (pin "2") (pinfunction "2_2") (pintype "passive"))
      (node (ref "C101") (pin "2") (pinfunction "2_2") (pintype "passive"))
      (node (ref "C102") (pin "2") (pinfunction "2_2") (pintype "passive"))
      (node (ref "C103") (pin "2") (pinfunction "2_2") (pintype "passive"))
      (node (ref "C104") (pin "2") (pinfunction "2_2") (pintype "passive"))
      (node (ref "C105") (pin "2") (pinfunction "2_2") (pintype "passive"))
      (node (ref "C106") (pin "2") (pinfunction "2_2") (pintype "passive"))
      (node (ref "C107") (pin "2") (pinfunction "2_2") (pintype "passive"))
      (node (ref "C108") (pin "2") (pinfunction "2_2") (pintype "passive"))
      (node (ref "C109") (pin "2") (pinfunction "2_2") (pintype "passive"))
      (node (ref "C11") (pin "2") (pinfunction "2_2") (pintype "passive"))
      (node (ref "C110") (pin "2") (pinfunction "2_2") (pintype "passive"))
      (node (ref "C111") (pin "2") (pinfunction "2_2") (pintype "passive"))
      (node (ref "C112") (pin "2") (pinfunction "2_2") (pintype "passive"))
      (node (ref "C113") (pin "2") (pinfunction "2_2") (pintype "passive"))
      (node (ref "C12") (pin "2") (pinfunction "2_2") (pintype "passive"))
      (node (ref "C13") (pin "-") (pinfunction "-_-") (pintype "passive"))
      (node (ref "C14") (pin "-") (pinfunction "-_-") (pintype "passive"))
      (node (ref "C15") (pin "2") (pinfunction "2_2") (pintype "passive"))
      (node (ref "C16") (pin "2") (pinfunction "2_2") (pintype "passive"))
      (node (ref "C17") (pin "2") (pinfunction "2_2") (pintype "passive"))
      (node (ref "C18") (pin "2") (pinfunction "2_2") (pintype "passive"))
      (node (ref "C19") (pin "2") (pinfunction "2_2") (pintype "passive"))
      (node (ref "C2") (pin "2") (pinfunction "2_2") (pintype "passive"))
      (node (ref "C20") (pin "2") (pinfunction "2_2") (pintype "passive"))
      (node (ref "C21") (pin "2") (pinfunction "2_2") (pintype "passive"))
      (node (ref "C22") (pin "2") (pinfunction "2_2") (pintype "passive"))
      (node (ref "C23") (pin "2") (pinfunction "2_2") (pintype "passive"))
      (node (ref "C24") (pin "2") (pinfunction "2_2") (pintype "passive"))
      (node (ref "C25") (pin "-") (pinfunction "-_-") (pintype "passive"))
      (node (ref "C26") (pin "-") (pinfunction "-_-") (pintype "passive"))
      (node (ref "C27") (pin "2") (pinfunction "2_2") (pintype "passive"))
      (node (ref "C28") (pin "2") (pinfunction "2_2") (pintype "passive"))
      (node (ref "C29") (pin "2") (pinfunction "2_2") (pintype "passive"))
      (node (ref "C3") (pin "1") (pinfunction "1_1") (pintype "passive"))
      (node (ref "C30") (pin "2") (pinfunction "2_2") (pintype "passive"))
      (node (ref "C31") (pin "2") (pinfunction "2_2") (pintype "passive"))
      (node (ref "C32") (pin "2") (pinfunction "2_2") (pintype "passive"))
      (node (ref "C33") (pin "2") (pinfunction "2_2") (pintype "passive"))
      (node (ref "C34") (pin "2") (pinfunction "2_2") (pintype "passive"))
      (node (ref "C35") (pin "2") (pinfunction "2_2") (pintype "passive"))
      (node (ref "C36") (pin "2") (pinfunction "2_2") (pintype "passive"))
      (node (ref "C37") (pin "2") (pinfunction "2_2") (pintype "passive"))
      (node (ref "C38") (pin "2") (pinfunction "2_2") (pintype "passive"))
      (node (ref "C39") (pin "2") (pinfunction "2_2") (pintype "passive"))
      (node (ref "C4") (pin "2") (pinfunction "2_2") (pintype "passive"))
      (node (ref "C40") (pin "2") (pinfunction "2_2") (pintype "passive"))
      (node (ref "C43") (pin "2") (pinfunction "2_2") (pintype "passive"))
      (node (ref "C44") (pin "2") (pinfunction "2_2") (pintype "passive"))
      (node (ref "C45") (pin "2") (pinfunction "2_2") (pintype "passive"))
      (node (ref "C46") (pin "2") (pinfunction "2_2") (pintype "passive"))
      (node (ref "C47") (pin "2") (pinfunction "2_2") (pintype "passive"))
      (node (ref "C48") (pin "2") (pinfunction "2_2") (pintype "passive"))
      (node (ref "C49") (pin "2") (pinfunction "2_2") (pintype "passive"))
      (node (ref "C50") (pin "2") (pinfunction "2_2") (pintype "passive"))
      (node (ref "C53") (pin "2") (pinfunction "2_2") (pintype "passive"))
      (node (ref "C54") (pin "2") (pinfunction "2_2") (pintype "passive"))
      (node (ref "C55") (pin "2") (pinfunction "2_2") (pintype "passive"))
      (node (ref "C56") (pin "2") (pinfunction "2_2") (pintype "passive"))
      (node (ref "C57") (pin "2") (pinfunction "2_2") (pintype "passive"))
      (node (ref "C58") (pin "2") (pinfunction "2_2") (pintype "passive"))
      (node (ref "C59") (pin "2") (pinfunction "2_2") (pintype "passive"))
      (node (ref "C60") (pin "2") (pinfunction "2_2") (pintype "passive"))
      (node (ref "C61") (pin "2") (pinfunction "2_2") (pintype "passive"))
      (node (ref "C62") (pin "2") (pinfunction "2_2") (pintype "passive"))
      (node (ref "C63") (pin "2") (pinfunction "2_2") (pintype "passive"))
      (node (ref "C64") (pin "2") (pinfunction "2_2") (pintype "passive"))
      (node (ref "C65") (pin "2") (pinfunction "2_2") (pintype "passive"))
      (node (ref "C66") (pin "2") (pinfunction "2_2") (pintype "passive"))
      (node (ref "C67") (pin "2") (pinfunction "2_2") (pintype "passive"))
      (node (ref "C68") (pin "2") (pinfunction "2_2") (pintype "passive"))
      (node (ref "C69") (pin "2") (pinfunction "2_2") (pintype "passive"))
      (node (ref "C7") (pin "2") (pinfunction "2_2") (pintype "passive"))
      (node (ref "C70") (pin "2") (pinfunction "2_2") (pintype "passive"))
      (node (ref "C71") (pin "2") (pinfunction "2_2") (pintype "passive"))
      (node (ref "C73") (pin "2") (pinfunction "2_2") (pintype "passive"))
      (node (ref "C74") (pin "2") (pinfunction "2_2") (pintype "passive"))
      (node (ref "C75") (pin "2") (pinfunction "2_2") (pintype "passive"))
      (node (ref "C76") (pin "2") (pinfunction "2_2") (pintype "passive"))
      (node (ref "C77") (pin "2") (pinfunction "2_2") (pintype "passive"))
      (node (ref "C78") (pin "2") (pinfunction "2_2") (pintype "passive"))
      (node (ref "C8") (pin "2") (pinfunction "2_2") (pintype "passive"))
      (node (ref "C80") (pin "2") (pinfunction "2_2") (pintype "passive"))
      (node (ref "C81") (pin "2") (pinfunction "2_2") (pintype "passive"))
      (node (ref "C82") (pin "2") (pinfunction "2_2") (pintype "passive"))
      (node (ref "C83") (pin "2") (pinfunction "2_2") (pintype "passive"))
      (node (ref "C84") (pin "2") (pinfunction "2_2") (pintype "passive"))
      (node (ref "C85") (pin "2") (pinfunction "2_2") (pintype "passive"))
      (node (ref "C86") (pin "2") (pinfunction "2_2") (pintype "passive"))
      (node (ref "C87") (pin "2") (pinfunction "2_2") (pintype "passive"))
      (node (ref "C88") (pin "2") (pinfunction "2_2") (pintype "passive"))
      (node (ref "C89") (pin "2") (pinfunction "2_2") (pintype "passive"))
      (node (ref "C9") (pin "2") (pinfunction "2_2") (pintype "passive"))
      (node (ref "C90") (pin "2") (pinfunction "2_2") (pintype "passive"))
      (node (ref "C91") (pin "2") (pinfunction "2_2") (pintype "passive"))
      (node (ref "C92") (pin "2") (pinfunction "2_2") (pintype "passive"))
      (node (ref "C93") (pin "2") (pinfunction "2_2") (pintype "passive"))
      (node (ref "C94") (pin "2") (pinfunction "2_2") (pintype "passive"))
      (node (ref "C95") (pin "2") (pinfunction "2_2") (pintype "passive"))
      (node (ref "C96") (pin "2") (pinfunction "2_2") (pintype "passive"))
      (node (ref "C97") (pin "2") (pinfunction "2_2") (pintype "passive"))
      (node (ref "C98") (pin "2") (pinfunction "2_2") (pintype "passive"))
      (node (ref "C99") (pin "2") (pinfunction "2_2") (pintype "passive"))
      (node (ref "D2") (pin "C") (pinfunction "C_C") (pintype "passive"))
      (node (ref "D3") (pin "A") (pinfunction "A_A") (pintype "passive"))
      (node (ref "H1") (pin "B3,2") (pinfunction "MOUNT_B3,2") (pintype "passive"))
      (node (ref "H2") (pin "B3,2") (pinfunction "MOUNT_B3,2") (pintype "passive"))
      (node (ref "H3") (pin "B3,2") (pinfunction "MOUNT_B3,2") (pintype "passive"))
      (node (ref "H4") (pin "B3,2") (pinfunction "MOUNT_B3,2") (pintype "passive"))
      (node (ref "IC1") (pin "4") (pinfunction "GND_4") (pintype "bidirectional"))
      (node (ref "IC1") (pin "PAD") (pinfunction "GND_PAD") (pintype "bidirectional"))
      (node (ref "IC10") (pin "1") (pinfunction "GND_1") (pintype "bidirectional"))
      (node (ref "IC10") (pin "16") (pinfunction "GND_16") (pintype "bidirectional"))
      (node (ref "IC10") (pin "8") (pinfunction "GND_8") (pintype "bidirectional"))
      (node (ref "IC10") (pin "9") (pinfunction "GND_9") (pintype "bidirectional"))
      (node (ref "IC14") (pin "5") (pinfunction "LEN_5") (pintype "bidirectional"))
      (node (ref "IC14") (pin "6") (pinfunction "GND_6") (pintype "bidirectional"))
      (node (ref "IC15") (pin "4") (pinfunction "GND_4") (pintype "bidirectional"))
      (node (ref "IC16") (pin "3") (pinfunction "GND_3") (pintype "power_in"))
      (node (ref "IC17") (pin "3") (pinfunction "GND_3") (pintype "power_in"))
      (node (ref "IC18") (pin "3") (pinfunction "GND_3") (pintype "power_in"))
      (node (ref "IC19") (pin "3") (pinfunction "GND_3") (pintype "power_in"))
      (node (ref "IC2") (pin "4") (pinfunction "GND_4") (pintype "bidirectional"))
      (node (ref "IC2") (pin "PAD") (pinfunction "GND_PAD") (pintype "bidirectional"))
      (node (ref "IC20") (pin "2") (pinfunction "GND_2") (pintype "bidirectional"))
      (node (ref "IC21") (pin "3") (pinfunction "GND_3") (pintype "power_in"))
      (node (ref "IC22") (pin "3") (pinfunction "GND_3") (pintype "power_in"))
      (node (ref "IC24") (pin "3") (pinfunction "+IN_3") (pintype "input"))
      (node (ref "IC25") (pin "11") (pinfunction "SUBC_11") (pintype "bidirectional"))
      (node (ref "IC25") (pin "4") (pinfunction "SUBC_4") (pintype "bidirectional"))
      (node (ref "IC26") (pin "3") (pinfunction "+IN_3") (pintype "input"))
      (node (ref "IC28") (pin "2") (pinfunction "V-_2") (pintype "power_in"))
      (node (ref "IC29") (pin "2") (pinfunction "GND_2") (pintype "bidirectional"))
      (node (ref "IC3") (pin "1") (pinfunction "GND_1") (pintype "bidirectional"))
      (node (ref "IC3") (pin "16") (pinfunction "GND_16") (pintype "bidirectional"))
      (node (ref "IC3") (pin "8") (pinfunction "GND_8") (pintype "bidirectional"))
      (node (ref "IC3") (pin "9") (pinfunction "GND_9") (pintype "bidirectional"))
      (node (ref "IC30") (pin "12") (pinfunction "VSSA_12") (pintype "bidirectional"))
      (node (ref "IC30") (pin "18") (pinfunction "VSS1_18") (pintype "bidirectional"))
      (node (ref "IC30") (pin "63") (pinfunction "VSS2_63") (pintype "bidirectional"))
      (node (ref "IC31") (pin "15") (pinfunction "CSB_15") (pintype "bidirectional"))
      (node (ref "IC31") (pin "19") (pinfunction "GND_19") (pintype "bidirectional"))
      (node (ref "IC31") (pin "20") (pinfunction "M/~{Z}_20") (pintype "bidirectional"))
      (node (ref "IC32") (pin "1") (pinfunction "GND_1") (pintype "bidirectional"))
      (node (ref "IC4") (pin "15") (pinfunction "GND_15") (pintype "bidirectional"))
      (node (ref "IC6") (pin "6") (pinfunction "C_6") (pintype "passive"))
      (node (ref "IC7") (pin "4") (pinfunction "GND_4") (pintype "bidirectional"))
      (node (ref "IC9") (pin "4") (pinfunction "GND_4") (pintype "bidirectional"))
      (node (ref "IC9") (pin "PAD") (pinfunction "GND_PAD") (pintype "bidirectional"))
      (node (ref "L1") (pin "2") (pinfunction "P$2_2") (pintype "bidirectional"))
      (node (ref "L10") (pin "2") (pinfunction "P$2_2") (pintype "bidirectional"))
      (node (ref "L5") (pin "2") (pinfunction "P$2_2") (pintype "bidirectional"))
      (node (ref "LED1") (pin "BOT_K") (pinfunction "BOT_K_BOT_K") (pintype "bidirectional"))
      (node (ref "LED1") (pin "MID_K") (pinfunction "MID_K_MID_K") (pintype "bidirectional"))
      (node (ref "LED1") (pin "TOP_K") (pinfunction "TOP_K_TOP_K") (pintype "bidirectional"))
      (node (ref "M1") (pin "2") (pinfunction "S_2") (pintype "passive"))
      (node (ref "M2") (pin "2") (pinfunction "S_2") (pintype "passive"))
      (node (ref "PROG") (pin "3") (pinfunction "3_3") (pintype "bidirectional"))
      (node (ref "R1") (pin "2") (pinfunction "2_2") (pintype "passive"))
      (node (ref "R14") (pin "2") (pinfunction "2_2") (pintype "passive"))
      (node (ref "R15") (pin "2") (pinfunction "2_2") (pintype "passive"))
      (node (ref "R19") (pin "1") (pinfunction "1_1") (pintype "passive"))
      (node (ref "R2") (pin "2") (pinfunction "2_2") (pintype "passive"))
      (node (ref "R20") (pin "2") (pinfunction "2_2") (pintype "passive"))
      (node (ref "R21") (pin "1") (pinfunction "1_1") (pintype "passive"))
      (node (ref "R22") (pin "2") (pinfunction "2_2") (pintype "passive"))
      (node (ref "R30") (pin "1") (pinfunction "1_1") (pintype "passive"))
      (node (ref "R31") (pin "2") (pinfunction "2_2") (pintype "passive"))
      (node (ref "R34") (pin "2") (pinfunction "2_2") (pintype "passive"))
      (node (ref "R43") (pin "2") (pinfunction "2_2") (pintype "passive"))
      (node (ref "R44") (pin "2") (pinfunction "2_2") (pintype "passive"))
      (node (ref "R48") (pin "2") (pinfunction "2_2") (pintype "passive"))
      (node (ref "R49") (pin "1") (pinfunction "1_1") (pintype "passive"))
      (node (ref "R50") (pin "1") (pinfunction "1_1") (pintype "passive"))
      (node (ref "R6") (pin "2") (pinfunction "2_2") (pintype "passive"))
      (node (ref "R68") (pin "3") (pinfunction "MIDDLE_3") (pintype "bidirectional"))
      (node (ref "R71") (pin "2") (pinfunction "2_2") (pintype "passive"))
      (node (ref "R72") (pin "2") (pinfunction "2_2") (pintype "passive"))
      (node (ref "R74") (pin "2") (pinfunction "2_2") (pintype "passive"))
      (node (ref "R8") (pin "1") (pinfunction "1_1") (pintype "passive"))
      (node (ref "RLY1") (pin "1") (pinfunction "PIN1_1") (pintype "bidirectional"))
      (node (ref "RLY1") (pin "4") (pinfunction "PIN4_4") (pintype "bidirectional"))
      (node (ref "RLY1") (pin "6") (pinfunction "PIN6_6") (pintype "bidirectional"))
      (node (ref "RLY1") (pin "9") (pinfunction "PIN9_9") (pintype "bidirectional"))
      (node (ref "RLY2") (pin "1") (pinfunction "PIN1_1") (pintype "bidirectional"))
      (node (ref "RLY2") (pin "4") (pinfunction "PIN4_4") (pintype "bidirectional"))
      (node (ref "RLY2") (pin "6") (pinfunction "PIN6_6") (pintype "bidirectional"))
      (node (ref "RLY2") (pin "9") (pinfunction "PIN9_9") (pintype "bidirectional"))
      (node (ref "SW1") (pin "1") (pinfunction "P$1_1") (pintype "bidirectional"))
      (node (ref "SW1") (pin "2") (pinfunction "P$1_2") (pintype "bidirectional"))
      (node (ref "TP22") (pin "P$1") (pinfunction "P$1_P$1") (pintype "bidirectional"))
      (node (ref "TP4") (pin "TP") (pinfunction "TP_TP") (pintype "input"))
      (node (ref "TP5") (pin "P$1") (pinfunction "P$1_P$1") (pintype "bidirectional"))
      (node (ref "TP9") (pin "GND1") (pinfunction "GND_GND1") (pintype "power_in"))
      (node (ref "TP9") (pin "GND2") (pinfunction "GND_GND2") (pintype "power_in"))
      (node (ref "U1") (pin "2") (pinfunction "GND_2") (pintype "power_in"))
      (node (ref "U2") (pin "5") (pinfunction "GND_5") (pintype "passive"))
      (node (ref "U2") (pin "6") (pinfunction "D1_6") (pintype "input"))
      (node (ref "U3") (pin "5") (pinfunction "GND_5") (pintype "passive"))
      (node (ref "X1") (pin "G@1") (pinfunction "GND_G@1") (pintype "power_in"))
      (node (ref "X2") (pin "G@1") (pinfunction "GND_G@1") (pintype "power_in"))
      (node (ref "X3") (pin "1") (pinfunction "1_1") (pintype "bidirectional"))
      (node (ref "X3") (pin "2") (pinfunction "1_2") (pintype "bidirectional"))
      (node (ref "X3") (pin "3") (pinfunction "1_3") (pintype "bidirectional"))
      (node (ref "X3") (pin "4") (pinfunction "1_4") (pintype "bidirectional"))
      (node (ref "X4") (pin "G@1") (pinfunction "GND_G@1") (pintype "power_in"))
      (node (ref "X5") (pin "G@1") (pinfunction "GND_G@1") (pintype "power_in"))
      (node (ref "X6") (pin "1") (pinfunction "1_1") (pintype "bidirectional"))
      (node (ref "X6") (pin "2") (pinfunction "1_2") (pintype "bidirectional"))
      (node (ref "X6") (pin "3") (pinfunction "1_3") (pintype "bidirectional"))
      (node (ref "X6") (pin "4") (pinfunction "1_4") (pintype "bidirectional"))
      (node (ref "X7") (pin "G@1") (pinfunction "GND_G@1") (pintype "power_in"))
      (node (ref "X8") (pin "S1") (pinfunction "S1_S1") (pintype "passive"))
      (node (ref "X8") (pin "S2") (pinfunction "S2_S2") (pintype "passive"))
      (node (ref "XTAL1") (pin "2") (pinfunction "GND_2") (pintype "bidirectional"))
    )
    (net (code "37") (name "HOLDOFF_TRIG") (class "Default")
      (node (ref "IC15") (pin "1") (pinfunction "CLK_1") (pintype "bidirectional"))
      (node (ref "U3") (pin "7") (pinfunction "Q_7") (pintype "output"))
    )
    (net (code "38") (name "LDO_N10V0_FB_CH1") (class "Default")
      (node (ref "C41") (pin "2") (pinfunction "2_2") (pintype "passive"))
      (node (ref "IC9") (pin "2") (pinfunction "FB_2") (pintype "bidirectional"))
      (node (ref "R32") (pin "1") (pinfunction "1_1") (pintype "passive"))
      (node (ref "R34") (pin "1") (pinfunction "1_1") (pintype "passive"))
    )
    (net (code "39") (name "LDO_N10V0_NR_SS_CH1") (class "Default")
      (node (ref "C54") (pin "1") (pinfunction "1_1") (pintype "passive"))
      (node (ref "IC9") (pin "6") (pinfunction "NR/SS_6") (pintype "bidirectional"))
    )
    (net (code "40") (name "LDO_P5V0_FB_CH1") (class "Default")
      (node (ref "C5") (pin "2") (pinfunction "2_2") (pintype "passive"))
      (node (ref "IC1") (pin "2") (pinfunction "FB_2") (pintype "bidirectional"))
      (node (ref "R1") (pin "1") (pinfunction "1_1") (pintype "passive"))
      (node (ref "R10") (pin "1") (pinfunction "1_1") (pintype "passive"))
    )
    (net (code "41") (name "LDO_P5V0_NR_SS_CH1") (class "Default")
      (node (ref "C1") (pin "1") (pinfunction "1_1") (pintype "passive"))
      (node (ref "IC1") (pin "6") (pinfunction "NR/SS_6") (pintype "bidirectional"))
    )
    (net (code "42") (name "LDO_P10V0_FB_CH1") (class "Default")
      (node (ref "C6") (pin "2") (pinfunction "2_2") (pintype "passive"))
      (node (ref "IC2") (pin "2") (pinfunction "FB_2") (pintype "bidirectional"))
      (node (ref "R11") (pin "1") (pinfunction "1_1") (pintype "passive"))
      (node (ref "R2") (pin "1") (pinfunction "1_1") (pintype "passive"))
    )
    (net (code "43") (name "LDO_P10V0_NR_SS_CH1") (class "Default")
      (node (ref "C2") (pin "1") (pinfunction "1_1") (pintype "passive"))
      (node (ref "IC2") (pin "6") (pinfunction "NR/SS_6") (pintype "bidirectional"))
    )
    (net (code "44") (name "LOGIC_QUENCH") (class "Default")
      (node (ref "IC13") (pin "4") (pinfunction "B_4") (pintype "passive"))
      (node (ref "IC15") (pin "5") (pinfunction "Q_5") (pintype "bidirectional"))
      (node (ref "TP13") (pin "TP") (pinfunction "TP_TP") (pintype "input"))
    )
    (net (code "45") (name "LOGIC_QUENCH_BUF") (class "Default")
      (node (ref "IC16") (pin "4") (pinfunction "O_4") (pintype "output"))
      (node (ref "IC20") (pin "1") (pinfunction "IN1_1") (pintype "bidirectional"))
      (node (ref "IC20") (pin "3") (pinfunction "IN2_3") (pintype "bidirectional"))
      (node (ref "IC22") (pin "2") (pinfunction "I1_2") (pintype "input"))
      (node (ref "IC7") (pin "1") (pinfunction "IN_1") (pintype "bidirectional"))
      (node (ref "R40") (pin "2") (pinfunction "2_2") (pintype "passive"))
    )
    (net (code "46") (name "MCU_AQC_RLY") (class "Default")
      (node (ref "IC30") (pin "34") (pinfunction "PB13/I2S2_CK_34") (pintype "bidirectional"))
      (node (ref "R76") (pin "2") (pinfunction "2_2") (pintype "passive"))
    )
    (net (code "47") (name "MCU_BOOT0") (class "Default")
      (node (ref "IC30") (pin "60") (pinfunction "BOOT0_60") (pintype "bidirectional"))
      (node (ref "R69") (pin "2") (pinfunction "2_2") (pintype "passive"))
      (node (ref "R71") (pin "1") (pinfunction "1_1") (pintype "passive"))
    )
    (net (code "48") (name "MCU_BOOT1") (class "Default")
      (node (ref "IC30") (pin "28") (pinfunction "PB2-BOOT1_28") (pintype "bidirectional"))
      (node (ref "R66") (pin "2") (pinfunction "2_2") (pintype "passive"))
      (node (ref "R72") (pin "1") (pinfunction "1_1") (pintype "passive"))
    )
    (net (code "49") (name "MCU_IVTEST_RLY") (class "Default")
      (node (ref "IC30") (pin "33") (pinfunction "PB12/I2S2_WS_33") (pintype "bidirectional"))
      (node (ref "R75") (pin "2") (pinfunction "2_2") (pintype "passive"))
    )
    (net (code "50") (name "MCU_JTCK") (class "Default")
      (node (ref "IC30") (pin "49") (pinfunction "PA14/JTCK_49") (pintype "bidirectional"))
      (node (ref "PROG") (pin "2") (pinfunction "2_2") (pintype "bidirectional"))
    )
    (net (code "51") (name "MCU_JTDO") (class "Default")
      (node (ref "IC30") (pin "55") (pinfunction "PB3/JTDO_55") (pintype "bidirectional"))
      (node (ref "PROG") (pin "6") (pinfunction "6_6") (pintype "bidirectional"))
    )
    (net (code "52") (name "MCU_JTMS") (class "Default")
      (node (ref "IC30") (pin "46") (pinfunction "PA13/JTMS_46") (pintype "bidirectional"))
      (node (ref "PROG") (pin "4") (pinfunction "4_4") (pintype "bidirectional"))
    )
    (net (code "53") (name "MCU_LED1") (class "Default")
      (node (ref "IC30") (pin "8") (pinfunction "PC0_8") (pintype "bidirectional"))
      (node (ref "R65") (pin "2") (pinfunction "2_2") (pintype "passive"))
    )
    (net (code "54") (name "MCU_LED2") (class "Default")
      (node (ref "IC30") (pin "9") (pinfunction "PC1_9") (pintype "bidirectional"))
      (node (ref "R60") (pin "2") (pinfunction "2_2") (pintype "passive"))
    )
    (net (code "55") (name "MCU_LED3") (class "Default")
      (node (ref "IC30") (pin "10") (pinfunction "PC2_10") (pintype "bidirectional"))
      (node (ref "R55") (pin "2") (pinfunction "2_2") (pintype "passive"))
    )
    (net (code "56") (name "MCU_NRST") (class "Default")
      (node (ref "C82") (pin "1") (pinfunction "1_1") (pintype "passive"))
      (node (ref "IC30") (pin "7") (pinfunction "NRST_7") (pintype "bidirectional"))
      (node (ref "PROG") (pin "5") (pinfunction "5_5") (pintype "bidirectional"))
      (node (ref "SW1") (pin "3") (pinfunction "P$2_3") (pintype "bidirectional"))
      (node (ref "SW1") (pin "4") (pinfunction "P$2_4") (pintype "bidirectional"))
    )
    (net (code "57") (name "MCU_OSC_IN") (class "Default")
      (node (ref "IC30") (pin "5") (pinfunction "PH0/OSC_IN_5") (pintype "bidirectional"))
      (node (ref "XTAL1") (pin "1") (pinfunction "LEFT_1") (pintype "bidirectional"))
    )
    (net (code "58") (name "MCU_OSC_OUT") (class "Default")
      (node (ref "IC30") (pin "6") (pinfunction "PH1/OSC_OUT_6") (pintype "bidirectional"))
      (node (ref "XTAL1") (pin "3") (pinfunction "RIGHT_3") (pintype "bidirectional"))
    )
    (net (code "59") (name "MCU_PB11") (class "Default")
      (node (ref "C104") (pin "1") (pinfunction "1_1") (pintype "passive"))
      (node (ref "IC30") (pin "30") (pinfunction "PB11_30") (pintype "bidirectional"))
    )
    (net (code "60") (name "MCU_TIM2_CH1_IN") (class "Default")
      (node (ref "IC30") (pin "14") (pinfunction "PA0_14") (pintype "bidirectional"))
      (node (ref "R40") (pin "1") (pinfunction "1_1") (pintype "passive"))
    )
    (net (code "61") (name "MCU_TIM2_CH1_OUT_1") (class "Default")
      (node (ref "IC21") (pin "1") (pinfunction "I0_1") (pintype "input"))
      (node (ref "IC30") (pin "21") (pinfunction "PA5/SPI1_SCK_21") (pintype "bidirectional"))
    )
    (net (code "62") (name "MCU_TIM2_CH1_OUT_2") (class "Default")
      (node (ref "IC19") (pin "2") (pinfunction "I1_2") (pintype "input"))
      (node (ref "IC30") (pin "50") (pinfunction "PA15/JTDI_50") (pintype "bidirectional"))
    )
    (net (code "63") (name "MCU_USB_FS_D_N") (class "Default")
      (node (ref "C101") (pin "1") (pinfunction "1_1") (pintype "passive"))
      (node (ref "IC30") (pin "44") (pinfunction "PA11_44") (pintype "bidirectional"))
      (node (ref "R70") (pin "1") (pinfunction "1_1") (pintype "passive"))
    )
    (net (code "64") (name "MCU_USB_FS_D_P") (class "Default")
      (node (ref "C98") (pin "1") (pinfunction "1_1") (pintype "passive"))
      (node (ref "IC30") (pin "45") (pinfunction "PA12_45") (pintype "bidirectional"))
      (node (ref "R67") (pin "1") (pinfunction "1_1") (pintype "passive"))
    )
    (net (code "65") (name "MCU_VCAP_1") (class "Default")
      (node (ref "IC30") (pin "31") (pinfunction "VCAP_1_31") (pintype "bidirectional"))
      (node (ref "R74") (pin "1") (pinfunction "1_1") (pintype "passive"))
    )
    (net (code "66") (name "MCU_VCAP_2") (class "Default")
      (node (ref "C112") (pin "1") (pinfunction "1_1") (pintype "passive"))
      (node (ref "IC30") (pin "47") (pinfunction "VCAP_2_47") (pintype "bidirectional"))
    )
    (net (code "67") (name "NC_DAC1_IRQ") (class "Default")
      (node (ref "IC31") (pin "16") (pinfunction "~{IRQ}_16") (pintype "bidirectional"))
    )
    (net (code "68") (name "NC_ONE_SHOT_CLR") (class "Default")
      (node (ref "IC14") (pin "8") (pinfunction "~{Q}_8") (pintype "bidirectional"))
    )
    (net (code "69") (name "Net-(C3-Pad2)") (class "Default")
      (node (ref "C3") (pin "2") (pinfunction "2_2") (pintype "passive"))
      (node (ref "R7") (pin "2") (pinfunction "2_2") (pintype "passive"))
    )
    (net (code "70") (name "Net-(C13-Pad+)") (class "Default")
      (node (ref "C13") (pin "+") (pinfunction "+_+") (pintype "passive"))
      (node (ref "C14") (pin "+") (pinfunction "+_+") (pintype "passive"))
      (node (ref "D1") (pin "C") (pinfunction "C_C") (pintype "passive"))
      (node (ref "L3") (pin "1") (pinfunction "1_1") (pintype "bidirectional"))
      (node (ref "R4") (pin "1") (pinfunction "1_1") (pintype "passive"))
      (node (ref "R9") (pin "1") (pinfunction "1_1") (pintype "passive"))
    )
    (net (code "71") (name "Net-(C18-Pad1)") (class "Default")
      (node (ref "C18") (pin "1") (pinfunction "1_1") (pintype "passive"))
      (node (ref "R16") (pin "1") (pinfunction "1_1") (pintype "passive"))
    )
    (net (code "72") (name "Net-(C31-Pad1)") (class "Default")
      (node (ref "C31") (pin "1") (pinfunction "1_1") (pintype "passive"))
      (node (ref "R29") (pin "2") (pinfunction "2_2") (pintype "passive"))
    )
    (net (code "73") (name "Net-(C42-Pad-)") (class "Default")
      (node (ref "C42") (pin "-") (pinfunction "-_-") (pintype "passive"))
      (node (ref "C71") (pin "1") (pinfunction "1_1") (pintype "passive"))
      (node (ref "D2") (pin "A") (pinfunction "A_A") (pintype "passive"))
      (node (ref "L6") (pin "4") (pinfunction "4_4") (pintype "bidirectional"))
    )
    (net (code "74") (name "Net-(C68-Pad1)") (class "Default")
      (node (ref "C68") (pin "1") (pinfunction "1_1") (pintype "passive"))
      (node (ref "R45") (pin "1") (pinfunction "1_1") (pintype "passive"))
    )
    (net (code "75") (name "Net-(D4-A)") (class "Default")
      (node (ref "D4") (pin "1") (pinfunction "A_1") (pintype "passive"))
      (node (ref "M1") (pin "3") (pinfunction "D_3") (pintype "passive"))
      (node (ref "RLY2") (pin "2") (pinfunction "PIN2_2") (pintype "bidirectional"))
    )
    (net (code "76") (name "Net-(D5-A)") (class "Default")
      (node (ref "D5") (pin "1") (pinfunction "A_1") (pintype "passive"))
      (node (ref "M2") (pin "3") (pinfunction "D_3") (pintype "passive"))
      (node (ref "RLY1") (pin "2") (pinfunction "PIN2_2") (pintype "bidirectional"))
    )
    (net (code "77") (name "Net-(IC3-COL)") (class "Default")
      (node (ref "D1") (pin "A") (pinfunction "A_A") (pintype "passive"))
      (node (ref "IC3") (pin "2") (pinfunction "COL_2") (pintype "bidirectional"))
      (node (ref "L2") (pin "2") (pinfunction "P$2_2") (pintype "bidirectional"))
      (node (ref "R7") (pin "1") (pinfunction "1_1") (pintype "passive"))
    )
    (net (code "78") (name "Net-(IC3-CT)") (class "Default")
      (node (ref "C4") (pin "1") (pinfunction "1_1") (pintype "passive"))
      (node (ref "IC3") (pin "5") (pinfunction "CT_5") (pintype "bidirectional"))
    )
    (net (code "79") (name "Net-(IC3-FB)") (class "Default")
      (node (ref "IC3") (pin "7") (pinfunction "FB_7") (pintype "bidirectional"))
      (node (ref "R5") (pin "1") (pinfunction "1_1") (pintype "passive"))
      (node (ref "R6") (pin "1") (pinfunction "1_1") (pintype "passive"))
    )
    (net (code "80") (name "Net-(IC3-PGND)") (class "Default")
      (node (ref "IC3") (pin "3") (pinfunction "PGND_3") (pintype "bidirectional"))
      (node (ref "L1") (pin "1") (pinfunction "P$1_1") (pintype "bidirectional"))
    )
    (net (code "81") (name "Net-(IC3-RCSL)") (class "Default")
      (node (ref "IC3") (pin "13") (pinfunction "RCSL_13") (pintype "bidirectional"))
      (node (ref "R15") (pin "1") (pinfunction "1_1") (pintype "passive"))
    )
    (net (code "82") (name "Net-(IC3-RT)") (class "Default")
      (node (ref "IC3") (pin "6") (pinfunction "RT_6") (pintype "bidirectional"))
      (node (ref "R8") (pin "2") (pinfunction "2_2") (pintype "passive"))
    )
    (net (code "83") (name "Net-(IC3-RVSL)") (class "Default")
      (node (ref "IC3") (pin "14") (pinfunction "RVSL_14") (pintype "bidirectional"))
      (node (ref "R14") (pin "1") (pinfunction "1_1") (pintype "passive"))
    )
    (net (code "84") (name "Net-(IC3-VC)") (class "Default")
      (node (ref "C19") (pin "1") (pinfunction "1_1") (pintype "passive"))
      (node (ref "IC3") (pin "11") (pinfunction "VC_11") (pintype "bidirectional"))
      (node (ref "R16") (pin "2") (pinfunction "2_2") (pintype "passive"))
    )
    (net (code "85") (name "Net-(IC4-HYS)") (class "Default")
      (node (ref "IC4") (pin "14") (pinfunction "HYS_14") (pintype "bidirectional"))
      (node (ref "R36") (pin "2") (pinfunction "2_2") (pintype "passive"))
    )
    (net (code "86") (name "Net-(IC4-VTN)") (class "Default")
      (node (ref "IC4") (pin "4") (pinfunction "VTN_4") (pintype "bidirectional"))
      (node (ref "R21") (pin "2") (pinfunction "2_2") (pintype "passive"))
    )
    (net (code "87") (name "Net-(IC4-VTT)") (class "Default")
      (node (ref "IC4") (pin "8") (pinfunction "VTT_8") (pintype "bidirectional"))
      (node (ref "R20") (pin "1") (pinfunction "1_1") (pintype "passive"))
    )
    (net (code "88") (name "Net-(IC7-TAP1)") (class "Default")
      (node (ref "IC7") (pin "7") (pinfunction "TAP1_7") (pintype "bidirectional"))
      (node (ref "R28") (pin "2") (pinfunction "2_2") (pintype "passive"))
    )
    (net (code "89") (name "Net-(IC7-TAP2)") (class "Default")
      (node (ref "IC7") (pin "2") (pinfunction "TAP2_2") (pintype "bidirectional"))
      (node (ref "R24") (pin "2") (pinfunction "2_2") (pintype "passive"))
    )
    (net (code "90") (name "Net-(IC7-TAP3)") (class "Default")
      (node (ref "IC7") (pin "6") (pinfunction "TAP3_6") (pintype "bidirectional"))
      (node (ref "R26") (pin "2") (pinfunction "2_2") (pintype "passive"))
    )
    (net (code "91") (name "Net-(IC7-TAP4)") (class "Default")
      (node (ref "IC7") (pin "3") (pinfunction "TAP4_3") (pintype "bidirectional"))
      (node (ref "R25") (pin "2") (pinfunction "2_2") (pintype "passive"))
    )
    (net (code "92") (name "Net-(IC7-TAP5)") (class "Default")
      (node (ref "IC7") (pin "5") (pinfunction "TAP5_5") (pintype "bidirectional"))
      (node (ref "R27") (pin "2") (pinfunction "2_2") (pintype "passive"))
    )
    (net (code "93") (name "Net-(IC10-COL)") (class "Default")
      (node (ref "C42") (pin "+") (pinfunction "+_+") (pintype "passive"))
      (node (ref "IC10") (pin "2") (pinfunction "COL_2") (pintype "bidirectional"))
      (node (ref "L6") (pin "3") (pinfunction "3_3") (pintype "bidirectional"))
      (node (ref "R29") (pin "1") (pinfunction "1_1") (pintype "passive"))
    )
    (net (code "94") (name "Net-(IC10-CT)") (class "Default")
      (node (ref "C32") (pin "1") (pinfunction "1_1") (pintype "passive"))
      (node (ref "IC10") (pin "5") (pinfunction "CT_5") (pintype "bidirectional"))
    )
    (net (code "95") (name "Net-(IC10-NFB)") (class "Default")
      (node (ref "IC10") (pin "10") (pinfunction "NFB_10") (pintype "bidirectional"))
      (node (ref "R41") (pin "2") (pinfunction "2_2") (pintype "passive"))
      (node (ref "R48") (pin "1") (pinfunction "1_1") (pintype "passive"))
    )
    (net (code "96") (name "Net-(IC10-PGND)") (class "Default")
      (node (ref "IC10") (pin "3") (pinfunction "PGND_3") (pintype "bidirectional"))
      (node (ref "L5") (pin "1") (pinfunction "P$1_1") (pintype "bidirectional"))
    )
    (net (code "97") (name "Net-(IC10-RCSL)") (class "Default")
      (node (ref "IC10") (pin "13") (pinfunction "RCSL_13") (pintype "bidirectional"))
      (node (ref "R44") (pin "1") (pinfunction "1_1") (pintype "passive"))
    )
    (net (code "98") (name "Net-(IC10-RT)") (class "Default")
      (node (ref "IC10") (pin "6") (pinfunction "RT_6") (pintype "bidirectional"))
      (node (ref "R30") (pin "2") (pinfunction "2_2") (pintype "passive"))
    )
    (net (code "99") (name "Net-(IC10-RVSL)") (class "Default")
      (node (ref "IC10") (pin "14") (pinfunction "RVSL_14") (pintype "bidirectional"))
      (node (ref "R43") (pin "1") (pinfunction "1_1") (pintype "passive"))
    )
    (net (code "100") (name "Net-(IC10-VC)") (class "Default")
      (node (ref "C69") (pin "1") (pinfunction "1_1") (pintype "passive"))
      (node (ref "IC10") (pin "11") (pinfunction "VC_11") (pintype "bidirectional"))
      (node (ref "R45") (pin "2") (pinfunction "2_2") (pintype "passive"))
    )
    (net (code "101") (name "Net-(IC14-+IN)") (class "Default")
      (node (ref "C72") (pin "1") (pinfunction "1_1") (pintype "passive"))
      (node (ref "IC14") (pin "2") (pinfunction "+IN_2") (pintype "bidirectional"))
      (node (ref "R47") (pin "1") (pinfunction "1_1") (pintype "passive"))
    )
    (net (code "102") (name "Net-(IC14--IN)") (class "Default")
      (node (ref "C72") (pin "2") (pinfunction "2_2") (pintype "passive"))
      (node (ref "IC14") (pin "3") (pinfunction "-IN_3") (pintype "bidirectional"))
      (node (ref "R51") (pin "1") (pinfunction "1_1") (pintype "passive"))
    )
    (net (code "103") (name "Net-(IC20-OUT1)") (class "Default")
      (node (ref "IC20") (pin "4") (pinfunction "OUT2_4") (pintype "bidirectional"))
      (node (ref "IC20") (pin "6") (pinfunction "OUT1_6") (pintype "bidirectional"))
      (node (ref "R52") (pin "2") (pinfunction "2_2") (pintype "passive"))
    )
    (net (code "104") (name "Net-(IC24A-OUT)") (class "Default")
      (node (ref "IC24") (pin "1") (pinfunction "OUT_1") (pintype "output"))
      (node (ref "T1") (pin "B") (pinfunction "B_B") (pintype "passive"))
    )
    (net (code "105") (name "Net-(IC24B--IN)") (class "Default")
      (node (ref "IC24") (pin "6") (pinfunction "-IN_6") (pintype "input"))
      (node (ref "R56") (pin "1") (pinfunction "1_1") (pintype "passive"))
      (node (ref "R57") (pin "2") (pinfunction "2_2") (pintype "passive"))
    )
    (net (code "106") (name "Net-(IC24B-OUT)") (class "Default")
      (node (ref "IC24") (pin "7") (pinfunction "OUT_7") (pintype "output"))
      (node (ref "R51") (pin "2") (pinfunction "2_2") (pintype "passive"))
      (node (ref "R57") (pin "1") (pinfunction "1_1") (pintype "passive"))
    )
    (net (code "107") (name "Net-(IC25A-B)") (class "Default")
      (node (ref "IC25") (pin "1") (pinfunction "C_1") (pintype "passive"))
      (node (ref "IC25") (pin "10") (pinfunction "E_10") (pintype "passive"))
      (node (ref "IC25") (pin "13") (pinfunction "B_13") (pintype "passive"))
      (node (ref "IC25") (pin "2") (pinfunction "B_2") (pintype "passive"))
    )
    (net (code "108") (name "Net-(IC25B-C)") (class "Default")
      (node (ref "IC25") (pin "14") (pinfunction "C_14") (pintype "passive"))
      (node (ref "IC25") (pin "5") (pinfunction "E_5") (pintype "passive"))
    )
    (net (code "109") (name "Net-(IC27A-C)") (class "Default")
      (node (ref "IC27") (pin "6") (pinfunction "C_6") (pintype "passive"))
      (node (ref "IC5") (pin "2") (pinfunction "E_2") (pintype "passive"))
    )
    (net (code "110") (name "Net-(IC27B-C)") (class "Default")
      (node (ref "IC27") (pin "3") (pinfunction "C_3") (pintype "passive"))
      (node (ref "IC5") (pin "5") (pinfunction "E_5") (pintype "passive"))
    )
    (net (code "111") (name "Net-(IC31-REF)") (class "Default")
      (node (ref "IC31") (pin "1") (pinfunction "REF_1") (pintype "bidirectional"))
      (node (ref "R73") (pin "2") (pinfunction "2_2") (pintype "passive"))
    )
    (net (code "112") (name "Net-(L3-Pad2)") (class "Default")
      (node (ref "L3") (pin "2") (pinfunction "2_2") (pintype "bidirectional"))
      (node (ref "L3") (pin "3") (pinfunction "3_3") (pintype "bidirectional"))
    )
    (net (code "113") (name "Net-(LED1-PadBOT_A)") (class "Default")
      (node (ref "LED1") (pin "BOT_A") (pinfunction "BOT_A_BOT_A") (pintype "bidirectional"))
      (node (ref "R55") (pin "1") (pinfunction "1_1") (pintype "passive"))
    )
    (net (code "114") (name "Net-(LED1-PadMID_A)") (class "Default")
      (node (ref "LED1") (pin "MID_A") (pinfunction "MID_A_MID_A") (pintype "bidirectional"))
      (node (ref "R60") (pin "1") (pinfunction "1_1") (pintype "passive"))
    )
    (net (code "115") (name "Net-(LED1-PadTOP_A)") (class "Default")
      (node (ref "LED1") (pin "TOP_A") (pinfunction "TOP_A_TOP_A") (pintype "bidirectional"))
      (node (ref "R65") (pin "1") (pinfunction "1_1") (pintype "passive"))
    )
    (net (code "116") (name "Net-(M1-G)") (class "Default")
      (node (ref "M1") (pin "1") (pinfunction "G_1") (pintype "passive"))
      (node (ref "R75") (pin "1") (pinfunction "1_1") (pintype "passive"))
    )
    (net (code "117") (name "Net-(M2-G)") (class "Default")
      (node (ref "M2") (pin "1") (pinfunction "G_1") (pintype "passive"))
      (node (ref "R76") (pin "1") (pinfunction "1_1") (pintype "passive"))
    )
    (net (code "118") (name "Net-(Q1-G)") (class "Default")
      (node (ref "C79") (pin "1") (pinfunction "1_1") (pintype "passive"))
      (node (ref "Q1") (pin "1") (pinfunction "G_1") (pintype "passive"))
      (node (ref "R58") (pin "1") (pinfunction "1_1") (pintype "passive"))
      (node (ref "R62") (pin "1") (pinfunction "1_1") (pintype "passive"))
    )
    (net (code "119") (name "Net-(R3-Pad2)") (class "Default")
      (node (ref "R3") (pin "2") (pinfunction "2_2") (pintype "passive"))
      (node (ref "R4") (pin "2") (pinfunction "2_2") (pintype "passive"))
      (node (ref "R5") (pin "2") (pinfunction "2_2") (pintype "passive"))
    )
    (net (code "120") (name "Net-(R52-Pad1)") (class "Default")
      (node (ref "R52") (pin "1") (pinfunction "1_1") (pintype "passive"))
      (node (ref "X5") (pin "1") (pinfunction "1_1") (pintype "passive"))
    )
    (net (code "121") (name "Net-(U1-VOUT)") (class "Default")
      (node (ref "R18") (pin "2") (pinfunction "2_2") (pintype "passive"))
      (node (ref "U1") (pin "1") (pinfunction "VOUT_1") (pintype "output"))
    )
    (net (code "122") (name "ONE_SHOT_CAP") (class "Default")
      (node (ref "C70") (pin "1") (pinfunction "1_1") (pintype "passive"))
      (node (ref "IC17") (pin "4") (pinfunction "O_4") (pintype "tri_state"))
      (node (ref "R47") (pin "2") (pinfunction "2_2") (pintype "passive"))
      (node (ref "T1") (pin "C") (pinfunction "C_C") (pintype "passive"))
    )
    (net (code "123") (name "ONE_SHOT_FB") (class "Default")
      (node (ref "R53") (pin "1") (pinfunction "1_1") (pintype "passive"))
      (node (ref "R54") (pin "1") (pinfunction "1_1") (pintype "passive"))
      (node (ref "T1") (pin "E") (pinfunction "E_E") (pintype "passive"))
    )
    (net (code "124") (name "ONE_SHOT_VGND") (class "Default")
      (node (ref "IC24") (pin "2") (pinfunction "-IN_2") (pintype "input"))
      (node (ref "R53") (pin "2") (pinfunction "2_2") (pintype "passive"))
      (node (ref "R61") (pin "1") (pinfunction "1_1") (pintype "passive"))
    )
    (net (code "125") (name "PP_N5V0_ANALOG") (class "Default")
      (node (ref "C37") (pin "1") (pinfunction "1_1") (pintype "passive"))
      (node (ref "C38") (pin "1") (pinfunction "1_1") (pintype "passive"))
      (node (ref "C39") (pin "1") (pinfunction "1_1") (pintype "passive"))
      (node (ref "C41") (pin "1") (pinfunction "1_1") (pintype "passive"))
      (node (ref "C46") (pin "1") (pinfunction "1_1") (pintype "passive"))
      (node (ref "C55") (pin "1") (pinfunction "1_1") (pintype "passive"))
      (node (ref "C62") (pin "1") (pinfunction "1_1") (pintype "passive"))
      (node (ref "C80") (pin "1") (pinfunction "1_1") (pintype "passive"))
      (node (ref "C94") (pin "1") (pinfunction "1_1") (pintype "passive"))
      (node (ref "IC14") (pin "4") (pinfunction "V-_4") (pintype "bidirectional"))
      (node (ref "IC24") (pin "4") (pinfunction "V-_4") (pintype "power_in"))
      (node (ref "IC26") (pin "4") (pinfunction "V-_4") (pintype "power_in"))
      (node (ref "IC4") (pin "13") (pinfunction "VEE_13") (pintype "bidirectional"))
      (node (ref "IC9") (pin "1") (pinfunction "OUT_1") (pintype "bidirectional"))
      (node (ref "R32") (pin "2") (pinfunction "2_2") (pintype "passive"))
      (node (ref "R36") (pin "1") (pinfunction "1_1") (pintype "passive"))
      (node (ref "R54") (pin "2") (pinfunction "2_2") (pintype "passive"))
      (node (ref "R63") (pin "1") (pinfunction "1_1") (pintype "passive"))
      (node (ref "TP11") (pin "TP") (pinfunction "TP_TP") (pintype "input"))
    )
    (net (code "126") (name "PP_N6V0_CUK") (class "Default")
      (node (ref "C53") (pin "1") (pinfunction "1_1") (pintype "passive"))
      (node (ref "C56") (pin "1") (pinfunction "1_1") (pintype "passive"))
      (node (ref "IC9") (pin "5") (pinfunction "EN_5") (pintype "bidirectional"))
      (node (ref "IC9") (pin "8") (pinfunction "IN_8") (pintype "bidirectional"))
      (node (ref "L6") (pin "2") (pinfunction "2_2") (pintype "bidirectional"))
      (node (ref "R41") (pin "1") (pinfunction "1_1") (pintype "passive"))
    )
    (net (code "127") (name "PP_P3V3") (class "Default")
      (node (ref "C106") (pin "1") (pinfunction "1_1") (pintype "passive"))
      (node (ref "C109") (pin "1") (pinfunction "1_1") (pintype "passive"))
      (node (ref "C110") (pin "1") (pinfunction "1_1") (pintype "passive"))
      (node (ref "C111") (pin "1") (pinfunction "1_1") (pintype "passive"))
      (node (ref "C16") (pin "1") (pinfunction "1_1") (pintype "passive"))
      (node (ref "C21") (pin "1") (pinfunction "1_1") (pintype "passive"))
      (node (ref "C23") (pin "1") (pinfunction "1_1") (pintype "passive"))
      (node (ref "C28") (pin "1") (pinfunction "1_1") (pintype "passive"))
      (node (ref "C35") (pin "1") (pinfunction "1_1") (pintype "passive"))
      (node (ref "C43") (pin "1") (pinfunction "1_1") (pintype "passive"))
      (node (ref "C44") (pin "1") (pinfunction "1_1") (pintype "passive"))
      (node (ref "C48") (pin "1") (pinfunction "1_1") (pintype "passive"))
      (node (ref "C49") (pin "1") (pinfunction "1_1") (pintype "passive"))
      (node (ref "C58") (pin "1") (pinfunction "1_1") (pintype "passive"))
      (node (ref "C59") (pin "1") (pinfunction "1_1") (pintype "passive"))
      (node (ref "C60") (pin "1") (pinfunction "1_1") (pintype "passive"))
      (node (ref "C61") (pin "1") (pinfunction "1_1") (pintype "passive"))
      (node (ref "C63") (pin "1") (pinfunction "1_1") (pintype "passive"))
      (node (ref "C64") (pin "1") (pinfunction "1_1") (pintype "passive"))
      (node (ref "C65") (pin "1") (pinfunction "1_1") (pintype "passive"))
      (node (ref "C66") (pin "1") (pinfunction "1_1") (pintype "passive"))
      (node (ref "C73") (pin "1") (pinfunction "1_1") (pintype "passive"))
      (node (ref "C74") (pin "1") (pinfunction "1_1") (pintype "passive"))
      (node (ref "C81") (pin "1") (pinfunction "1_1") (pintype "passive"))
      (node (ref "C83") (pin "1") (pinfunction "1_1") (pintype "passive"))
      (node (ref "C84") (pin "1") (pinfunction "1_1") (pintype "passive"))
      (node (ref "C85") (pin "1") (pinfunction "1_1") (pintype "passive"))
      (node (ref "C87") (pin "1") (pinfunction "1_1") (pintype "passive"))
      (node (ref "C89") (pin "1") (pinfunction "1_1") (pintype "passive"))
      (node (ref "C90") (pin "1") (pinfunction "1_1") (pintype "passive"))
      (node (ref "C91") (pin "1") (pinfunction "1_1") (pintype "passive"))
      (node (ref "C95") (pin "1") (pinfunction "1_1") (pintype "passive"))
      (node (ref "C96") (pin "1") (pinfunction "1_1") (pintype "passive"))
      (node (ref "C97") (pin "1") (pinfunction "1_1") (pintype "passive"))
      (node (ref "C99") (pin "1") (pinfunction "1_1") (pintype "passive"))
      (node (ref "IC15") (pin "2") (pinfunction "D_2") (pintype "bidirectional"))
      (node (ref "IC15") (pin "8") (pinfunction "VDD_8") (pintype "bidirectional"))
      (node (ref "IC16") (pin "5") (pinfunction "VCC_5") (pintype "power_in"))
      (node (ref "IC17") (pin "2") (pinfunction "I_2") (pintype "input"))
      (node (ref "IC17") (pin "5") (pinfunction "VCC_5") (pintype "power_in"))
      (node (ref "IC18") (pin "5") (pinfunction "VCC_5") (pintype "power_in"))
      (node (ref "IC19") (pin "5") (pinfunction "VCC_5") (pintype "power_in"))
      (node (ref "IC20") (pin "5") (pinfunction "VCC_5") (pintype "bidirectional"))
      (node (ref "IC21") (pin "5") (pinfunction "VCC_5") (pintype "power_in"))
      (node (ref "IC22") (pin "5") (pinfunction "VCC_5") (pintype "power_in"))
      (node (ref "IC29") (pin "5") (pinfunction "VBUS_5") (pintype "bidirectional"))
      (node (ref "IC30") (pin "1") (pinfunction "VBAT_1") (pintype "bidirectional"))
      (node (ref "IC30") (pin "19") (pinfunction "VDD1_19") (pintype "bidirectional"))
      (node (ref "IC30") (pin "32") (pinfunction "VDD2_32") (pintype "bidirectional"))
      (node (ref "IC30") (pin "48") (pinfunction "VDD3_48") (pintype "bidirectional"))
      (node (ref "IC30") (pin "64") (pinfunction "VDD4_64") (pintype "bidirectional"))
      (node (ref "IC31") (pin "11") (pinfunction "VDDIO_11") (pintype "bidirectional"))
      (node (ref "IC31") (pin "18") (pinfunction "~{LDAC}_18") (pintype "bidirectional"))
      (node (ref "IC32") (pin "2") (pinfunction "OUT_2") (pintype "bidirectional"))
      (node (ref "IC32") (pin "4") (pinfunction "TAB_4") (pintype "bidirectional"))
      (node (ref "IC4") (pin "12") (pinfunction "VCCO_12") (pintype "bidirectional"))
      (node (ref "IC4") (pin "9") (pinfunction "VCCO_9") (pintype "bidirectional"))
      (node (ref "IC7") (pin "8") (pinfunction "VCC_8") (pintype "bidirectional"))
      (node (ref "L4") (pin "1") (pinfunction "P$1_1") (pintype "bidirectional"))
      (node (ref "L7") (pin "1") (pinfunction "P$1_1") (pintype "bidirectional"))
      (node (ref "PROG") (pin "1") (pinfunction "1_1") (pintype "bidirectional"))
      (node (ref "R12") (pin "1") (pinfunction "1_1") (pintype "passive"))
      (node (ref "R13") (pin "1") (pinfunction "1_1") (pintype "passive"))
      (node (ref "R66") (pin "1") (pinfunction "1_1") (pintype "passive"))
      (node (ref "R69") (pin "1") (pinfunction "1_1") (pintype "passive"))
      (node (ref "TP23") (pin "TP") (pinfunction "TP_TP") (pintype "input"))
      (node (ref "U2") (pin "8") (pinfunction "VCC_8") (pintype "power_in"))
      (node (ref "U3") (pin "8") (pinfunction "VCC_8") (pintype "power_in"))
    )
    (net (code "128") (name "PP_P3V3_AV_DET_DAC") (class "Default")
      (node (ref "C20") (pin "1") (pinfunction "1_1") (pintype "passive"))
      (node (ref "C22") (pin "1") (pinfunction "1_1") (pintype "passive"))
      (node (ref "L4") (pin "2") (pinfunction "P$2_2") (pintype "bidirectional"))
      (node (ref "R17") (pin "2") (pinfunction "2_2") (pintype "passive"))
      (node (ref "U1") (pin "3") (pinfunction "VDD_3") (pintype "power_in"))
    )
    (net (code "129") (name "PP_P3V3_VDDA") (class "Default")
      (node (ref "C86") (pin "1") (pinfunction "1_1") (pintype "passive"))
      (node (ref "C92") (pin "1") (pinfunction "1_1") (pintype "passive"))
      (node (ref "IC30") (pin "13") (pinfunction "VDDA_13") (pintype "bidirectional"))
      (node (ref "L7") (pin "2") (pinfunction "P$2_2") (pintype "bidirectional"))
    )
    (net (code "130") (name "PP_P5V0_ANALOG") (class "Default")
      (node (ref "C100") (pin "1") (pinfunction "1_1") (pintype "passive"))
      (node (ref "C12") (pin "1") (pinfunction "1_1") (pintype "passive"))
      (node (ref "C24") (pin "1") (pinfunction "1_1") (pintype "passive"))
      (node (ref "C29") (pin "1") (pinfunction "1_1") (pintype "passive"))
      (node (ref "C30") (pin "1") (pinfunction "1_1") (pintype "passive"))
      (node (ref "C36") (pin "1") (pinfunction "1_1") (pintype "passive"))
      (node (ref "C40") (pin "1") (pinfunction "1_1") (pintype "passive"))
      (node (ref "C47") (pin "1") (pinfunction "1_1") (pintype "passive"))
      (node (ref "C5") (pin "1") (pinfunction "1_1") (pintype "passive"))
      (node (ref "C50") (pin "1") (pinfunction "1_1") (pintype "passive"))
      (node (ref "C77") (pin "1") (pinfunction "1_1") (pintype "passive"))
      (node (ref "C78") (pin "1") (pinfunction "1_1") (pintype "passive"))
      (node (ref "C88") (pin "1") (pinfunction "1_1") (pintype "passive"))
      (node (ref "C9") (pin "1") (pinfunction "1_1") (pintype "passive"))
      (node (ref "C93") (pin "1") (pinfunction "1_1") (pintype "passive"))
      (node (ref "IC1") (pin "1") (pinfunction "OUT_1") (pintype "bidirectional"))
      (node (ref "IC11") (pin "1") (pinfunction "B_1") (pintype "passive"))
      (node (ref "IC11") (pin "4") (pinfunction "B_4") (pintype "passive"))
      (node (ref "IC13") (pin "6") (pinfunction "C_6") (pintype "passive"))
      (node (ref "IC14") (pin "1") (pinfunction "V+_1") (pintype "bidirectional"))
      (node (ref "IC24") (pin "8") (pinfunction "V+_8") (pintype "power_in"))
      (node (ref "IC26") (pin "8") (pinfunction "V+_8") (pintype "power_in"))
      (node (ref "IC28") (pin "5") (pinfunction "V+_5") (pintype "power_in"))
      (node (ref "IC4") (pin "16") (pinfunction "VCCI_16") (pintype "bidirectional"))
      (node (ref "IC4") (pin "5") (pinfunction "VCCI_5") (pintype "bidirectional"))
      (node (ref "IC5") (pin "1") (pinfunction "B_1") (pintype "passive"))
      (node (ref "IC5") (pin "4") (pinfunction "B_4") (pintype "passive"))
      (node (ref "IC6") (pin "1") (pinfunction "B_1") (pintype "passive"))
      (node (ref "IC6") (pin "4") (pinfunction "B_4") (pintype "passive"))
      (node (ref "L9") (pin "1") (pinfunction "P$1_1") (pintype "bidirectional"))
      (node (ref "R10") (pin "2") (pinfunction "2_2") (pintype "passive"))
      (node (ref "R56") (pin "2") (pinfunction "2_2") (pintype "passive"))
      (node (ref "TP3") (pin "TP") (pinfunction "TP_TP") (pintype "input"))
    )
    (net (code "131") (name "PP_P5V0_DAC1") (class "Default")
      (node (ref "C102") (pin "1") (pinfunction "1_1") (pintype "passive"))
      (node (ref "C103") (pin "1") (pinfunction "1_1") (pintype "passive"))
      (node (ref "IC31") (pin "10") (pinfunction "VDD_10") (pintype "bidirectional"))
      (node (ref "L9") (pin "2") (pinfunction "P$2_2") (pintype "bidirectional"))
      (node (ref "R73") (pin "1") (pinfunction "1_1") (pintype "passive"))
    )
    (net (code "132") (name "PP_P15V0_ANALOG") (class "Default")
      (node (ref "C10") (pin "1") (pinfunction "1_1") (pintype "passive"))
      (node (ref "C11") (pin "1") (pinfunction "1_1") (pintype "passive"))
      (node (ref "C6") (pin "1") (pinfunction "1_1") (pintype "passive"))
      (node (ref "C7") (pin "1") (pinfunction "1_1") (pintype "passive"))
      (node (ref "C75") (pin "1") (pinfunction "1_1") (pintype "passive"))
      (node (ref "C76") (pin "1") (pinfunction "1_1") (pintype "passive"))
      (node (ref "IC1") (pin "5") (pinfunction "EN_5") (pintype "bidirectional"))
      (node (ref "IC1") (pin "8") (pinfunction "IN_8") (pintype "bidirectional"))
      (node (ref "IC12") (pin "3") (pinfunction "C_3") (pintype "passive"))
      (node (ref "IC12") (pin "6") (pinfunction "C_6") (pintype "passive"))
      (node (ref "IC2") (pin "1") (pinfunction "OUT_1") (pintype "bidirectional"))
      (node (ref "IC25") (pin "12") (pinfunction "E_12") (pintype "passive"))
      (node (ref "IC25") (pin "3") (pinfunction "E_3") (pintype "passive"))
      (node (ref "R11") (pin "2") (pinfunction "2_2") (pintype "passive"))
      (node (ref "R46") (pin "2") (pinfunction "2_2") (pintype "passive"))
      (node (ref "TP1") (pin "TP") (pinfunction "TP_TP") (pintype "input"))
    )
    (net (code "133") (name "PP_P16V0_BOOST") (class "Default")
      (node (ref "C25") (pin "+") (pinfunction "+_+") (pintype "passive"))
      (node (ref "C8") (pin "1") (pinfunction "1_1") (pintype "passive"))
      (node (ref "IC2") (pin "5") (pinfunction "EN_5") (pintype "bidirectional"))
      (node (ref "IC2") (pin "8") (pinfunction "IN_8") (pintype "bidirectional"))
      (node (ref "L3") (pin "4") (pinfunction "4_4") (pintype "bidirectional"))
      (node (ref "R3") (pin "1") (pinfunction "1_1") (pintype "passive"))
      (node (ref "R9") (pin "2") (pinfunction "2_2") (pintype "passive"))
    )
    (net (code "134") (name "PULLDN_SENSE_R_CONN") (class "Default")
      (node (ref "R23") (pin "1") (pinfunction "1_1") (pintype "passive"))
      (node (ref "X1") (pin "1") (pinfunction "1_1") (pintype "passive"))
    )
    (net (code "135") (name "SMPS_USB_VDD") (class "Default")
      (node (ref "C113") (pin "1") (pinfunction "1_1") (pintype "passive"))
      (node (ref "C15") (pin "1") (pinfunction "1_1") (pintype "passive"))
      (node (ref "C17") (pin "1") (pinfunction "1_1") (pintype "passive"))
      (node (ref "C26") (pin "+") (pinfunction "+_+") (pintype "passive"))
      (node (ref "C27") (pin "1") (pinfunction "1_1") (pintype "passive"))
      (node (ref "C45") (pin "1") (pinfunction "1_1") (pintype "passive"))
      (node (ref "C57") (pin "1") (pinfunction "1_1") (pintype "passive"))
      (node (ref "C67") (pin "1") (pinfunction "1_1") (pintype "passive"))
      (node (ref "C79") (pin "2") (pinfunction "2_2") (pintype "passive"))
      (node (ref "D4") (pin "3") (pinfunction "C_3") (pintype "passive"))
      (node (ref "D5") (pin "3") (pinfunction "C_3") (pintype "passive"))
      (node (ref "IC10") (pin "15") (pinfunction "VIN_15") (pintype "bidirectional"))
      (node (ref "IC3") (pin "15") (pinfunction "VIN_15") (pintype "bidirectional"))
      (node (ref "L2") (pin "1") (pinfunction "P$1_1") (pintype "bidirectional"))
      (node (ref "L6") (pin "1") (pinfunction "1_1") (pintype "bidirectional"))
      (node (ref "Q1") (pin "3") (pinfunction "D_3") (pintype "passive"))
      (node (ref "RLY1") (pin "3") (pinfunction "PIN3_3") (pintype "bidirectional"))
      (node (ref "RLY2") (pin "3") (pinfunction "PIN3_3") (pintype "bidirectional"))
    )
    (net (code "136") (name "SPAD_PULLDN_SENSE") (class "Default")
      (node (ref "IC4") (pin "3") (pinfunction "VN_3") (pintype "bidirectional"))
      (node (ref "IC6") (pin "3") (pinfunction "C_3") (pintype "passive"))
      (node (ref "R23") (pin "2") (pinfunction "2_2") (pintype "passive"))
    )
    (net (code "137") (name "STEERING_CASC") (class "Default")
      (node (ref "IC11") (pin "2") (pinfunction "E_2") (pintype "passive"))
      (node (ref "IC13") (pin "3") (pinfunction "C_3") (pintype "passive"))
    )
    (net (code "138") (name "TP_FB_CUK") (class "Default")
      (node (ref "IC10") (pin "7") (pinfunction "FB_7") (pintype "bidirectional"))
      (node (ref "TP10") (pin "TP") (pinfunction "TP_TP") (pintype "input"))
    )
    (net (code "139") (name "TP_NFB_BOOST") (class "Default")
      (node (ref "IC3") (pin "10") (pinfunction "NFB_10") (pintype "bidirectional"))
      (node (ref "TP7") (pin "TP") (pinfunction "TP_TP") (pintype "input"))
    )
    (net (code "140") (name "TP_SYNC_BOOST") (class "Default")
      (node (ref "IC3") (pin "4") (pinfunction "SYNC_4") (pintype "bidirectional"))
      (node (ref "TP2") (pin "TP") (pinfunction "TP_TP") (pintype "input"))
    )
    (net (code "141") (name "TP_SYNC_CUK") (class "Default")
      (node (ref "IC10") (pin "4") (pinfunction "SYNC_4") (pintype "bidirectional"))
      (node (ref "TP8") (pin "TP") (pinfunction "TP_TP") (pintype "input"))
    )
    (net (code "142") (name "USBCONN_P1") (class "Default")
      (node (ref "C105") (pin "1") (pinfunction "1_1") (pintype "passive"))
      (node (ref "L8") (pin "1") (pinfunction "P$1_1") (pintype "bidirectional"))
      (node (ref "X8") (pin "1") (pinfunction "1_1") (pintype "passive"))
    )
    (net (code "143") (name "USBCONN_P4") (class "Default")
      (node (ref "L10") (pin "1") (pinfunction "P$1_1") (pintype "bidirectional"))
      (node (ref "X8") (pin "4") (pinfunction "4_4") (pintype "passive"))
    )
    (net (code "144") (name "USBD_CONN_N") (class "Default")
      (node (ref "IC29") (pin "3") (pinfunction "I/O2_3") (pintype "bidirectional"))
      (node (ref "X8") (pin "2") (pinfunction "2_2") (pintype "passive"))
    )
    (net (code "145") (name "USBD_CONN_P") (class "Default")
      (node (ref "IC29") (pin "1") (pinfunction "I/O1_1_1") (pintype "bidirectional"))
      (node (ref "X8") (pin "3") (pinfunction "3_3") (pintype "passive"))
    )
    (net (code "146") (name "USBD_TVS_N") (class "Default")
      (node (ref "IC29") (pin "4") (pinfunction "I/O2_2_4") (pintype "bidirectional"))
      (node (ref "R70") (pin "2") (pinfunction "2_2") (pintype "passive"))
    )
    (net (code "147") (name "USBD_TVS_P") (class "Default")
      (node (ref "IC29") (pin "6") (pinfunction "I/O1_2_6") (pintype "bidirectional"))
      (node (ref "R67") (pin "2") (pinfunction "2_2") (pintype "passive"))
    )
    (net (code "148") (name "USB_VDD") (class "Default")
      (node (ref "C107") (pin "1") (pinfunction "1_1") (pintype "passive"))
      (node (ref "C108") (pin "1") (pinfunction "1_1") (pintype "passive"))
      (node (ref "IC32") (pin "3") (pinfunction "IN_3") (pintype "bidirectional"))
      (node (ref "L8") (pin "2") (pinfunction "P$2_2") (pintype "bidirectional"))
      (node (ref "Q1") (pin "2") (pinfunction "S_2") (pintype "passive"))
      (node (ref "R62") (pin "2") (pinfunction "2_2") (pintype "passive"))
    )
    (net (code "149") (name "VA_BASE") (class "Default")
      (node (ref "IC23") (pin "4") (pinfunction "B_4") (pintype "passive"))
      (node (ref "IC26") (pin "7") (pinfunction "OUT_7") (pintype "output"))
    )
    (net (code "150") (name "VA_FB") (class "Default")
      (node (ref "IC23") (pin "5") (pinfunction "E_5") (pintype "passive"))
      (node (ref "IC26") (pin "6") (pinfunction "-IN_6") (pintype "input"))
      (node (ref "R50") (pin "2") (pinfunction "2_2") (pintype "passive"))
    )
    (net (code "151") (name "VBB") (class "Default")
      (node (ref "U3") (pin "4") (pinfunction "VBB_4") (pintype "power_in"))
    )
    (net (code "152") (name "VREF_AV_DET") (class "Default")
      (node (ref "C33") (pin "1") (pinfunction "1_1") (pintype "passive"))
      (node (ref "C34") (pin "1") (pinfunction "1_1") (pintype "passive"))
      (node (ref "IC4") (pin "2") (pinfunction "VP_2") (pintype "bidirectional"))
      (node (ref "R17") (pin "1") (pinfunction "1_1") (pintype "passive"))
      (node (ref "R18") (pin "1") (pinfunction "1_1") (pintype "passive"))
      (node (ref "R19") (pin "2") (pinfunction "2_2") (pintype "passive"))
      (node (ref "TP6") (pin "P$1") (pinfunction "P$1_P$1") (pintype "bidirectional"))
    )
    (net (code "153") (name "VREF_DELTAV_SETPOINT") (class "Default")
      (node (ref "IC31") (pin "2") (pinfunction "OUT0_2") (pintype "bidirectional"))
      (node (ref "R64") (pin "2") (pinfunction "2_2") (pintype "passive"))
      (node (ref "TP14") (pin "P$1") (pinfunction "P$1_P$1") (pintype "bidirectional"))
    )
    (net (code "154") (name "VREF_DIAMOND_IBIAS") (class "Default")
      (node (ref "IC28") (pin "3") (pinfunction "+IN_3") (pintype "input"))
      (node (ref "IC31") (pin "3") (pinfunction "OUT1_3") (pintype "bidirectional"))
      (node (ref "TP15") (pin "P$1") (pinfunction "P$1_P$1") (pintype "bidirectional"))
    )
    (net (code "155") (name "VREF_EXTRA_2") (class "Default")
      (node (ref "IC31") (pin "7") (pinfunction "OUT5_7") (pintype "bidirectional"))
      (node (ref "TP19") (pin "P$1") (pinfunction "P$1_P$1") (pintype "bidirectional"))
    )
    (net (code "156") (name "VREF_EXTRA_3") (class "Default")
      (node (ref "IC31") (pin "8") (pinfunction "OUT6_8") (pintype "bidirectional"))
      (node (ref "TP20") (pin "P$1") (pinfunction "P$1_P$1") (pintype "bidirectional"))
    )
    (net (code "157") (name "VREF_EXTRA_4") (class "Default")
      (node (ref "IC31") (pin "9") (pinfunction "OUT7_9") (pintype "bidirectional"))
      (node (ref "TP21") (pin "P$1") (pinfunction "P$1_P$1") (pintype "bidirectional"))
    )
    (net (code "158") (name "VREF_ONE_SHOT_CCS") (class "Default")
      (node (ref "IC31") (pin "6") (pinfunction "OUT4_6") (pintype "bidirectional"))
      (node (ref "R61") (pin "2") (pinfunction "2_2") (pintype "passive"))
      (node (ref "TP18") (pin "P$1") (pinfunction "P$1_P$1") (pintype "bidirectional"))
    )
    (net (code "159") (name "VREF_ONE_SHOT_COMP") (class "Default")
      (node (ref "IC24") (pin "5") (pinfunction "+IN_5") (pintype "input"))
      (node (ref "IC31") (pin "4") (pinfunction "OUT2_4") (pintype "bidirectional"))
      (node (ref "TP16") (pin "P$1") (pinfunction "P$1_P$1") (pintype "bidirectional"))
    )
    (net (code "160") (name "VREF_VA_SETPOINT") (class "Default")
      (node (ref "IC26") (pin "5") (pinfunction "+IN_5") (pintype "input"))
      (node (ref "IC31") (pin "5") (pinfunction "OUT3_5") (pintype "bidirectional"))
      (node (ref "TP17") (pin "P$1") (pinfunction "P$1_P$1") (pintype "bidirectional"))
    )
    (net (code "161") (name "V_IVTEST") (class "Default")
      (node (ref "RLY2") (pin "5") (pinfunction "PIN5_5") (pintype "bidirectional"))
      (node (ref "X7") (pin "1") (pinfunction "1_1") (pintype "passive"))
    )
    (net (code "162") (name "V_SCOPE") (class "Default")
      (node (ref "R35") (pin "2") (pinfunction "2_2") (pintype "passive"))
      (node (ref "TP9") (pin "SIG") (pinfunction "1_SIG") (pintype "passive"))
    )
    (net (code "163") (name "V_SPAD") (class "Default")
      (node (ref "D3") (pin "C") (pinfunction "C_C") (pintype "passive"))
      (node (ref "RLY1") (pin "5") (pinfunction "PIN5_5") (pintype "bidirectional"))
      (node (ref "RLY2") (pin "10") (pinfunction "PIN10_10") (pintype "bidirectional"))
      (node (ref "X4") (pin "1") (pinfunction "1_1") (pintype "passive"))
    )
    (net (code "164") (name "unconnected-(IC4-VTP-Pad1)") (class "Default")
      (node (ref "IC4") (pin "1") (pinfunction "VTP_1") (pintype "bidirectional"))
    )
    (net (code "165") (name "unconnected-(IC30-PA4{slash}SPI1_NSS-Pad20)") (class "Default")
      (node (ref "IC30") (pin "20") (pinfunction "PA4/SPI1_NSS_20") (pintype "bidirectional"))
    )
    (net (code "166") (name "unconnected-(IC30-PA6{slash}SPI1_MISO-Pad22)") (class "Default")
      (node (ref "IC30") (pin "22") (pinfunction "PA6/SPI1_MISO_22") (pintype "bidirectional"))
    )
    (net (code "167") (name "unconnected-(IC30-PA7{slash}SPI1_MOSI-Pad23)") (class "Default")
      (node (ref "IC30") (pin "23") (pinfunction "PA7/SPI1_MOSI_23") (pintype "bidirectional"))
    )
    (net (code "168") (name "unconnected-(IC30-PA8-Pad41)") (class "Default")
      (node (ref "IC30") (pin "41") (pinfunction "PA8_41") (pintype "bidirectional"))
    )
    (net (code "169") (name "unconnected-(IC30-PA9{slash}UART1_TX-Pad42)") (class "Default")
      (node (ref "IC30") (pin "42") (pinfunction "PA9/UART1_TX_42") (pintype "bidirectional"))
    )
    (net (code "170") (name "unconnected-(IC30-PA10{slash}UART1_RX-Pad43)") (class "Default")
      (node (ref "IC30") (pin "43") (pinfunction "PA10/UART1_RX_43") (pintype "bidirectional"))
    )
    (net (code "171") (name "unconnected-(IC30-PB0-Pad26)") (class "Default")
      (node (ref "IC30") (pin "26") (pinfunction "PB0_26") (pintype "bidirectional"))
    )
    (net (code "172") (name "unconnected-(IC30-PB1-Pad27)") (class "Default")
      (node (ref "IC30") (pin "27") (pinfunction "PB1_27") (pintype "bidirectional"))
    )
    (net (code "173") (name "unconnected-(IC30-PB4{slash}JTRST-Pad56)") (class "Default")
      (node (ref "IC30") (pin "56") (pinfunction "PB4/JTRST_56") (pintype "bidirectional"))
    )
    (net (code "174") (name "unconnected-(IC30-PB8-Pad61)") (class "Default")
      (node (ref "IC30") (pin "61") (pinfunction "PB8_61") (pintype "bidirectional"))
    )
    (net (code "175") (name "unconnected-(IC30-PB9-Pad62)") (class "Default")
      (node (ref "IC30") (pin "62") (pinfunction "PB9_62") (pintype "bidirectional"))
    )
    (net (code "176") (name "unconnected-(IC30-PB10-Pad29)") (class "Default")
      (node (ref "IC30") (pin "29") (pinfunction "PB10_29") (pintype "bidirectional"))
    )
    (net (code "177") (name "unconnected-(IC30-PB14{slash}I2S2_XD-Pad35)") (class "Default")
      (node (ref "IC30") (pin "35") (pinfunction "PB14/I2S2_XD_35") (pintype "bidirectional"))
    )
    (net (code "178") (name "unconnected-(IC30-PB15{slash}I2S2_SD-Pad36)") (class "Default")
      (node (ref "IC30") (pin "36") (pinfunction "PB15/I2S2_SD_36") (pintype "bidirectional"))
    )
    (net (code "179") (name "unconnected-(IC30-PC3-Pad11)") (class "Default")
      (node (ref "IC30") (pin "11") (pinfunction "PC3_11") (pintype "bidirectional"))
    )
    (net (code "180") (name "unconnected-(IC30-PC4-Pad24)") (class "Default")
      (node (ref "IC30") (pin "24") (pinfunction "PC4_24") (pintype "bidirectional"))
    )
    (net (code "181") (name "unconnected-(IC30-PC5-Pad25)") (class "Default")
      (node (ref "IC30") (pin "25") (pinfunction "PC5_25") (pintype "bidirectional"))
    )
    (net (code "182") (name "unconnected-(IC30-PC6{slash}I2S2_MCK-Pad37)") (class "Default")
      (node (ref "IC30") (pin "37") (pinfunction "PC6/I2S2_MCK_37") (pintype "bidirectional"))
    )
    (net (code "183") (name "unconnected-(IC30-PC7-Pad38)") (class "Default")
      (node (ref "IC30") (pin "38") (pinfunction "PC7_38") (pintype "bidirectional"))
    )
    (net (code "184") (name "unconnected-(IC30-PC8{slash}SDIO_D0-Pad39)") (class "Default")
      (node (ref "IC30") (pin "39") (pinfunction "PC8/SDIO_D0_39") (pintype "bidirectional"))
    )
    (net (code "185") (name "unconnected-(IC30-PC9{slash}SDIO_D1-Pad40)") (class "Default")
      (node (ref "IC30") (pin "40") (pinfunction "PC9/SDIO_D1_40") (pintype "bidirectional"))
    )
    (net (code "186") (name "unconnected-(IC30-PC13-Pad2)") (class "Default")
      (node (ref "IC30") (pin "2") (pinfunction "PC13_2") (pintype "bidirectional"))
    )
    (net (code "187") (name "unconnected-(IC30-PC14-Pad3)") (class "Default")
      (node (ref "IC30") (pin "3") (pinfunction "PC14_3") (pintype "bidirectional"))
    )
    (net (code "188") (name "unconnected-(IC30-PC15-Pad4)") (class "Default")
      (node (ref "IC30") (pin "4") (pinfunction "PC15_4") (pintype "bidirectional"))
    )
    (net (code "189") (name "unconnected-(RLY1-PIN7-Pad7)") (class "Default")
      (node (ref "RLY1") (pin "7") (pinfunction "PIN7_7") (pintype "bidirectional"))
    )
    (net (code "190") (name "unconnected-(RLY1-PIN8-Pad8)") (class "Default")
      (node (ref "RLY1") (pin "8") (pinfunction "PIN8_8") (pintype "bidirectional"))
    )
    (net (code "191") (name "unconnected-(RLY2-PIN7-Pad7)") (class "Default")
      (node (ref "RLY2") (pin "7") (pinfunction "PIN7_7") (pintype "bidirectional"))
    )
    (net (code "192") (name "unconnected-(RLY2-PIN8-Pad8)") (class "Default")
      (node (ref "RLY2") (pin "8") (pinfunction "PIN8_8") (pintype "bidirectional"))
    )
    (net (code "193") (name "unconnected-(U2-Q1-Pad3)") (class "Default")
      (node (ref "U2") (pin "3") (pinfunction "Q1_3") (pintype "output"))
    )
    (net (code "194") (name "unconnected-(U2-~{Q1}-Pad4)") (class "Default")
      (node (ref "U2") (pin "4") (pinfunction "~{Q1}_4") (pintype "output"))
    )
    (net (code "195") (name "unconnected-(U3-NC-Pad6)") (class "Default")
      (node (ref "U3") (pin "6") (pinfunction "NC_6") (pintype "no_connect"))
    )
    (net (code "196") (name "unconnected-(U3-NC_2-Pad1)") (class "Default")
      (node (ref "U3") (pin "1") (pinfunction "NC_2_1") (pintype "no_connect"))
    )
    (net (code "197") (name "~{FORCE_QUENCH}") (class "Default")
      (node (ref "IC15") (pin "7") (pinfunction "~{PRE}_7") (pintype "bidirectional"))
      (node (ref "IC18") (pin "4") (pinfunction "O_4") (pintype "output"))
      (node (ref "IC22") (pin "1") (pinfunction "I0_1") (pintype "input"))
    )
    (net (code "198") (name "~{LOGIC_QUENCH}") (class "Default")
      (node (ref "IC13") (pin "1") (pinfunction "B_1") (pintype "passive"))
      (node (ref "IC15") (pin "3") (pinfunction "~{Q}_3") (pintype "bidirectional"))
      (node (ref "IC16") (pin "2") (pinfunction "I_2") (pintype "input"))
      (node (ref "TP12") (pin "TP") (pinfunction "TP_TP") (pintype "input"))
    )
    (net (code "199") (name "~{MCU_SHDN_BOOST}") (class "Default")
      (node (ref "IC3") (pin "12") (pinfunction "~{SHDN}_12") (pintype "bidirectional"))
      (node (ref "IC30") (pin "16") (pinfunction "PA2/UART2_TX_16") (pintype "bidirectional"))
    )
    (net (code "200") (name "~{MCU_SHDN_CUK}") (class "Default")
      (node (ref "IC10") (pin "12") (pinfunction "~{SHDN}_12") (pintype "bidirectional"))
      (node (ref "IC30") (pin "15") (pinfunction "PA1_15") (pintype "bidirectional"))
    )
    (net (code "201") (name "~{MCU_SMPS_PRECHG}") (class "Default")
      (node (ref "IC30") (pin "17") (pinfunction "PA3/UART2_RX_17") (pintype "bidirectional"))
      (node (ref "R58") (pin "2") (pinfunction "2_2") (pintype "passive"))
    )
    (net (code "202") (name "~{ONE_SHOT_CLR}") (class "Default")
      (node (ref "IC14") (pin "7") (pinfunction "Q_7") (pintype "bidirectional"))
      (node (ref "IC21") (pin "2") (pinfunction "I1_2") (pintype "input"))
    )
  )
)
